# schematic.net
KiCad netlist of a schematic drawn in Altium Designer
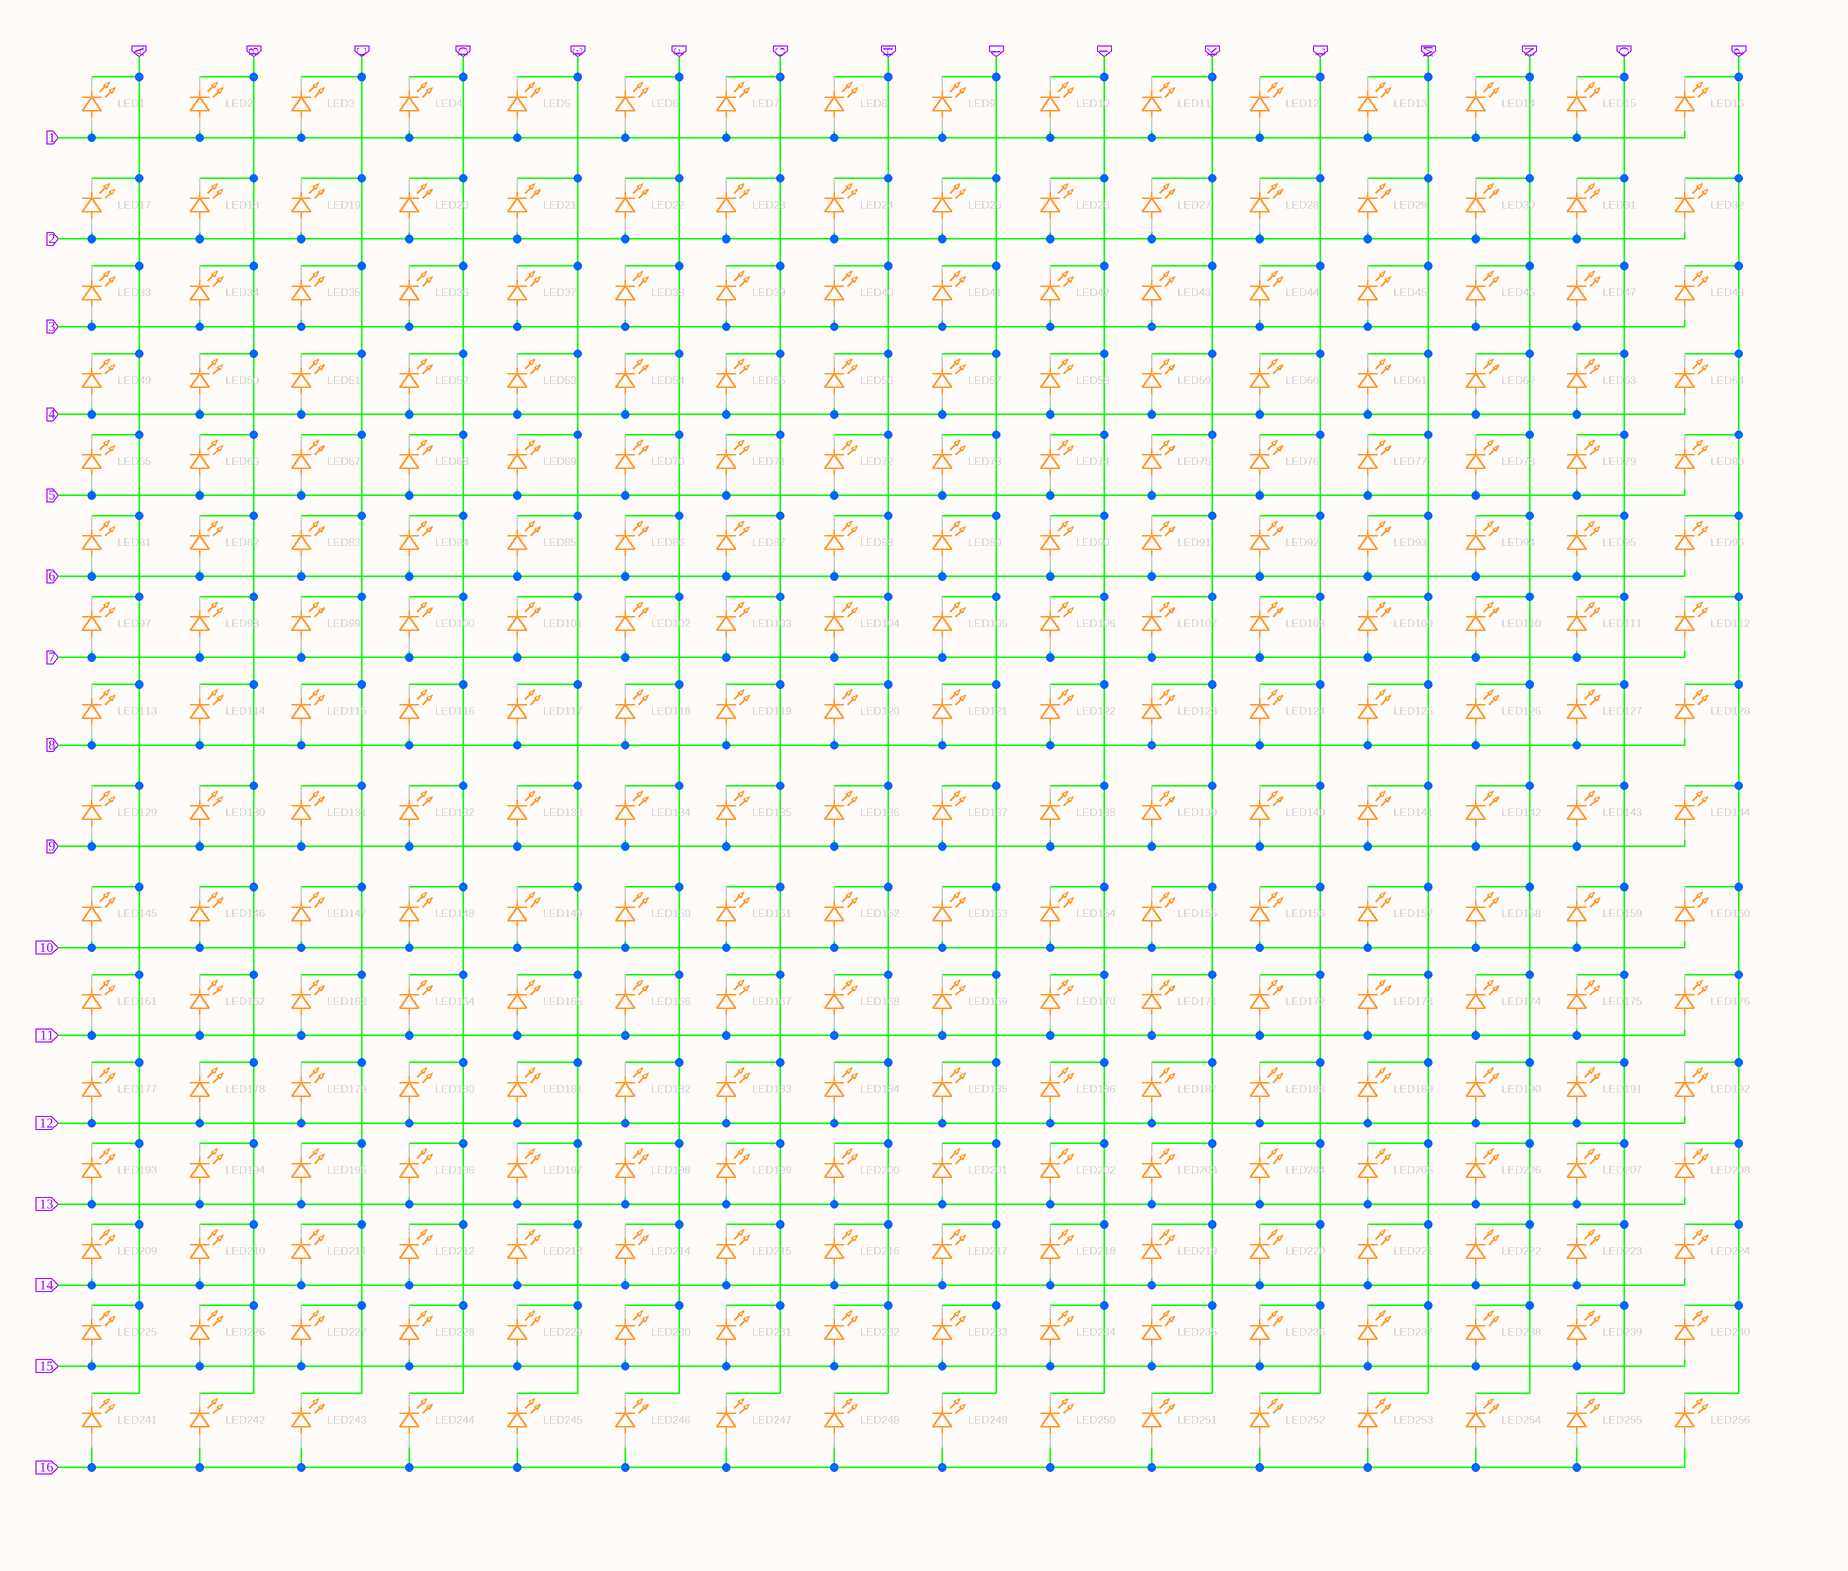
[diagram p0: schematic.schdoc, left]
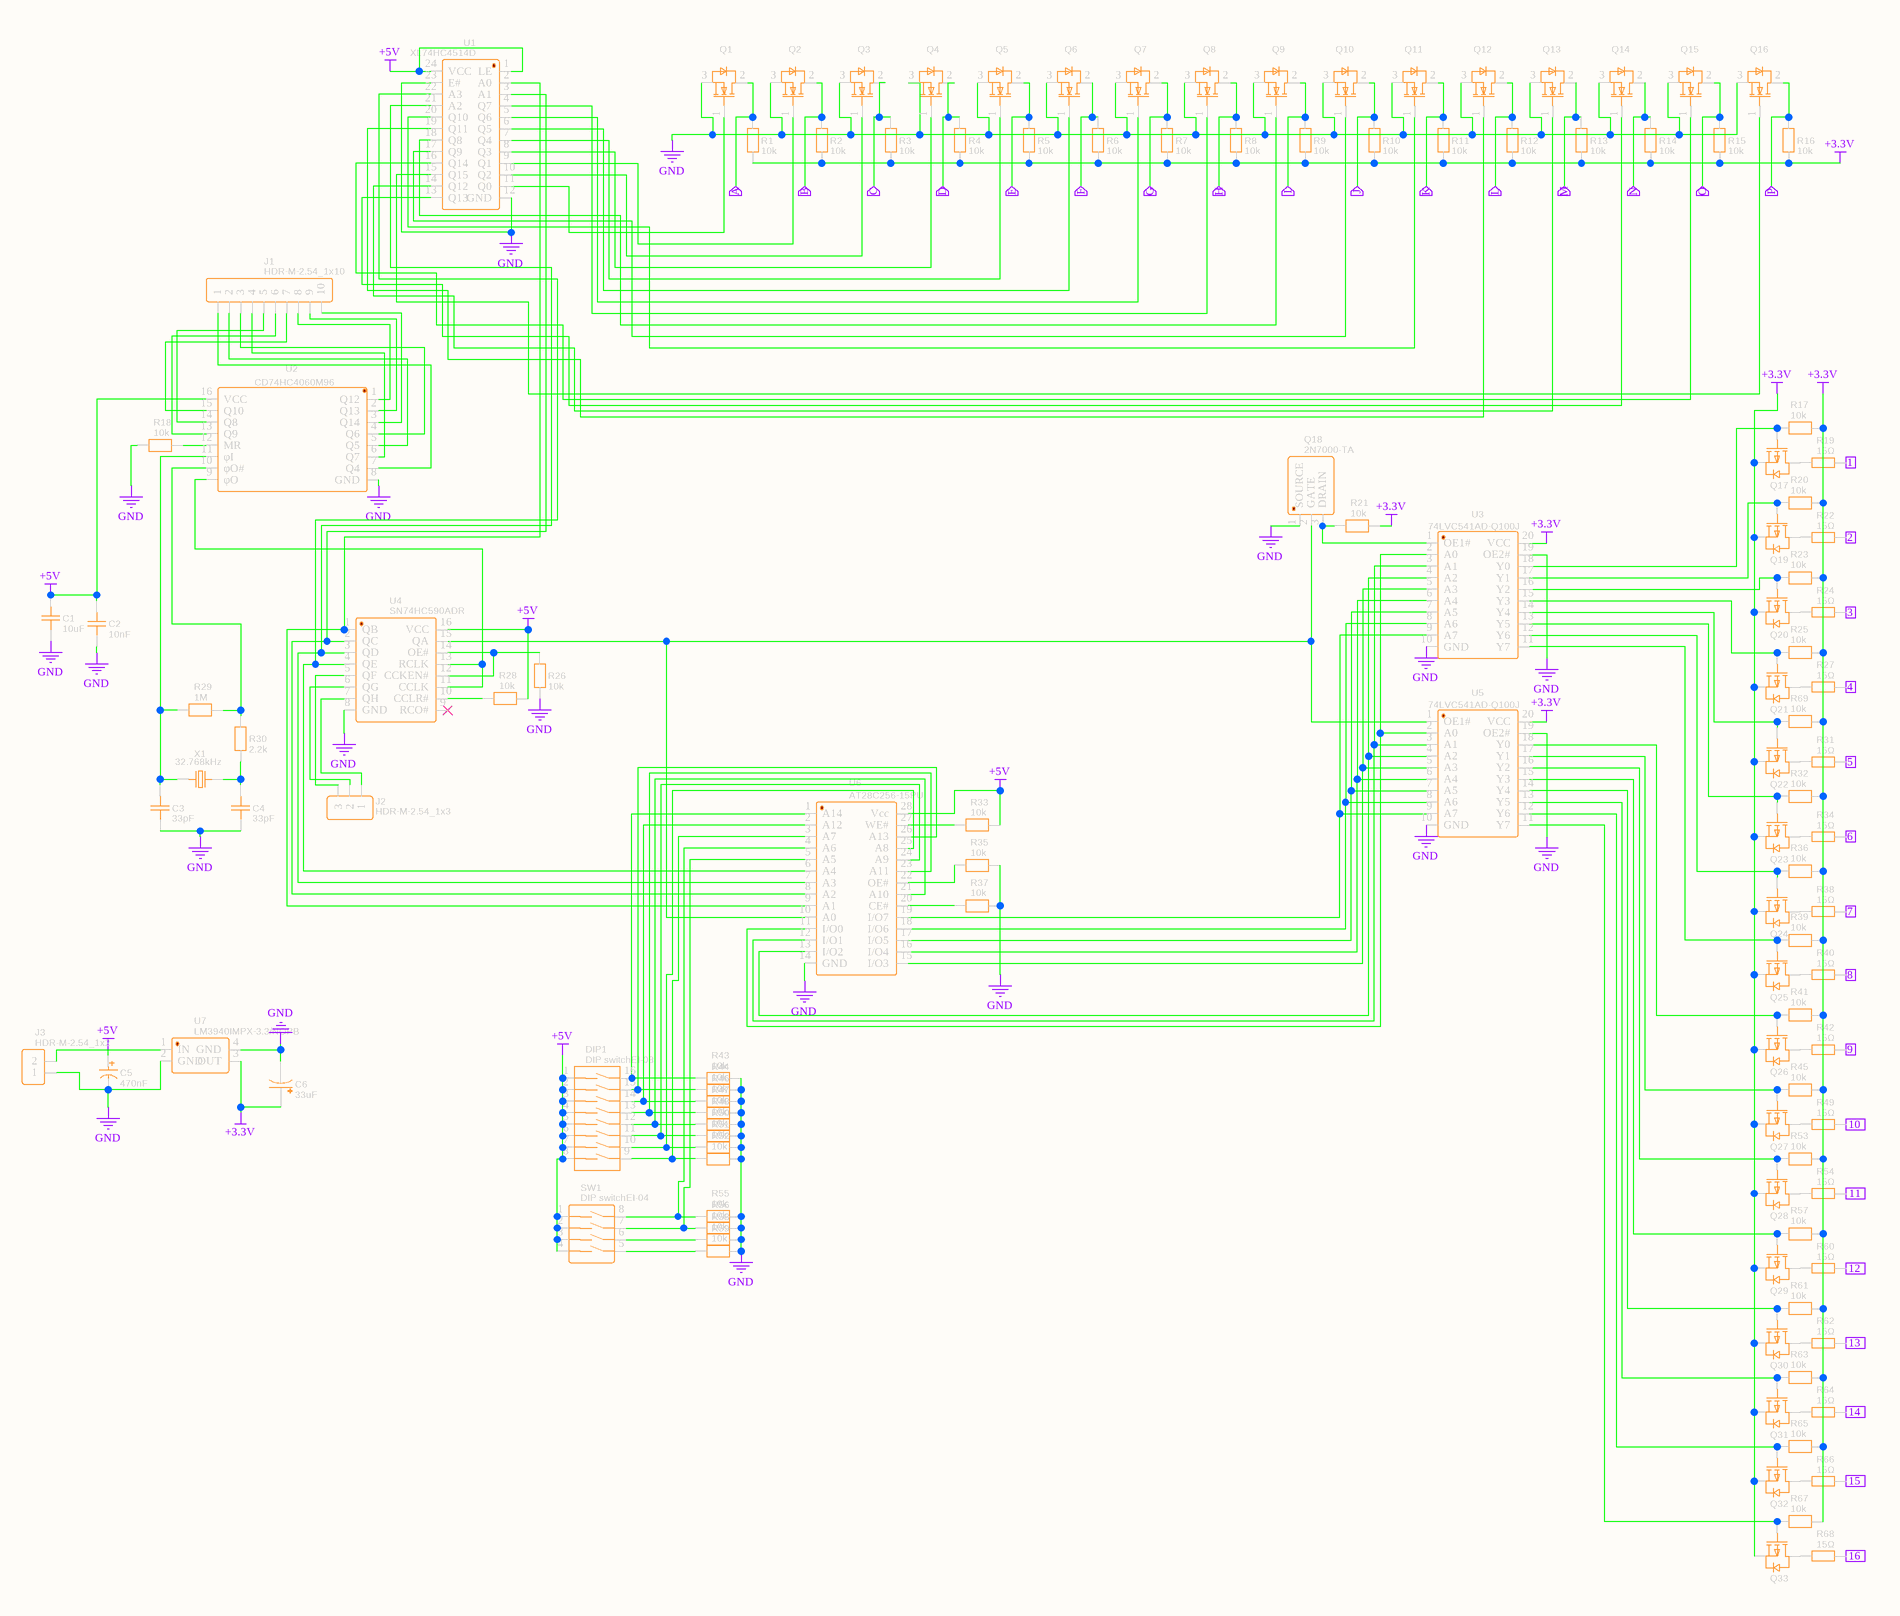
[diagram p1: schematic.schdoc, right]

(export (version "E")
  (design (tool "Eeschema 10.0.6"))
  (components
    (comp (ref "C1")
      (value "10uF")
      (fields
        (field (name "MANUFACTURER") "TORCH(火炬)")
        (field (name "MANUFACTURER PART") "CC1210Y5V16V106ZN")
        (field (name "CONTRIBUTOR") "lcsc")
      )
      (libsource (lib "altium-import") (part "root_1_10uF_"))
    )
    (comp (ref "C2")
      (value "10nF")
      (fields
        (field (name "MANUFACTURER") "HRE(芯声)")
        (field (name "MANUFACTURER PART") "CSA0805C0G103J500MT")
        (field (name "CONTRIBUTOR") "lcsc")
      )
      (libsource (lib "altium-import") (part "root_1_10nF_"))
    )
    (comp (ref "C3")
      (value "33pF")
      (fields
        (field (name "MANUFACTURER") "Kyocera AVX")
        (field (name "MANUFACTURER PART") "600F330JT250XT")
        (field (name "CONTRIBUTOR") "lcsc")
      )
      (libsource (lib "altium-import") (part "root_1_33pF_"))
    )
    (comp (ref "C4")
      (value "33pF")
      (fields
        (field (name "MANUFACTURER") "Kyocera AVX")
        (field (name "MANUFACTURER PART") "600F330JT250XT")
        (field (name "CONTRIBUTOR") "lcsc")
      )
      (libsource (lib "altium-import") (part "root_1_33pF_"))
    )
    (comp (ref "C5")
      (value "470nF")
      (fields
        (field (name "MANUFACTURER") "Chengx(承兴)")
        (field (name "MANUFACTURER PART") "kF474M050C05RR0VH2FP0")
      )
      (libsource (lib "altium-import") (part "root_0_470nF_"))
    )
    (comp (ref "C6")
      (value "33uF")
      (fields
        (field (name "MANUFACTURER") "Jianghai(南通江海)")
        (field (name "MANUFACTURER PART") "ECR1HPT330MLL063011")
        (field (name "CONTRIBUTOR") "LCSC")
      )
      (libsource (lib "altium-import") (part "root_2_33uF_"))
    )
    (comp (ref "DIP1")
      (value "DIP switchEI-08")
      (fields (field (name "MANUFACTURER") "Diptronics(圜达)") (field (name "MANUFACTURER PART") "EI-08-V"))
      (libsource (lib "altium-import") (part "root_0_DIP switchEI-08_"))
    )
    (comp (ref "J1")
      (value "HDR-M-2.54_1x10")
      (fields
        (field (name "MANUFACTURER") "hanxia(韩下)")
        (field (name "MANUFACTURER PART") "HX PZ-2005WV-1x10P")
        (field (name "CONTRIBUTOR") "LCEDA_Lib")
      )
      (libsource (lib "altium-import") (part "root_1_HDR-M-2.54_1x10_"))
    )
    (comp (ref "J2")
      (value "HDR-M-2.54_1x3")
      (fields
        (field (name "MANUFACTURER") "HDGC(华德共创)")
        (field (name "MANUFACTURER PART") "5557WRF-1X3P(HDGC4201WR-F-1X3P)")
        (field (name "CONTRIBUTOR") "LCEDA_Lib")
      )
      (libsource (lib "altium-import") (part "root_3_HDR-M-2.54_1x3_"))
    )
    (comp (ref "J3")
      (value "HDR-M-2.54_1x2")
      (fields (field (name "CONTRIBUTOR") "LCEDA_Lib"))
      (libsource (lib "altium-import") (part "root_2_HDR-M-2.54_1x2_"))
    )
    (comp (ref "LED1")
      (value "42-21A/GHC-YX1Y2N/1T")
      (fields (field (name "MANUFACTURER") "EVERLIGHT(亿光)") (field (name "CONTRIBUTOR") "lcsc"))
      (libsource (lib "altium-import") (part "root_3_42-21A/GHC-YX1Y2N/1T_"))
    )
    (comp (ref "LED2")
      (value "42-21A/GHC-YX1Y2N/1T")
      (fields (field (name "MANUFACTURER") "EVERLIGHT(亿光)") (field (name "CONTRIBUTOR") "lcsc"))
      (libsource (lib "altium-import") (part "root_3_42-21A/GHC-YX1Y2N/1T_"))
    )
    (comp (ref "LED3")
      (value "42-21A/GHC-YX1Y2N/1T")
      (fields (field (name "MANUFACTURER") "EVERLIGHT(亿光)") (field (name "CONTRIBUTOR") "lcsc"))
      (libsource (lib "altium-import") (part "root_3_42-21A/GHC-YX1Y2N/1T_"))
    )
    (comp (ref "LED4")
      (value "42-21A/GHC-YX1Y2N/1T")
      (fields (field (name "MANUFACTURER") "EVERLIGHT(亿光)") (field (name "CONTRIBUTOR") "lcsc"))
      (libsource (lib "altium-import") (part "root_3_42-21A/GHC-YX1Y2N/1T_"))
    )
    (comp (ref "LED5")
      (value "42-21A/GHC-YX1Y2N/1T")
      (fields (field (name "MANUFACTURER") "EVERLIGHT(亿光)") (field (name "CONTRIBUTOR") "lcsc"))
      (libsource (lib "altium-import") (part "root_3_42-21A/GHC-YX1Y2N/1T_"))
    )
    (comp (ref "LED6")
      (value "42-21A/GHC-YX1Y2N/1T")
      (fields (field (name "MANUFACTURER") "EVERLIGHT(亿光)") (field (name "CONTRIBUTOR") "lcsc"))
      (libsource (lib "altium-import") (part "root_3_42-21A/GHC-YX1Y2N/1T_"))
    )
    (comp (ref "LED7")
      (value "42-21A/GHC-YX1Y2N/1T")
      (fields (field (name "MANUFACTURER") "EVERLIGHT(亿光)") (field (name "CONTRIBUTOR") "lcsc"))
      (libsource (lib "altium-import") (part "root_3_42-21A/GHC-YX1Y2N/1T_"))
    )
    (comp (ref "LED8")
      (value "42-21A/GHC-YX1Y2N/1T")
      (fields (field (name "MANUFACTURER") "EVERLIGHT(亿光)") (field (name "CONTRIBUTOR") "lcsc"))
      (libsource (lib "altium-import") (part "root_3_42-21A/GHC-YX1Y2N/1T_"))
    )
    (comp (ref "LED9")
      (value "42-21A/GHC-YX1Y2N/1T")
      (fields (field (name "MANUFACTURER") "EVERLIGHT(亿光)") (field (name "CONTRIBUTOR") "lcsc"))
      (libsource (lib "altium-import") (part "root_3_42-21A/GHC-YX1Y2N/1T_"))
    )
    (comp (ref "LED10")
      (value "42-21A/GHC-YX1Y2N/1T")
      (fields (field (name "MANUFACTURER") "EVERLIGHT(亿光)") (field (name "CONTRIBUTOR") "lcsc"))
      (libsource (lib "altium-import") (part "root_3_42-21A/GHC-YX1Y2N/1T_"))
    )
    (comp (ref "LED11")
      (value "42-21A/GHC-YX1Y2N/1T")
      (fields (field (name "MANUFACTURER") "EVERLIGHT(亿光)") (field (name "CONTRIBUTOR") "lcsc"))
      (libsource (lib "altium-import") (part "root_3_42-21A/GHC-YX1Y2N/1T_"))
    )
    (comp (ref "LED12")
      (value "42-21A/GHC-YX1Y2N/1T")
      (fields (field (name "MANUFACTURER") "EVERLIGHT(亿光)") (field (name "CONTRIBUTOR") "lcsc"))
      (libsource (lib "altium-import") (part "root_3_42-21A/GHC-YX1Y2N/1T_"))
    )
    (comp (ref "LED13")
      (value "42-21A/GHC-YX1Y2N/1T")
      (fields (field (name "MANUFACTURER") "EVERLIGHT(亿光)") (field (name "CONTRIBUTOR") "lcsc"))
      (libsource (lib "altium-import") (part "root_3_42-21A/GHC-YX1Y2N/1T_"))
    )
    (comp (ref "LED14")
      (value "42-21A/GHC-YX1Y2N/1T")
      (fields (field (name "MANUFACTURER") "EVERLIGHT(亿光)") (field (name "CONTRIBUTOR") "lcsc"))
      (libsource (lib "altium-import") (part "root_3_42-21A/GHC-YX1Y2N/1T_"))
    )
    (comp (ref "LED15")
      (value "42-21A/GHC-YX1Y2N/1T")
      (fields (field (name "MANUFACTURER") "EVERLIGHT(亿光)") (field (name "CONTRIBUTOR") "lcsc"))
      (libsource (lib "altium-import") (part "root_3_42-21A/GHC-YX1Y2N/1T_"))
    )
    (comp (ref "LED16")
      (value "42-21A/GHC-YX1Y2N/1T")
      (fields (field (name "MANUFACTURER") "EVERLIGHT(亿光)") (field (name "CONTRIBUTOR") "lcsc"))
      (libsource (lib "altium-import") (part "root_3_42-21A/GHC-YX1Y2N/1T_"))
    )
    (comp (ref "LED17")
      (value "42-21A/GHC-YX1Y2N/1T")
      (fields (field (name "MANUFACTURER") "EVERLIGHT(亿光)") (field (name "CONTRIBUTOR") "lcsc"))
      (libsource (lib "altium-import") (part "root_3_42-21A/GHC-YX1Y2N/1T_"))
    )
    (comp (ref "LED18")
      (value "42-21A/GHC-YX1Y2N/1T")
      (fields (field (name "MANUFACTURER") "EVERLIGHT(亿光)") (field (name "CONTRIBUTOR") "lcsc"))
      (libsource (lib "altium-import") (part "root_3_42-21A/GHC-YX1Y2N/1T_"))
    )
    (comp (ref "LED19")
      (value "42-21A/GHC-YX1Y2N/1T")
      (fields (field (name "MANUFACTURER") "EVERLIGHT(亿光)") (field (name "CONTRIBUTOR") "lcsc"))
      (libsource (lib "altium-import") (part "root_3_42-21A/GHC-YX1Y2N/1T_"))
    )
    (comp (ref "LED20")
      (value "42-21A/GHC-YX1Y2N/1T")
      (fields (field (name "MANUFACTURER") "EVERLIGHT(亿光)") (field (name "CONTRIBUTOR") "lcsc"))
      (libsource (lib "altium-import") (part "root_3_42-21A/GHC-YX1Y2N/1T_"))
    )
    (comp (ref "LED21")
      (value "42-21A/GHC-YX1Y2N/1T")
      (fields (field (name "MANUFACTURER") "EVERLIGHT(亿光)") (field (name "CONTRIBUTOR") "lcsc"))
      (libsource (lib "altium-import") (part "root_3_42-21A/GHC-YX1Y2N/1T_"))
    )
    (comp (ref "LED22")
      (value "42-21A/GHC-YX1Y2N/1T")
      (fields (field (name "MANUFACTURER") "EVERLIGHT(亿光)") (field (name "CONTRIBUTOR") "lcsc"))
      (libsource (lib "altium-import") (part "root_3_42-21A/GHC-YX1Y2N/1T_"))
    )
    (comp (ref "LED23")
      (value "42-21A/GHC-YX1Y2N/1T")
      (fields (field (name "MANUFACTURER") "EVERLIGHT(亿光)") (field (name "CONTRIBUTOR") "lcsc"))
      (libsource (lib "altium-import") (part "root_3_42-21A/GHC-YX1Y2N/1T_"))
    )
    (comp (ref "LED24")
      (value "42-21A/GHC-YX1Y2N/1T")
      (fields (field (name "MANUFACTURER") "EVERLIGHT(亿光)") (field (name "CONTRIBUTOR") "lcsc"))
      (libsource (lib "altium-import") (part "root_3_42-21A/GHC-YX1Y2N/1T_"))
    )
    (comp (ref "LED25")
      (value "42-21A/GHC-YX1Y2N/1T")
      (fields (field (name "MANUFACTURER") "EVERLIGHT(亿光)") (field (name "CONTRIBUTOR") "lcsc"))
      (libsource (lib "altium-import") (part "root_3_42-21A/GHC-YX1Y2N/1T_"))
    )
    (comp (ref "LED26")
      (value "42-21A/GHC-YX1Y2N/1T")
      (fields (field (name "MANUFACTURER") "EVERLIGHT(亿光)") (field (name "CONTRIBUTOR") "lcsc"))
      (libsource (lib "altium-import") (part "root_3_42-21A/GHC-YX1Y2N/1T_"))
    )
    (comp (ref "LED27")
      (value "42-21A/GHC-YX1Y2N/1T")
      (fields (field (name "MANUFACTURER") "EVERLIGHT(亿光)") (field (name "CONTRIBUTOR") "lcsc"))
      (libsource (lib "altium-import") (part "root_3_42-21A/GHC-YX1Y2N/1T_"))
    )
    (comp (ref "LED28")
      (value "42-21A/GHC-YX1Y2N/1T")
      (fields (field (name "MANUFACTURER") "EVERLIGHT(亿光)") (field (name "CONTRIBUTOR") "lcsc"))
      (libsource (lib "altium-import") (part "root_3_42-21A/GHC-YX1Y2N/1T_"))
    )
    (comp (ref "LED29")
      (value "42-21A/GHC-YX1Y2N/1T")
      (fields (field (name "MANUFACTURER") "EVERLIGHT(亿光)") (field (name "CONTRIBUTOR") "lcsc"))
      (libsource (lib "altium-import") (part "root_3_42-21A/GHC-YX1Y2N/1T_"))
    )
    (comp (ref "LED30")
      (value "42-21A/GHC-YX1Y2N/1T")
      (fields (field (name "MANUFACTURER") "EVERLIGHT(亿光)") (field (name "CONTRIBUTOR") "lcsc"))
      (libsource (lib "altium-import") (part "root_3_42-21A/GHC-YX1Y2N/1T_"))
    )
    (comp (ref "LED31")
      (value "42-21A/GHC-YX1Y2N/1T")
      (fields (field (name "MANUFACTURER") "EVERLIGHT(亿光)") (field (name "CONTRIBUTOR") "lcsc"))
      (libsource (lib "altium-import") (part "root_3_42-21A/GHC-YX1Y2N/1T_"))
    )
    (comp (ref "LED32")
      (value "42-21A/GHC-YX1Y2N/1T")
      (fields (field (name "MANUFACTURER") "EVERLIGHT(亿光)") (field (name "CONTRIBUTOR") "lcsc"))
      (libsource (lib "altium-import") (part "root_3_42-21A/GHC-YX1Y2N/1T_"))
    )
    (comp (ref "LED33")
      (value "42-21A/GHC-YX1Y2N/1T")
      (fields (field (name "MANUFACTURER") "EVERLIGHT(亿光)") (field (name "CONTRIBUTOR") "lcsc"))
      (libsource (lib "altium-import") (part "root_3_42-21A/GHC-YX1Y2N/1T_"))
    )
    (comp (ref "LED34")
      (value "42-21A/GHC-YX1Y2N/1T")
      (fields (field (name "MANUFACTURER") "EVERLIGHT(亿光)") (field (name "CONTRIBUTOR") "lcsc"))
      (libsource (lib "altium-import") (part "root_3_42-21A/GHC-YX1Y2N/1T_"))
    )
    (comp (ref "LED35")
      (value "42-21A/GHC-YX1Y2N/1T")
      (fields (field (name "MANUFACTURER") "EVERLIGHT(亿光)") (field (name "CONTRIBUTOR") "lcsc"))
      (libsource (lib "altium-import") (part "root_3_42-21A/GHC-YX1Y2N/1T_"))
    )
    (comp (ref "LED36")
      (value "42-21A/GHC-YX1Y2N/1T")
      (fields (field (name "MANUFACTURER") "EVERLIGHT(亿光)") (field (name "CONTRIBUTOR") "lcsc"))
      (libsource (lib "altium-import") (part "root_3_42-21A/GHC-YX1Y2N/1T_"))
    )
    (comp (ref "LED37")
      (value "42-21A/GHC-YX1Y2N/1T")
      (fields (field (name "MANUFACTURER") "EVERLIGHT(亿光)") (field (name "CONTRIBUTOR") "lcsc"))
      (libsource (lib "altium-import") (part "root_3_42-21A/GHC-YX1Y2N/1T_"))
    )
    (comp (ref "LED38")
      (value "42-21A/GHC-YX1Y2N/1T")
      (fields (field (name "MANUFACTURER") "EVERLIGHT(亿光)") (field (name "CONTRIBUTOR") "lcsc"))
      (libsource (lib "altium-import") (part "root_3_42-21A/GHC-YX1Y2N/1T_"))
    )
    (comp (ref "LED39")
      (value "42-21A/GHC-YX1Y2N/1T")
      (fields (field (name "MANUFACTURER") "EVERLIGHT(亿光)") (field (name "CONTRIBUTOR") "lcsc"))
      (libsource (lib "altium-import") (part "root_3_42-21A/GHC-YX1Y2N/1T_"))
    )
    (comp (ref "LED40")
      (value "42-21A/GHC-YX1Y2N/1T")
      (fields (field (name "MANUFACTURER") "EVERLIGHT(亿光)") (field (name "CONTRIBUTOR") "lcsc"))
      (libsource (lib "altium-import") (part "root_3_42-21A/GHC-YX1Y2N/1T_"))
    )
    (comp (ref "LED41")
      (value "42-21A/GHC-YX1Y2N/1T")
      (fields (field (name "MANUFACTURER") "EVERLIGHT(亿光)") (field (name "CONTRIBUTOR") "lcsc"))
      (libsource (lib "altium-import") (part "root_3_42-21A/GHC-YX1Y2N/1T_"))
    )
    (comp (ref "LED42")
      (value "42-21A/GHC-YX1Y2N/1T")
      (fields (field (name "MANUFACTURER") "EVERLIGHT(亿光)") (field (name "CONTRIBUTOR") "lcsc"))
      (libsource (lib "altium-import") (part "root_3_42-21A/GHC-YX1Y2N/1T_"))
    )
    (comp (ref "LED43")
      (value "42-21A/GHC-YX1Y2N/1T")
      (fields (field (name "MANUFACTURER") "EVERLIGHT(亿光)") (field (name "CONTRIBUTOR") "lcsc"))
      (libsource (lib "altium-import") (part "root_3_42-21A/GHC-YX1Y2N/1T_"))
    )
    (comp (ref "LED44")
      (value "42-21A/GHC-YX1Y2N/1T")
      (fields (field (name "MANUFACTURER") "EVERLIGHT(亿光)") (field (name "CONTRIBUTOR") "lcsc"))
      (libsource (lib "altium-import") (part "root_3_42-21A/GHC-YX1Y2N/1T_"))
    )
    (comp (ref "LED45")
      (value "42-21A/GHC-YX1Y2N/1T")
      (fields (field (name "MANUFACTURER") "EVERLIGHT(亿光)") (field (name "CONTRIBUTOR") "lcsc"))
      (libsource (lib "altium-import") (part "root_3_42-21A/GHC-YX1Y2N/1T_"))
    )
    (comp (ref "LED46")
      (value "42-21A/GHC-YX1Y2N/1T")
      (fields (field (name "MANUFACTURER") "EVERLIGHT(亿光)") (field (name "CONTRIBUTOR") "lcsc"))
      (libsource (lib "altium-import") (part "root_3_42-21A/GHC-YX1Y2N/1T_"))
    )
    (comp (ref "LED47")
      (value "42-21A/GHC-YX1Y2N/1T")
      (fields (field (name "MANUFACTURER") "EVERLIGHT(亿光)") (field (name "CONTRIBUTOR") "lcsc"))
      (libsource (lib "altium-import") (part "root_3_42-21A/GHC-YX1Y2N/1T_"))
    )
    (comp (ref "LED48")
      (value "42-21A/GHC-YX1Y2N/1T")
      (fields (field (name "MANUFACTURER") "EVERLIGHT(亿光)") (field (name "CONTRIBUTOR") "lcsc"))
      (libsource (lib "altium-import") (part "root_3_42-21A/GHC-YX1Y2N/1T_"))
    )
    (comp (ref "LED49")
      (value "42-21A/GHC-YX1Y2N/1T")
      (fields (field (name "MANUFACTURER") "EVERLIGHT(亿光)") (field (name "CONTRIBUTOR") "lcsc"))
      (libsource (lib "altium-import") (part "root_3_42-21A/GHC-YX1Y2N/1T_"))
    )
    (comp (ref "LED50")
      (value "42-21A/GHC-YX1Y2N/1T")
      (fields (field (name "MANUFACTURER") "EVERLIGHT(亿光)") (field (name "CONTRIBUTOR") "lcsc"))
      (libsource (lib "altium-import") (part "root_3_42-21A/GHC-YX1Y2N/1T_"))
    )
    (comp (ref "LED51")
      (value "42-21A/GHC-YX1Y2N/1T")
      (fields (field (name "MANUFACTURER") "EVERLIGHT(亿光)") (field (name "CONTRIBUTOR") "lcsc"))
      (libsource (lib "altium-import") (part "root_3_42-21A/GHC-YX1Y2N/1T_"))
    )
    (comp (ref "LED52")
      (value "42-21A/GHC-YX1Y2N/1T")
      (fields (field (name "MANUFACTURER") "EVERLIGHT(亿光)") (field (name "CONTRIBUTOR") "lcsc"))
      (libsource (lib "altium-import") (part "root_3_42-21A/GHC-YX1Y2N/1T_"))
    )
    (comp (ref "LED53")
      (value "42-21A/GHC-YX1Y2N/1T")
      (fields (field (name "MANUFACTURER") "EVERLIGHT(亿光)") (field (name "CONTRIBUTOR") "lcsc"))
      (libsource (lib "altium-import") (part "root_3_42-21A/GHC-YX1Y2N/1T_"))
    )
    (comp (ref "LED54")
      (value "42-21A/GHC-YX1Y2N/1T")
      (fields (field (name "MANUFACTURER") "EVERLIGHT(亿光)") (field (name "CONTRIBUTOR") "lcsc"))
      (libsource (lib "altium-import") (part "root_3_42-21A/GHC-YX1Y2N/1T_"))
    )
    (comp (ref "LED55")
      (value "42-21A/GHC-YX1Y2N/1T")
      (fields (field (name "MANUFACTURER") "EVERLIGHT(亿光)") (field (name "CONTRIBUTOR") "lcsc"))
      (libsource (lib "altium-import") (part "root_3_42-21A/GHC-YX1Y2N/1T_"))
    )
    (comp (ref "LED56")
      (value "42-21A/GHC-YX1Y2N/1T")
      (fields (field (name "MANUFACTURER") "EVERLIGHT(亿光)") (field (name "CONTRIBUTOR") "lcsc"))
      (libsource (lib "altium-import") (part "root_3_42-21A/GHC-YX1Y2N/1T_"))
    )
    (comp (ref "LED57")
      (value "42-21A/GHC-YX1Y2N/1T")
      (fields (field (name "MANUFACTURER") "EVERLIGHT(亿光)") (field (name "CONTRIBUTOR") "lcsc"))
      (libsource (lib "altium-import") (part "root_3_42-21A/GHC-YX1Y2N/1T_"))
    )
    (comp (ref "LED58")
      (value "42-21A/GHC-YX1Y2N/1T")
      (fields (field (name "MANUFACTURER") "EVERLIGHT(亿光)") (field (name "CONTRIBUTOR") "lcsc"))
      (libsource (lib "altium-import") (part "root_3_42-21A/GHC-YX1Y2N/1T_"))
    )
    (comp (ref "LED59")
      (value "42-21A/GHC-YX1Y2N/1T")
      (fields (field (name "MANUFACTURER") "EVERLIGHT(亿光)") (field (name "CONTRIBUTOR") "lcsc"))
      (libsource (lib "altium-import") (part "root_3_42-21A/GHC-YX1Y2N/1T_"))
    )
    (comp (ref "LED60")
      (value "42-21A/GHC-YX1Y2N/1T")
      (fields (field (name "MANUFACTURER") "EVERLIGHT(亿光)") (field (name "CONTRIBUTOR") "lcsc"))
      (libsource (lib "altium-import") (part "root_3_42-21A/GHC-YX1Y2N/1T_"))
    )
    (comp (ref "LED61")
      (value "42-21A/GHC-YX1Y2N/1T")
      (fields (field (name "MANUFACTURER") "EVERLIGHT(亿光)") (field (name "CONTRIBUTOR") "lcsc"))
      (libsource (lib "altium-import") (part "root_3_42-21A/GHC-YX1Y2N/1T_"))
    )
    (comp (ref "LED62")
      (value "42-21A/GHC-YX1Y2N/1T")
      (fields (field (name "MANUFACTURER") "EVERLIGHT(亿光)") (field (name "CONTRIBUTOR") "lcsc"))
      (libsource (lib "altium-import") (part "root_3_42-21A/GHC-YX1Y2N/1T_"))
    )
    (comp (ref "LED63")
      (value "42-21A/GHC-YX1Y2N/1T")
      (fields (field (name "MANUFACTURER") "EVERLIGHT(亿光)") (field (name "CONTRIBUTOR") "lcsc"))
      (libsource (lib "altium-import") (part "root_3_42-21A/GHC-YX1Y2N/1T_"))
    )
    (comp (ref "LED64")
      (value "42-21A/GHC-YX1Y2N/1T")
      (fields (field (name "MANUFACTURER") "EVERLIGHT(亿光)") (field (name "CONTRIBUTOR") "lcsc"))
      (libsource (lib "altium-import") (part "root_3_42-21A/GHC-YX1Y2N/1T_"))
    )
    (comp (ref "LED65")
      (value "42-21A/GHC-YX1Y2N/1T")
      (fields (field (name "MANUFACTURER") "EVERLIGHT(亿光)") (field (name "CONTRIBUTOR") "lcsc"))
      (libsource (lib "altium-import") (part "root_3_42-21A/GHC-YX1Y2N/1T_"))
    )
    (comp (ref "LED66")
      (value "42-21A/GHC-YX1Y2N/1T")
      (fields (field (name "MANUFACTURER") "EVERLIGHT(亿光)") (field (name "CONTRIBUTOR") "lcsc"))
      (libsource (lib "altium-import") (part "root_3_42-21A/GHC-YX1Y2N/1T_"))
    )
    (comp (ref "LED67")
      (value "42-21A/GHC-YX1Y2N/1T")
      (fields (field (name "MANUFACTURER") "EVERLIGHT(亿光)") (field (name "CONTRIBUTOR") "lcsc"))
      (libsource (lib "altium-import") (part "root_3_42-21A/GHC-YX1Y2N/1T_"))
    )
    (comp (ref "LED68")
      (value "42-21A/GHC-YX1Y2N/1T")
      (fields (field (name "MANUFACTURER") "EVERLIGHT(亿光)") (field (name "CONTRIBUTOR") "lcsc"))
      (libsource (lib "altium-import") (part "root_3_42-21A/GHC-YX1Y2N/1T_"))
    )
    (comp (ref "LED69")
      (value "42-21A/GHC-YX1Y2N/1T")
      (fields (field (name "MANUFACTURER") "EVERLIGHT(亿光)") (field (name "CONTRIBUTOR") "lcsc"))
      (libsource (lib "altium-import") (part "root_3_42-21A/GHC-YX1Y2N/1T_"))
    )
    (comp (ref "LED70")
      (value "42-21A/GHC-YX1Y2N/1T")
      (fields (field (name "MANUFACTURER") "EVERLIGHT(亿光)") (field (name "CONTRIBUTOR") "lcsc"))
      (libsource (lib "altium-import") (part "root_3_42-21A/GHC-YX1Y2N/1T_"))
    )
    (comp (ref "LED71")
      (value "42-21A/GHC-YX1Y2N/1T")
      (fields (field (name "MANUFACTURER") "EVERLIGHT(亿光)") (field (name "CONTRIBUTOR") "lcsc"))
      (libsource (lib "altium-import") (part "root_3_42-21A/GHC-YX1Y2N/1T_"))
    )
    (comp (ref "LED72")
      (value "42-21A/GHC-YX1Y2N/1T")
      (fields (field (name "MANUFACTURER") "EVERLIGHT(亿光)") (field (name "CONTRIBUTOR") "lcsc"))
      (libsource (lib "altium-import") (part "root_3_42-21A/GHC-YX1Y2N/1T_"))
    )
    (comp (ref "LED73")
      (value "42-21A/GHC-YX1Y2N/1T")
      (fields (field (name "MANUFACTURER") "EVERLIGHT(亿光)") (field (name "CONTRIBUTOR") "lcsc"))
      (libsource (lib "altium-import") (part "root_3_42-21A/GHC-YX1Y2N/1T_"))
    )
    (comp (ref "LED74")
      (value "42-21A/GHC-YX1Y2N/1T")
      (fields (field (name "MANUFACTURER") "EVERLIGHT(亿光)") (field (name "CONTRIBUTOR") "lcsc"))
      (libsource (lib "altium-import") (part "root_3_42-21A/GHC-YX1Y2N/1T_"))
    )
    (comp (ref "LED75")
      (value "42-21A/GHC-YX1Y2N/1T")
      (fields (field (name "MANUFACTURER") "EVERLIGHT(亿光)") (field (name "CONTRIBUTOR") "lcsc"))
      (libsource (lib "altium-import") (part "root_3_42-21A/GHC-YX1Y2N/1T_"))
    )
    (comp (ref "LED76")
      (value "42-21A/GHC-YX1Y2N/1T")
      (fields (field (name "MANUFACTURER") "EVERLIGHT(亿光)") (field (name "CONTRIBUTOR") "lcsc"))
      (libsource (lib "altium-import") (part "root_3_42-21A/GHC-YX1Y2N/1T_"))
    )
    (comp (ref "LED77")
      (value "42-21A/GHC-YX1Y2N/1T")
      (fields (field (name "MANUFACTURER") "EVERLIGHT(亿光)") (field (name "CONTRIBUTOR") "lcsc"))
      (libsource (lib "altium-import") (part "root_3_42-21A/GHC-YX1Y2N/1T_"))
    )
    (comp (ref "LED78")
      (value "42-21A/GHC-YX1Y2N/1T")
      (fields (field (name "MANUFACTURER") "EVERLIGHT(亿光)") (field (name "CONTRIBUTOR") "lcsc"))
      (libsource (lib "altium-import") (part "root_3_42-21A/GHC-YX1Y2N/1T_"))
    )
    (comp (ref "LED79")
      (value "42-21A/GHC-YX1Y2N/1T")
      (fields (field (name "MANUFACTURER") "EVERLIGHT(亿光)") (field (name "CONTRIBUTOR") "lcsc"))
      (libsource (lib "altium-import") (part "root_3_42-21A/GHC-YX1Y2N/1T_"))
    )
    (comp (ref "LED80")
      (value "42-21A/GHC-YX1Y2N/1T")
      (fields (field (name "MANUFACTURER") "EVERLIGHT(亿光)") (field (name "CONTRIBUTOR") "lcsc"))
      (libsource (lib "altium-import") (part "root_3_42-21A/GHC-YX1Y2N/1T_"))
    )
    (comp (ref "LED81")
      (value "42-21A/GHC-YX1Y2N/1T")
      (fields (field (name "MANUFACTURER") "EVERLIGHT(亿光)") (field (name "CONTRIBUTOR") "lcsc"))
      (libsource (lib "altium-import") (part "root_3_42-21A/GHC-YX1Y2N/1T_"))
    )
    (comp (ref "LED82")
      (value "42-21A/GHC-YX1Y2N/1T")
      (fields (field (name "MANUFACTURER") "EVERLIGHT(亿光)") (field (name "CONTRIBUTOR") "lcsc"))
      (libsource (lib "altium-import") (part "root_3_42-21A/GHC-YX1Y2N/1T_"))
    )
    (comp (ref "LED83")
      (value "42-21A/GHC-YX1Y2N/1T")
      (fields (field (name "MANUFACTURER") "EVERLIGHT(亿光)") (field (name "CONTRIBUTOR") "lcsc"))
      (libsource (lib "altium-import") (part "root_3_42-21A/GHC-YX1Y2N/1T_"))
    )
    (comp (ref "LED84")
      (value "42-21A/GHC-YX1Y2N/1T")
      (fields (field (name "MANUFACTURER") "EVERLIGHT(亿光)") (field (name "CONTRIBUTOR") "lcsc"))
      (libsource (lib "altium-import") (part "root_3_42-21A/GHC-YX1Y2N/1T_"))
    )
    (comp (ref "LED85")
      (value "42-21A/GHC-YX1Y2N/1T")
      (fields (field (name "MANUFACTURER") "EVERLIGHT(亿光)") (field (name "CONTRIBUTOR") "lcsc"))
      (libsource (lib "altium-import") (part "root_3_42-21A/GHC-YX1Y2N/1T_"))
    )
    (comp (ref "LED86")
      (value "42-21A/GHC-YX1Y2N/1T")
      (fields (field (name "MANUFACTURER") "EVERLIGHT(亿光)") (field (name "CONTRIBUTOR") "lcsc"))
      (libsource (lib "altium-import") (part "root_3_42-21A/GHC-YX1Y2N/1T_"))
    )
    (comp (ref "LED87")
      (value "42-21A/GHC-YX1Y2N/1T")
      (fields (field (name "MANUFACTURER") "EVERLIGHT(亿光)") (field (name "CONTRIBUTOR") "lcsc"))
      (libsource (lib "altium-import") (part "root_3_42-21A/GHC-YX1Y2N/1T_"))
    )
    (comp (ref "LED88")
      (value "42-21A/GHC-YX1Y2N/1T")
      (fields (field (name "MANUFACTURER") "EVERLIGHT(亿光)") (field (name "CONTRIBUTOR") "lcsc"))
      (libsource (lib "altium-import") (part "root_3_42-21A/GHC-YX1Y2N/1T_"))
    )
    (comp (ref "LED89")
      (value "42-21A/GHC-YX1Y2N/1T")
      (fields (field (name "MANUFACTURER") "EVERLIGHT(亿光)") (field (name "CONTRIBUTOR") "lcsc"))
      (libsource (lib "altium-import") (part "root_3_42-21A/GHC-YX1Y2N/1T_"))
    )
    (comp (ref "LED90")
      (value "42-21A/GHC-YX1Y2N/1T")
      (fields (field (name "MANUFACTURER") "EVERLIGHT(亿光)") (field (name "CONTRIBUTOR") "lcsc"))
      (libsource (lib "altium-import") (part "root_3_42-21A/GHC-YX1Y2N/1T_"))
    )
    (comp (ref "LED91")
      (value "42-21A/GHC-YX1Y2N/1T")
      (fields (field (name "MANUFACTURER") "EVERLIGHT(亿光)") (field (name "CONTRIBUTOR") "lcsc"))
      (libsource (lib "altium-import") (part "root_3_42-21A/GHC-YX1Y2N/1T_"))
    )
    (comp (ref "LED92")
      (value "42-21A/GHC-YX1Y2N/1T")
      (fields (field (name "MANUFACTURER") "EVERLIGHT(亿光)") (field (name "CONTRIBUTOR") "lcsc"))
      (libsource (lib "altium-import") (part "root_3_42-21A/GHC-YX1Y2N/1T_"))
    )
    (comp (ref "LED93")
      (value "42-21A/GHC-YX1Y2N/1T")
      (fields (field (name "MANUFACTURER") "EVERLIGHT(亿光)") (field (name "CONTRIBUTOR") "lcsc"))
      (libsource (lib "altium-import") (part "root_3_42-21A/GHC-YX1Y2N/1T_"))
    )
    (comp (ref "LED94")
      (value "42-21A/GHC-YX1Y2N/1T")
      (fields (field (name "MANUFACTURER") "EVERLIGHT(亿光)") (field (name "CONTRIBUTOR") "lcsc"))
      (libsource (lib "altium-import") (part "root_3_42-21A/GHC-YX1Y2N/1T_"))
    )
    (comp (ref "LED95")
      (value "42-21A/GHC-YX1Y2N/1T")
      (fields (field (name "MANUFACTURER") "EVERLIGHT(亿光)") (field (name "CONTRIBUTOR") "lcsc"))
      (libsource (lib "altium-import") (part "root_3_42-21A/GHC-YX1Y2N/1T_"))
    )
    (comp (ref "LED96")
      (value "42-21A/GHC-YX1Y2N/1T")
      (fields (field (name "MANUFACTURER") "EVERLIGHT(亿光)") (field (name "CONTRIBUTOR") "lcsc"))
      (libsource (lib "altium-import") (part "root_3_42-21A/GHC-YX1Y2N/1T_"))
    )
    (comp (ref "LED97")
      (value "42-21A/GHC-YX1Y2N/1T")
      (fields (field (name "MANUFACTURER") "EVERLIGHT(亿光)") (field (name "CONTRIBUTOR") "lcsc"))
      (libsource (lib "altium-import") (part "root_3_42-21A/GHC-YX1Y2N/1T_"))
    )
    (comp (ref "LED98")
      (value "42-21A/GHC-YX1Y2N/1T")
      (fields (field (name "MANUFACTURER") "EVERLIGHT(亿光)") (field (name "CONTRIBUTOR") "lcsc"))
      (libsource (lib "altium-import") (part "root_3_42-21A/GHC-YX1Y2N/1T_"))
    )
    (comp (ref "LED99")
      (value "42-21A/GHC-YX1Y2N/1T")
      (fields (field (name "MANUFACTURER") "EVERLIGHT(亿光)") (field (name "CONTRIBUTOR") "lcsc"))
      (libsource (lib "altium-import") (part "root_3_42-21A/GHC-YX1Y2N/1T_"))
    )
    (comp (ref "LED100")
      (value "42-21A/GHC-YX1Y2N/1T")
      (fields (field (name "MANUFACTURER") "EVERLIGHT(亿光)") (field (name "CONTRIBUTOR") "lcsc"))
      (libsource (lib "altium-import") (part "root_3_42-21A/GHC-YX1Y2N/1T_"))
    )
    (comp (ref "LED101")
      (value "42-21A/GHC-YX1Y2N/1T")
      (fields (field (name "MANUFACTURER") "EVERLIGHT(亿光)") (field (name "CONTRIBUTOR") "lcsc"))
      (libsource (lib "altium-import") (part "root_3_42-21A/GHC-YX1Y2N/1T_"))
    )
    (comp (ref "LED102")
      (value "42-21A/GHC-YX1Y2N/1T")
      (fields (field (name "MANUFACTURER") "EVERLIGHT(亿光)") (field (name "CONTRIBUTOR") "lcsc"))
      (libsource (lib "altium-import") (part "root_3_42-21A/GHC-YX1Y2N/1T_"))
    )
    (comp (ref "LED103")
      (value "42-21A/GHC-YX1Y2N/1T")
      (fields (field (name "MANUFACTURER") "EVERLIGHT(亿光)") (field (name "CONTRIBUTOR") "lcsc"))
      (libsource (lib "altium-import") (part "root_3_42-21A/GHC-YX1Y2N/1T_"))
    )
    (comp (ref "LED104")
      (value "42-21A/GHC-YX1Y2N/1T")
      (fields (field (name "MANUFACTURER") "EVERLIGHT(亿光)") (field (name "CONTRIBUTOR") "lcsc"))
      (libsource (lib "altium-import") (part "root_3_42-21A/GHC-YX1Y2N/1T_"))
    )
    (comp (ref "LED105")
      (value "42-21A/GHC-YX1Y2N/1T")
      (fields (field (name "MANUFACTURER") "EVERLIGHT(亿光)") (field (name "CONTRIBUTOR") "lcsc"))
      (libsource (lib "altium-import") (part "root_3_42-21A/GHC-YX1Y2N/1T_"))
    )
    (comp (ref "LED106")
      (value "42-21A/GHC-YX1Y2N/1T")
      (fields (field (name "MANUFACTURER") "EVERLIGHT(亿光)") (field (name "CONTRIBUTOR") "lcsc"))
      (libsource (lib "altium-import") (part "root_3_42-21A/GHC-YX1Y2N/1T_"))
    )
    (comp (ref "LED107")
      (value "42-21A/GHC-YX1Y2N/1T")
      (fields (field (name "MANUFACTURER") "EVERLIGHT(亿光)") (field (name "CONTRIBUTOR") "lcsc"))
      (libsource (lib "altium-import") (part "root_3_42-21A/GHC-YX1Y2N/1T_"))
    )
    (comp (ref "LED108")
      (value "42-21A/GHC-YX1Y2N/1T")
      (fields (field (name "MANUFACTURER") "EVERLIGHT(亿光)") (field (name "CONTRIBUTOR") "lcsc"))
      (libsource (lib "altium-import") (part "root_3_42-21A/GHC-YX1Y2N/1T_"))
    )
    (comp (ref "LED109")
      (value "42-21A/GHC-YX1Y2N/1T")
      (fields (field (name "MANUFACTURER") "EVERLIGHT(亿光)") (field (name "CONTRIBUTOR") "lcsc"))
      (libsource (lib "altium-import") (part "root_3_42-21A/GHC-YX1Y2N/1T_"))
    )
    (comp (ref "LED110")
      (value "42-21A/GHC-YX1Y2N/1T")
      (fields (field (name "MANUFACTURER") "EVERLIGHT(亿光)") (field (name "CONTRIBUTOR") "lcsc"))
      (libsource (lib "altium-import") (part "root_3_42-21A/GHC-YX1Y2N/1T_"))
    )
    (comp (ref "LED111")
      (value "42-21A/GHC-YX1Y2N/1T")
      (fields (field (name "MANUFACTURER") "EVERLIGHT(亿光)") (field (name "CONTRIBUTOR") "lcsc"))
      (libsource (lib "altium-import") (part "root_3_42-21A/GHC-YX1Y2N/1T_"))
    )
    (comp (ref "LED112")
      (value "42-21A/GHC-YX1Y2N/1T")
      (fields (field (name "MANUFACTURER") "EVERLIGHT(亿光)") (field (name "CONTRIBUTOR") "lcsc"))
      (libsource (lib "altium-import") (part "root_3_42-21A/GHC-YX1Y2N/1T_"))
    )
    (comp (ref "LED113")
      (value "42-21A/GHC-YX1Y2N/1T")
      (fields (field (name "MANUFACTURER") "EVERLIGHT(亿光)") (field (name "CONTRIBUTOR") "lcsc"))
      (libsource (lib "altium-import") (part "root_3_42-21A/GHC-YX1Y2N/1T_"))
    )
    (comp (ref "LED114")
      (value "42-21A/GHC-YX1Y2N/1T")
      (fields (field (name "MANUFACTURER") "EVERLIGHT(亿光)") (field (name "CONTRIBUTOR") "lcsc"))
      (libsource (lib "altium-import") (part "root_3_42-21A/GHC-YX1Y2N/1T_"))
    )
    (comp (ref "LED115")
      (value "42-21A/GHC-YX1Y2N/1T")
      (fields (field (name "MANUFACTURER") "EVERLIGHT(亿光)") (field (name "CONTRIBUTOR") "lcsc"))
      (libsource (lib "altium-import") (part "root_3_42-21A/GHC-YX1Y2N/1T_"))
    )
    (comp (ref "LED116")
      (value "42-21A/GHC-YX1Y2N/1T")
      (fields (field (name "MANUFACTURER") "EVERLIGHT(亿光)") (field (name "CONTRIBUTOR") "lcsc"))
      (libsource (lib "altium-import") (part "root_3_42-21A/GHC-YX1Y2N/1T_"))
    )
    (comp (ref "LED117")
      (value "42-21A/GHC-YX1Y2N/1T")
      (fields (field (name "MANUFACTURER") "EVERLIGHT(亿光)") (field (name "CONTRIBUTOR") "lcsc"))
      (libsource (lib "altium-import") (part "root_3_42-21A/GHC-YX1Y2N/1T_"))
    )
    (comp (ref "LED118")
      (value "42-21A/GHC-YX1Y2N/1T")
      (fields (field (name "MANUFACTURER") "EVERLIGHT(亿光)") (field (name "CONTRIBUTOR") "lcsc"))
      (libsource (lib "altium-import") (part "root_3_42-21A/GHC-YX1Y2N/1T_"))
    )
    (comp (ref "LED119")
      (value "42-21A/GHC-YX1Y2N/1T")
      (fields (field (name "MANUFACTURER") "EVERLIGHT(亿光)") (field (name "CONTRIBUTOR") "lcsc"))
      (libsource (lib "altium-import") (part "root_3_42-21A/GHC-YX1Y2N/1T_"))
    )
    (comp (ref "LED120")
      (value "42-21A/GHC-YX1Y2N/1T")
      (fields (field (name "MANUFACTURER") "EVERLIGHT(亿光)") (field (name "CONTRIBUTOR") "lcsc"))
      (libsource (lib "altium-import") (part "root_3_42-21A/GHC-YX1Y2N/1T_"))
    )
    (comp (ref "LED121")
      (value "42-21A/GHC-YX1Y2N/1T")
      (fields (field (name "MANUFACTURER") "EVERLIGHT(亿光)") (field (name "CONTRIBUTOR") "lcsc"))
      (libsource (lib "altium-import") (part "root_3_42-21A/GHC-YX1Y2N/1T_"))
    )
    (comp (ref "LED122")
      (value "42-21A/GHC-YX1Y2N/1T")
      (fields (field (name "MANUFACTURER") "EVERLIGHT(亿光)") (field (name "CONTRIBUTOR") "lcsc"))
      (libsource (lib "altium-import") (part "root_3_42-21A/GHC-YX1Y2N/1T_"))
    )
    (comp (ref "LED123")
      (value "42-21A/GHC-YX1Y2N/1T")
      (fields (field (name "MANUFACTURER") "EVERLIGHT(亿光)") (field (name "CONTRIBUTOR") "lcsc"))
      (libsource (lib "altium-import") (part "root_3_42-21A/GHC-YX1Y2N/1T_"))
    )
    (comp (ref "LED124")
      (value "42-21A/GHC-YX1Y2N/1T")
      (fields (field (name "MANUFACTURER") "EVERLIGHT(亿光)") (field (name "CONTRIBUTOR") "lcsc"))
      (libsource (lib "altium-import") (part "root_3_42-21A/GHC-YX1Y2N/1T_"))
    )
    (comp (ref "LED125")
      (value "42-21A/GHC-YX1Y2N/1T")
      (fields (field (name "MANUFACTURER") "EVERLIGHT(亿光)") (field (name "CONTRIBUTOR") "lcsc"))
      (libsource (lib "altium-import") (part "root_3_42-21A/GHC-YX1Y2N/1T_"))
    )
    (comp (ref "LED126")
      (value "42-21A/GHC-YX1Y2N/1T")
      (fields (field (name "MANUFACTURER") "EVERLIGHT(亿光)") (field (name "CONTRIBUTOR") "lcsc"))
      (libsource (lib "altium-import") (part "root_3_42-21A/GHC-YX1Y2N/1T_"))
    )
    (comp (ref "LED127")
      (value "42-21A/GHC-YX1Y2N/1T")
      (fields (field (name "MANUFACTURER") "EVERLIGHT(亿光)") (field (name "CONTRIBUTOR") "lcsc"))
      (libsource (lib "altium-import") (part "root_3_42-21A/GHC-YX1Y2N/1T_"))
    )
    (comp (ref "LED128")
      (value "42-21A/GHC-YX1Y2N/1T")
      (fields (field (name "MANUFACTURER") "EVERLIGHT(亿光)") (field (name "CONTRIBUTOR") "lcsc"))
      (libsource (lib "altium-import") (part "root_3_42-21A/GHC-YX1Y2N/1T_"))
    )
    (comp (ref "LED129")
      (value "42-21A/GHC-YX1Y2N/1T")
      (fields (field (name "MANUFACTURER") "EVERLIGHT(亿光)") (field (name "CONTRIBUTOR") "lcsc"))
      (libsource (lib "altium-import") (part "root_3_42-21A/GHC-YX1Y2N/1T_"))
    )
    (comp (ref "LED130")
      (value "42-21A/GHC-YX1Y2N/1T")
      (fields (field (name "MANUFACTURER") "EVERLIGHT(亿光)") (field (name "CONTRIBUTOR") "lcsc"))
      (libsource (lib "altium-import") (part "root_3_42-21A/GHC-YX1Y2N/1T_"))
    )
    (comp (ref "LED131")
      (value "42-21A/GHC-YX1Y2N/1T")
      (fields (field (name "MANUFACTURER") "EVERLIGHT(亿光)") (field (name "CONTRIBUTOR") "lcsc"))
      (libsource (lib "altium-import") (part "root_3_42-21A/GHC-YX1Y2N/1T_"))
    )
    (comp (ref "LED132")
      (value "42-21A/GHC-YX1Y2N/1T")
      (fields (field (name "MANUFACTURER") "EVERLIGHT(亿光)") (field (name "CONTRIBUTOR") "lcsc"))
      (libsource (lib "altium-import") (part "root_3_42-21A/GHC-YX1Y2N/1T_"))
    )
    (comp (ref "LED133")
      (value "42-21A/GHC-YX1Y2N/1T")
      (fields (field (name "MANUFACTURER") "EVERLIGHT(亿光)") (field (name "CONTRIBUTOR") "lcsc"))
      (libsource (lib "altium-import") (part "root_3_42-21A/GHC-YX1Y2N/1T_"))
    )
    (comp (ref "LED134")
      (value "42-21A/GHC-YX1Y2N/1T")
      (fields (field (name "MANUFACTURER") "EVERLIGHT(亿光)") (field (name "CONTRIBUTOR") "lcsc"))
      (libsource (lib "altium-import") (part "root_3_42-21A/GHC-YX1Y2N/1T_"))
    )
    (comp (ref "LED135")
      (value "42-21A/GHC-YX1Y2N/1T")
      (fields (field (name "MANUFACTURER") "EVERLIGHT(亿光)") (field (name "CONTRIBUTOR") "lcsc"))
      (libsource (lib "altium-import") (part "root_3_42-21A/GHC-YX1Y2N/1T_"))
    )
    (comp (ref "LED136")
      (value "42-21A/GHC-YX1Y2N/1T")
      (fields (field (name "MANUFACTURER") "EVERLIGHT(亿光)") (field (name "CONTRIBUTOR") "lcsc"))
      (libsource (lib "altium-import") (part "root_3_42-21A/GHC-YX1Y2N/1T_"))
    )
    (comp (ref "LED137")
      (value "42-21A/GHC-YX1Y2N/1T")
      (fields (field (name "MANUFACTURER") "EVERLIGHT(亿光)") (field (name "CONTRIBUTOR") "lcsc"))
      (libsource (lib "altium-import") (part "root_3_42-21A/GHC-YX1Y2N/1T_"))
    )
    (comp (ref "LED138")
      (value "42-21A/GHC-YX1Y2N/1T")
      (fields (field (name "MANUFACTURER") "EVERLIGHT(亿光)") (field (name "CONTRIBUTOR") "lcsc"))
      (libsource (lib "altium-import") (part "root_3_42-21A/GHC-YX1Y2N/1T_"))
    )
    (comp (ref "LED139")
      (value "42-21A/GHC-YX1Y2N/1T")
      (fields (field (name "MANUFACTURER") "EVERLIGHT(亿光)") (field (name "CONTRIBUTOR") "lcsc"))
      (libsource (lib "altium-import") (part "root_3_42-21A/GHC-YX1Y2N/1T_"))
    )
    (comp (ref "LED140")
      (value "42-21A/GHC-YX1Y2N/1T")
      (fields (field (name "MANUFACTURER") "EVERLIGHT(亿光)") (field (name "CONTRIBUTOR") "lcsc"))
      (libsource (lib "altium-import") (part "root_3_42-21A/GHC-YX1Y2N/1T_"))
    )
    (comp (ref "LED141")
      (value "42-21A/GHC-YX1Y2N/1T")
      (fields (field (name "MANUFACTURER") "EVERLIGHT(亿光)") (field (name "CONTRIBUTOR") "lcsc"))
      (libsource (lib "altium-import") (part "root_3_42-21A/GHC-YX1Y2N/1T_"))
    )
    (comp (ref "LED142")
      (value "42-21A/GHC-YX1Y2N/1T")
      (fields (field (name "MANUFACTURER") "EVERLIGHT(亿光)") (field (name "CONTRIBUTOR") "lcsc"))
      (libsource (lib "altium-import") (part "root_3_42-21A/GHC-YX1Y2N/1T_"))
    )
    (comp (ref "LED143")
      (value "42-21A/GHC-YX1Y2N/1T")
      (fields (field (name "MANUFACTURER") "EVERLIGHT(亿光)") (field (name "CONTRIBUTOR") "lcsc"))
      (libsource (lib "altium-import") (part "root_3_42-21A/GHC-YX1Y2N/1T_"))
    )
    (comp (ref "LED144")
      (value "42-21A/GHC-YX1Y2N/1T")
      (fields (field (name "MANUFACTURER") "EVERLIGHT(亿光)") (field (name "CONTRIBUTOR") "lcsc"))
      (libsource (lib "altium-import") (part "root_3_42-21A/GHC-YX1Y2N/1T_"))
    )
    (comp (ref "LED145")
      (value "42-21A/GHC-YX1Y2N/1T")
      (fields (field (name "MANUFACTURER") "EVERLIGHT(亿光)") (field (name "CONTRIBUTOR") "lcsc"))
      (libsource (lib "altium-import") (part "root_3_42-21A/GHC-YX1Y2N/1T_"))
    )
    (comp (ref "LED146")
      (value "42-21A/GHC-YX1Y2N/1T")
      (fields (field (name "MANUFACTURER") "EVERLIGHT(亿光)") (field (name "CONTRIBUTOR") "lcsc"))
      (libsource (lib "altium-import") (part "root_3_42-21A/GHC-YX1Y2N/1T_"))
    )
    (comp (ref "LED147")
      (value "42-21A/GHC-YX1Y2N/1T")
      (fields (field (name "MANUFACTURER") "EVERLIGHT(亿光)") (field (name "CONTRIBUTOR") "lcsc"))
      (libsource (lib "altium-import") (part "root_3_42-21A/GHC-YX1Y2N/1T_"))
    )
    (comp (ref "LED148")
      (value "42-21A/GHC-YX1Y2N/1T")
      (fields (field (name "MANUFACTURER") "EVERLIGHT(亿光)") (field (name "CONTRIBUTOR") "lcsc"))
      (libsource (lib "altium-import") (part "root_3_42-21A/GHC-YX1Y2N/1T_"))
    )
    (comp (ref "LED149")
      (value "42-21A/GHC-YX1Y2N/1T")
      (fields (field (name "MANUFACTURER") "EVERLIGHT(亿光)") (field (name "CONTRIBUTOR") "lcsc"))
      (libsource (lib "altium-import") (part "root_3_42-21A/GHC-YX1Y2N/1T_"))
    )
    (comp (ref "LED150")
      (value "42-21A/GHC-YX1Y2N/1T")
      (fields (field (name "MANUFACTURER") "EVERLIGHT(亿光)") (field (name "CONTRIBUTOR") "lcsc"))
      (libsource (lib "altium-import") (part "root_3_42-21A/GHC-YX1Y2N/1T_"))
    )
    (comp (ref "LED151")
      (value "42-21A/GHC-YX1Y2N/1T")
      (fields (field (name "MANUFACTURER") "EVERLIGHT(亿光)") (field (name "CONTRIBUTOR") "lcsc"))
      (libsource (lib "altium-import") (part "root_3_42-21A/GHC-YX1Y2N/1T_"))
    )
    (comp (ref "LED152")
      (value "42-21A/GHC-YX1Y2N/1T")
      (fields (field (name "MANUFACTURER") "EVERLIGHT(亿光)") (field (name "CONTRIBUTOR") "lcsc"))
      (libsource (lib "altium-import") (part "root_3_42-21A/GHC-YX1Y2N/1T_"))
    )
    (comp (ref "LED153")
      (value "42-21A/GHC-YX1Y2N/1T")
      (fields (field (name "MANUFACTURER") "EVERLIGHT(亿光)") (field (name "CONTRIBUTOR") "lcsc"))
      (libsource (lib "altium-import") (part "root_3_42-21A/GHC-YX1Y2N/1T_"))
    )
    (comp (ref "LED154")
      (value "42-21A/GHC-YX1Y2N/1T")
      (fields (field (name "MANUFACTURER") "EVERLIGHT(亿光)") (field (name "CONTRIBUTOR") "lcsc"))
      (libsource (lib "altium-import") (part "root_3_42-21A/GHC-YX1Y2N/1T_"))
    )
    (comp (ref "LED155")
      (value "42-21A/GHC-YX1Y2N/1T")
      (fields (field (name "MANUFACTURER") "EVERLIGHT(亿光)") (field (name "CONTRIBUTOR") "lcsc"))
      (libsource (lib "altium-import") (part "root_3_42-21A/GHC-YX1Y2N/1T_"))
    )
    (comp (ref "LED156")
      (value "42-21A/GHC-YX1Y2N/1T")
      (fields (field (name "MANUFACTURER") "EVERLIGHT(亿光)") (field (name "CONTRIBUTOR") "lcsc"))
      (libsource (lib "altium-import") (part "root_3_42-21A/GHC-YX1Y2N/1T_"))
    )
    (comp (ref "LED157")
      (value "42-21A/GHC-YX1Y2N/1T")
      (fields (field (name "MANUFACTURER") "EVERLIGHT(亿光)") (field (name "CONTRIBUTOR") "lcsc"))
      (libsource (lib "altium-import") (part "root_3_42-21A/GHC-YX1Y2N/1T_"))
    )
    (comp (ref "LED158")
      (value "42-21A/GHC-YX1Y2N/1T")
      (fields (field (name "MANUFACTURER") "EVERLIGHT(亿光)") (field (name "CONTRIBUTOR") "lcsc"))
      (libsource (lib "altium-import") (part "root_3_42-21A/GHC-YX1Y2N/1T_"))
    )
    (comp (ref "LED159")
      (value "42-21A/GHC-YX1Y2N/1T")
      (fields (field (name "MANUFACTURER") "EVERLIGHT(亿光)") (field (name "CONTRIBUTOR") "lcsc"))
      (libsource (lib "altium-import") (part "root_3_42-21A/GHC-YX1Y2N/1T_"))
    )
    (comp (ref "LED160")
      (value "42-21A/GHC-YX1Y2N/1T")
      (fields (field (name "MANUFACTURER") "EVERLIGHT(亿光)") (field (name "CONTRIBUTOR") "lcsc"))
      (libsource (lib "altium-import") (part "root_3_42-21A/GHC-YX1Y2N/1T_"))
    )
    (comp (ref "LED161")
      (value "42-21A/GHC-YX1Y2N/1T")
      (fields (field (name "MANUFACTURER") "EVERLIGHT(亿光)") (field (name "CONTRIBUTOR") "lcsc"))
      (libsource (lib "altium-import") (part "root_3_42-21A/GHC-YX1Y2N/1T_"))
    )
    (comp (ref "LED162")
      (value "42-21A/GHC-YX1Y2N/1T")
      (fields (field (name "MANUFACTURER") "EVERLIGHT(亿光)") (field (name "CONTRIBUTOR") "lcsc"))
      (libsource (lib "altium-import") (part "root_3_42-21A/GHC-YX1Y2N/1T_"))
    )
    (comp (ref "LED163")
      (value "42-21A/GHC-YX1Y2N/1T")
      (fields (field (name "MANUFACTURER") "EVERLIGHT(亿光)") (field (name "CONTRIBUTOR") "lcsc"))
      (libsource (lib "altium-import") (part "root_3_42-21A/GHC-YX1Y2N/1T_"))
    )
    (comp (ref "LED164")
      (value "42-21A/GHC-YX1Y2N/1T")
      (fields (field (name "MANUFACTURER") "EVERLIGHT(亿光)") (field (name "CONTRIBUTOR") "lcsc"))
      (libsource (lib "altium-import") (part "root_3_42-21A/GHC-YX1Y2N/1T_"))
    )
    (comp (ref "LED165")
      (value "42-21A/GHC-YX1Y2N/1T")
      (fields (field (name "MANUFACTURER") "EVERLIGHT(亿光)") (field (name "CONTRIBUTOR") "lcsc"))
      (libsource (lib "altium-import") (part "root_3_42-21A/GHC-YX1Y2N/1T_"))
    )
    (comp (ref "LED166")
      (value "42-21A/GHC-YX1Y2N/1T")
      (fields (field (name "MANUFACTURER") "EVERLIGHT(亿光)") (field (name "CONTRIBUTOR") "lcsc"))
      (libsource (lib "altium-import") (part "root_3_42-21A/GHC-YX1Y2N/1T_"))
    )
    (comp (ref "LED167")
      (value "42-21A/GHC-YX1Y2N/1T")
      (fields (field (name "MANUFACTURER") "EVERLIGHT(亿光)") (field (name "CONTRIBUTOR") "lcsc"))
      (libsource (lib "altium-import") (part "root_3_42-21A/GHC-YX1Y2N/1T_"))
    )
    (comp (ref "LED168")
      (value "42-21A/GHC-YX1Y2N/1T")
      (fields (field (name "MANUFACTURER") "EVERLIGHT(亿光)") (field (name "CONTRIBUTOR") "lcsc"))
      (libsource (lib "altium-import") (part "root_3_42-21A/GHC-YX1Y2N/1T_"))
    )
    (comp (ref "LED169")
      (value "42-21A/GHC-YX1Y2N/1T")
      (fields (field (name "MANUFACTURER") "EVERLIGHT(亿光)") (field (name "CONTRIBUTOR") "lcsc"))
      (libsource (lib "altium-import") (part "root_3_42-21A/GHC-YX1Y2N/1T_"))
    )
    (comp (ref "LED170")
      (value "42-21A/GHC-YX1Y2N/1T")
      (fields (field (name "MANUFACTURER") "EVERLIGHT(亿光)") (field (name "CONTRIBUTOR") "lcsc"))
      (libsource (lib "altium-import") (part "root_3_42-21A/GHC-YX1Y2N/1T_"))
    )
    (comp (ref "LED171")
      (value "42-21A/GHC-YX1Y2N/1T")
      (fields (field (name "MANUFACTURER") "EVERLIGHT(亿光)") (field (name "CONTRIBUTOR") "lcsc"))
      (libsource (lib "altium-import") (part "root_3_42-21A/GHC-YX1Y2N/1T_"))
    )
    (comp (ref "LED172")
      (value "42-21A/GHC-YX1Y2N/1T")
      (fields (field (name "MANUFACTURER") "EVERLIGHT(亿光)") (field (name "CONTRIBUTOR") "lcsc"))
      (libsource (lib "altium-import") (part "root_3_42-21A/GHC-YX1Y2N/1T_"))
    )
    (comp (ref "LED173")
      (value "42-21A/GHC-YX1Y2N/1T")
      (fields (field (name "MANUFACTURER") "EVERLIGHT(亿光)") (field (name "CONTRIBUTOR") "lcsc"))
      (libsource (lib "altium-import") (part "root_3_42-21A/GHC-YX1Y2N/1T_"))
    )
    (comp (ref "LED174")
      (value "42-21A/GHC-YX1Y2N/1T")
      (fields (field (name "MANUFACTURER") "EVERLIGHT(亿光)") (field (name "CONTRIBUTOR") "lcsc"))
      (libsource (lib "altium-import") (part "root_3_42-21A/GHC-YX1Y2N/1T_"))
    )
    (comp (ref "LED175")
      (value "42-21A/GHC-YX1Y2N/1T")
      (fields (field (name "MANUFACTURER") "EVERLIGHT(亿光)") (field (name "CONTRIBUTOR") "lcsc"))
      (libsource (lib "altium-import") (part "root_3_42-21A/GHC-YX1Y2N/1T_"))
    )
    (comp (ref "LED176")
      (value "42-21A/GHC-YX1Y2N/1T")
      (fields (field (name "MANUFACTURER") "EVERLIGHT(亿光)") (field (name "CONTRIBUTOR") "lcsc"))
      (libsource (lib "altium-import") (part "root_3_42-21A/GHC-YX1Y2N/1T_"))
    )
    (comp (ref "LED177")
      (value "42-21A/GHC-YX1Y2N/1T")
      (fields (field (name "MANUFACTURER") "EVERLIGHT(亿光)") (field (name "CONTRIBUTOR") "lcsc"))
      (libsource (lib "altium-import") (part "root_3_42-21A/GHC-YX1Y2N/1T_"))
    )
    (comp (ref "LED178")
      (value "42-21A/GHC-YX1Y2N/1T")
      (fields (field (name "MANUFACTURER") "EVERLIGHT(亿光)") (field (name "CONTRIBUTOR") "lcsc"))
      (libsource (lib "altium-import") (part "root_3_42-21A/GHC-YX1Y2N/1T_"))
    )
    (comp (ref "LED179")
      (value "42-21A/GHC-YX1Y2N/1T")
      (fields (field (name "MANUFACTURER") "EVERLIGHT(亿光)") (field (name "CONTRIBUTOR") "lcsc"))
      (libsource (lib "altium-import") (part "root_3_42-21A/GHC-YX1Y2N/1T_"))
    )
    (comp (ref "LED180")
      (value "42-21A/GHC-YX1Y2N/1T")
      (fields (field (name "MANUFACTURER") "EVERLIGHT(亿光)") (field (name "CONTRIBUTOR") "lcsc"))
      (libsource (lib "altium-import") (part "root_3_42-21A/GHC-YX1Y2N/1T_"))
    )
    (comp (ref "LED181")
      (value "42-21A/GHC-YX1Y2N/1T")
      (fields (field (name "MANUFACTURER") "EVERLIGHT(亿光)") (field (name "CONTRIBUTOR") "lcsc"))
      (libsource (lib "altium-import") (part "root_3_42-21A/GHC-YX1Y2N/1T_"))
    )
    (comp (ref "LED182")
      (value "42-21A/GHC-YX1Y2N/1T")
      (fields (field (name "MANUFACTURER") "EVERLIGHT(亿光)") (field (name "CONTRIBUTOR") "lcsc"))
      (libsource (lib "altium-import") (part "root_3_42-21A/GHC-YX1Y2N/1T_"))
    )
    (comp (ref "LED183")
      (value "42-21A/GHC-YX1Y2N/1T")
      (fields (field (name "MANUFACTURER") "EVERLIGHT(亿光)") (field (name "CONTRIBUTOR") "lcsc"))
      (libsource (lib "altium-import") (part "root_3_42-21A/GHC-YX1Y2N/1T_"))
    )
    (comp (ref "LED184")
      (value "42-21A/GHC-YX1Y2N/1T")
      (fields (field (name "MANUFACTURER") "EVERLIGHT(亿光)") (field (name "CONTRIBUTOR") "lcsc"))
      (libsource (lib "altium-import") (part "root_3_42-21A/GHC-YX1Y2N/1T_"))
    )
    (comp (ref "LED185")
      (value "42-21A/GHC-YX1Y2N/1T")
      (fields (field (name "MANUFACTURER") "EVERLIGHT(亿光)") (field (name "CONTRIBUTOR") "lcsc"))
      (libsource (lib "altium-import") (part "root_3_42-21A/GHC-YX1Y2N/1T_"))
    )
    (comp (ref "LED186")
      (value "42-21A/GHC-YX1Y2N/1T")
      (fields (field (name "MANUFACTURER") "EVERLIGHT(亿光)") (field (name "CONTRIBUTOR") "lcsc"))
      (libsource (lib "altium-import") (part "root_3_42-21A/GHC-YX1Y2N/1T_"))
    )
    (comp (ref "LED187")
      (value "42-21A/GHC-YX1Y2N/1T")
      (fields (field (name "MANUFACTURER") "EVERLIGHT(亿光)") (field (name "CONTRIBUTOR") "lcsc"))
      (libsource (lib "altium-import") (part "root_3_42-21A/GHC-YX1Y2N/1T_"))
    )
    (comp (ref "LED188")
      (value "42-21A/GHC-YX1Y2N/1T")
      (fields (field (name "MANUFACTURER") "EVERLIGHT(亿光)") (field (name "CONTRIBUTOR") "lcsc"))
      (libsource (lib "altium-import") (part "root_3_42-21A/GHC-YX1Y2N/1T_"))
    )
    (comp (ref "LED189")
      (value "42-21A/GHC-YX1Y2N/1T")
      (fields (field (name "MANUFACTURER") "EVERLIGHT(亿光)") (field (name "CONTRIBUTOR") "lcsc"))
      (libsource (lib "altium-import") (part "root_3_42-21A/GHC-YX1Y2N/1T_"))
    )
    (comp (ref "LED190")
      (value "42-21A/GHC-YX1Y2N/1T")
      (fields (field (name "MANUFACTURER") "EVERLIGHT(亿光)") (field (name "CONTRIBUTOR") "lcsc"))
      (libsource (lib "altium-import") (part "root_3_42-21A/GHC-YX1Y2N/1T_"))
    )
    (comp (ref "LED191")
      (value "42-21A/GHC-YX1Y2N/1T")
      (fields (field (name "MANUFACTURER") "EVERLIGHT(亿光)") (field (name "CONTRIBUTOR") "lcsc"))
      (libsource (lib "altium-import") (part "root_3_42-21A/GHC-YX1Y2N/1T_"))
    )
    (comp (ref "LED192")
      (value "42-21A/GHC-YX1Y2N/1T")
      (fields (field (name "MANUFACTURER") "EVERLIGHT(亿光)") (field (name "CONTRIBUTOR") "lcsc"))
      (libsource (lib "altium-import") (part "root_3_42-21A/GHC-YX1Y2N/1T_"))
    )
    (comp (ref "LED193")
      (value "42-21A/GHC-YX1Y2N/1T")
      (fields (field (name "MANUFACTURER") "EVERLIGHT(亿光)") (field (name "CONTRIBUTOR") "lcsc"))
      (libsource (lib "altium-import") (part "root_3_42-21A/GHC-YX1Y2N/1T_"))
    )
    (comp (ref "LED194")
      (value "42-21A/GHC-YX1Y2N/1T")
      (fields (field (name "MANUFACTURER") "EVERLIGHT(亿光)") (field (name "CONTRIBUTOR") "lcsc"))
      (libsource (lib "altium-import") (part "root_3_42-21A/GHC-YX1Y2N/1T_"))
    )
    (comp (ref "LED195")
      (value "42-21A/GHC-YX1Y2N/1T")
      (fields (field (name "MANUFACTURER") "EVERLIGHT(亿光)") (field (name "CONTRIBUTOR") "lcsc"))
      (libsource (lib "altium-import") (part "root_3_42-21A/GHC-YX1Y2N/1T_"))
    )
    (comp (ref "LED196")
      (value "42-21A/GHC-YX1Y2N/1T")
      (fields (field (name "MANUFACTURER") "EVERLIGHT(亿光)") (field (name "CONTRIBUTOR") "lcsc"))
      (libsource (lib "altium-import") (part "root_3_42-21A/GHC-YX1Y2N/1T_"))
    )
    (comp (ref "LED197")
      (value "42-21A/GHC-YX1Y2N/1T")
      (fields (field (name "MANUFACTURER") "EVERLIGHT(亿光)") (field (name "CONTRIBUTOR") "lcsc"))
      (libsource (lib "altium-import") (part "root_3_42-21A/GHC-YX1Y2N/1T_"))
    )
    (comp (ref "LED198")
      (value "42-21A/GHC-YX1Y2N/1T")
      (fields (field (name "MANUFACTURER") "EVERLIGHT(亿光)") (field (name "CONTRIBUTOR") "lcsc"))
      (libsource (lib "altium-import") (part "root_3_42-21A/GHC-YX1Y2N/1T_"))
    )
    (comp (ref "LED199")
      (value "42-21A/GHC-YX1Y2N/1T")
      (fields (field (name "MANUFACTURER") "EVERLIGHT(亿光)") (field (name "CONTRIBUTOR") "lcsc"))
      (libsource (lib "altium-import") (part "root_3_42-21A/GHC-YX1Y2N/1T_"))
    )
    (comp (ref "LED200")
      (value "42-21A/GHC-YX1Y2N/1T")
      (fields (field (name "MANUFACTURER") "EVERLIGHT(亿光)") (field (name "CONTRIBUTOR") "lcsc"))
      (libsource (lib "altium-import") (part "root_3_42-21A/GHC-YX1Y2N/1T_"))
    )
    (comp (ref "LED201")
      (value "42-21A/GHC-YX1Y2N/1T")
      (fields (field (name "MANUFACTURER") "EVERLIGHT(亿光)") (field (name "CONTRIBUTOR") "lcsc"))
      (libsource (lib "altium-import") (part "root_3_42-21A/GHC-YX1Y2N/1T_"))
    )
    (comp (ref "LED202")
      (value "42-21A/GHC-YX1Y2N/1T")
      (fields (field (name "MANUFACTURER") "EVERLIGHT(亿光)") (field (name "CONTRIBUTOR") "lcsc"))
      (libsource (lib "altium-import") (part "root_3_42-21A/GHC-YX1Y2N/1T_"))
    )
    (comp (ref "LED203")
      (value "42-21A/GHC-YX1Y2N/1T")
      (fields (field (name "MANUFACTURER") "EVERLIGHT(亿光)") (field (name "CONTRIBUTOR") "lcsc"))
      (libsource (lib "altium-import") (part "root_3_42-21A/GHC-YX1Y2N/1T_"))
    )
    (comp (ref "LED204")
      (value "42-21A/GHC-YX1Y2N/1T")
      (fields (field (name "MANUFACTURER") "EVERLIGHT(亿光)") (field (name "CONTRIBUTOR") "lcsc"))
      (libsource (lib "altium-import") (part "root_3_42-21A/GHC-YX1Y2N/1T_"))
    )
    (comp (ref "LED205")
      (value "42-21A/GHC-YX1Y2N/1T")
      (fields (field (name "MANUFACTURER") "EVERLIGHT(亿光)") (field (name "CONTRIBUTOR") "lcsc"))
      (libsource (lib "altium-import") (part "root_3_42-21A/GHC-YX1Y2N/1T_"))
    )
    (comp (ref "LED206")
      (value "42-21A/GHC-YX1Y2N/1T")
      (fields (field (name "MANUFACTURER") "EVERLIGHT(亿光)") (field (name "CONTRIBUTOR") "lcsc"))
      (libsource (lib "altium-import") (part "root_3_42-21A/GHC-YX1Y2N/1T_"))
    )
    (comp (ref "LED207")
      (value "42-21A/GHC-YX1Y2N/1T")
      (fields (field (name "MANUFACTURER") "EVERLIGHT(亿光)") (field (name "CONTRIBUTOR") "lcsc"))
      (libsource (lib "altium-import") (part "root_3_42-21A/GHC-YX1Y2N/1T_"))
    )
    (comp (ref "LED208")
      (value "42-21A/GHC-YX1Y2N/1T")
      (fields (field (name "MANUFACTURER") "EVERLIGHT(亿光)") (field (name "CONTRIBUTOR") "lcsc"))
      (libsource (lib "altium-import") (part "root_3_42-21A/GHC-YX1Y2N/1T_"))
    )
    (comp (ref "LED209")
      (value "42-21A/GHC-YX1Y2N/1T")
      (fields (field (name "MANUFACTURER") "EVERLIGHT(亿光)") (field (name "CONTRIBUTOR") "lcsc"))
      (libsource (lib "altium-import") (part "root_3_42-21A/GHC-YX1Y2N/1T_"))
    )
    (comp (ref "LED210")
      (value "42-21A/GHC-YX1Y2N/1T")
      (fields (field (name "MANUFACTURER") "EVERLIGHT(亿光)") (field (name "CONTRIBUTOR") "lcsc"))
      (libsource (lib "altium-import") (part "root_3_42-21A/GHC-YX1Y2N/1T_"))
    )
    (comp (ref "LED211")
      (value "42-21A/GHC-YX1Y2N/1T")
      (fields (field (name "MANUFACTURER") "EVERLIGHT(亿光)") (field (name "CONTRIBUTOR") "lcsc"))
      (libsource (lib "altium-import") (part "root_3_42-21A/GHC-YX1Y2N/1T_"))
    )
    (comp (ref "LED212")
      (value "42-21A/GHC-YX1Y2N/1T")
      (fields (field (name "MANUFACTURER") "EVERLIGHT(亿光)") (field (name "CONTRIBUTOR") "lcsc"))
      (libsource (lib "altium-import") (part "root_3_42-21A/GHC-YX1Y2N/1T_"))
    )
    (comp (ref "LED213")
      (value "42-21A/GHC-YX1Y2N/1T")
      (fields (field (name "MANUFACTURER") "EVERLIGHT(亿光)") (field (name "CONTRIBUTOR") "lcsc"))
      (libsource (lib "altium-import") (part "root_3_42-21A/GHC-YX1Y2N/1T_"))
    )
    (comp (ref "LED214")
      (value "42-21A/GHC-YX1Y2N/1T")
      (fields (field (name "MANUFACTURER") "EVERLIGHT(亿光)") (field (name "CONTRIBUTOR") "lcsc"))
      (libsource (lib "altium-import") (part "root_3_42-21A/GHC-YX1Y2N/1T_"))
    )
    (comp (ref "LED215")
      (value "42-21A/GHC-YX1Y2N/1T")
      (fields (field (name "MANUFACTURER") "EVERLIGHT(亿光)") (field (name "CONTRIBUTOR") "lcsc"))
      (libsource (lib "altium-import") (part "root_3_42-21A/GHC-YX1Y2N/1T_"))
    )
    (comp (ref "LED216")
      (value "42-21A/GHC-YX1Y2N/1T")
      (fields (field (name "MANUFACTURER") "EVERLIGHT(亿光)") (field (name "CONTRIBUTOR") "lcsc"))
      (libsource (lib "altium-import") (part "root_3_42-21A/GHC-YX1Y2N/1T_"))
    )
    (comp (ref "LED217")
      (value "42-21A/GHC-YX1Y2N/1T")
      (fields (field (name "MANUFACTURER") "EVERLIGHT(亿光)") (field (name "CONTRIBUTOR") "lcsc"))
      (libsource (lib "altium-import") (part "root_3_42-21A/GHC-YX1Y2N/1T_"))
    )
    (comp (ref "LED218")
      (value "42-21A/GHC-YX1Y2N/1T")
      (fields (field (name "MANUFACTURER") "EVERLIGHT(亿光)") (field (name "CONTRIBUTOR") "lcsc"))
      (libsource (lib "altium-import") (part "root_3_42-21A/GHC-YX1Y2N/1T_"))
    )
    (comp (ref "LED219")
      (value "42-21A/GHC-YX1Y2N/1T")
      (fields (field (name "MANUFACTURER") "EVERLIGHT(亿光)") (field (name "CONTRIBUTOR") "lcsc"))
      (libsource (lib "altium-import") (part "root_3_42-21A/GHC-YX1Y2N/1T_"))
    )
    (comp (ref "LED220")
      (value "42-21A/GHC-YX1Y2N/1T")
      (fields (field (name "MANUFACTURER") "EVERLIGHT(亿光)") (field (name "CONTRIBUTOR") "lcsc"))
      (libsource (lib "altium-import") (part "root_3_42-21A/GHC-YX1Y2N/1T_"))
    )
    (comp (ref "LED221")
      (value "42-21A/GHC-YX1Y2N/1T")
      (fields (field (name "MANUFACTURER") "EVERLIGHT(亿光)") (field (name "CONTRIBUTOR") "lcsc"))
      (libsource (lib "altium-import") (part "root_3_42-21A/GHC-YX1Y2N/1T_"))
    )
    (comp (ref "LED222")
      (value "42-21A/GHC-YX1Y2N/1T")
      (fields (field (name "MANUFACTURER") "EVERLIGHT(亿光)") (field (name "CONTRIBUTOR") "lcsc"))
      (libsource (lib "altium-import") (part "root_3_42-21A/GHC-YX1Y2N/1T_"))
    )
    (comp (ref "LED223")
      (value "42-21A/GHC-YX1Y2N/1T")
      (fields (field (name "MANUFACTURER") "EVERLIGHT(亿光)") (field (name "CONTRIBUTOR") "lcsc"))
      (libsource (lib "altium-import") (part "root_3_42-21A/GHC-YX1Y2N/1T_"))
    )
    (comp (ref "LED224")
      (value "42-21A/GHC-YX1Y2N/1T")
      (fields (field (name "MANUFACTURER") "EVERLIGHT(亿光)") (field (name "CONTRIBUTOR") "lcsc"))
      (libsource (lib "altium-import") (part "root_3_42-21A/GHC-YX1Y2N/1T_"))
    )
    (comp (ref "LED225")
      (value "42-21A/GHC-YX1Y2N/1T")
      (fields (field (name "MANUFACTURER") "EVERLIGHT(亿光)") (field (name "CONTRIBUTOR") "lcsc"))
      (libsource (lib "altium-import") (part "root_3_42-21A/GHC-YX1Y2N/1T_"))
    )
    (comp (ref "LED226")
      (value "42-21A/GHC-YX1Y2N/1T")
      (fields (field (name "MANUFACTURER") "EVERLIGHT(亿光)") (field (name "CONTRIBUTOR") "lcsc"))
      (libsource (lib "altium-import") (part "root_3_42-21A/GHC-YX1Y2N/1T_"))
    )
    (comp (ref "LED227")
      (value "42-21A/GHC-YX1Y2N/1T")
      (fields (field (name "MANUFACTURER") "EVERLIGHT(亿光)") (field (name "CONTRIBUTOR") "lcsc"))
      (libsource (lib "altium-import") (part "root_3_42-21A/GHC-YX1Y2N/1T_"))
    )
    (comp (ref "LED228")
      (value "42-21A/GHC-YX1Y2N/1T")
      (fields (field (name "MANUFACTURER") "EVERLIGHT(亿光)") (field (name "CONTRIBUTOR") "lcsc"))
      (libsource (lib "altium-import") (part "root_3_42-21A/GHC-YX1Y2N/1T_"))
    )
    (comp (ref "LED229")
      (value "42-21A/GHC-YX1Y2N/1T")
      (fields (field (name "MANUFACTURER") "EVERLIGHT(亿光)") (field (name "CONTRIBUTOR") "lcsc"))
      (libsource (lib "altium-import") (part "root_3_42-21A/GHC-YX1Y2N/1T_"))
    )
    (comp (ref "LED230")
      (value "42-21A/GHC-YX1Y2N/1T")
      (fields (field (name "MANUFACTURER") "EVERLIGHT(亿光)") (field (name "CONTRIBUTOR") "lcsc"))
      (libsource (lib "altium-import") (part "root_3_42-21A/GHC-YX1Y2N/1T_"))
    )
    (comp (ref "LED231")
      (value "42-21A/GHC-YX1Y2N/1T")
      (fields (field (name "MANUFACTURER") "EVERLIGHT(亿光)") (field (name "CONTRIBUTOR") "lcsc"))
      (libsource (lib "altium-import") (part "root_3_42-21A/GHC-YX1Y2N/1T_"))
    )
    (comp (ref "LED232")
      (value "42-21A/GHC-YX1Y2N/1T")
      (fields (field (name "MANUFACTURER") "EVERLIGHT(亿光)") (field (name "CONTRIBUTOR") "lcsc"))
      (libsource (lib "altium-import") (part "root_3_42-21A/GHC-YX1Y2N/1T_"))
    )
    (comp (ref "LED233")
      (value "42-21A/GHC-YX1Y2N/1T")
      (fields (field (name "MANUFACTURER") "EVERLIGHT(亿光)") (field (name "CONTRIBUTOR") "lcsc"))
      (libsource (lib "altium-import") (part "root_3_42-21A/GHC-YX1Y2N/1T_"))
    )
    (comp (ref "LED234")
      (value "42-21A/GHC-YX1Y2N/1T")
      (fields (field (name "MANUFACTURER") "EVERLIGHT(亿光)") (field (name "CONTRIBUTOR") "lcsc"))
      (libsource (lib "altium-import") (part "root_3_42-21A/GHC-YX1Y2N/1T_"))
    )
    (comp (ref "LED235")
      (value "42-21A/GHC-YX1Y2N/1T")
      (fields (field (name "MANUFACTURER") "EVERLIGHT(亿光)") (field (name "CONTRIBUTOR") "lcsc"))
      (libsource (lib "altium-import") (part "root_3_42-21A/GHC-YX1Y2N/1T_"))
    )
    (comp (ref "LED236")
      (value "42-21A/GHC-YX1Y2N/1T")
      (fields (field (name "MANUFACTURER") "EVERLIGHT(亿光)") (field (name "CONTRIBUTOR") "lcsc"))
      (libsource (lib "altium-import") (part "root_3_42-21A/GHC-YX1Y2N/1T_"))
    )
    (comp (ref "LED237")
      (value "42-21A/GHC-YX1Y2N/1T")
      (fields (field (name "MANUFACTURER") "EVERLIGHT(亿光)") (field (name "CONTRIBUTOR") "lcsc"))
      (libsource (lib "altium-import") (part "root_3_42-21A/GHC-YX1Y2N/1T_"))
    )
    (comp (ref "LED238")
      (value "42-21A/GHC-YX1Y2N/1T")
      (fields (field (name "MANUFACTURER") "EVERLIGHT(亿光)") (field (name "CONTRIBUTOR") "lcsc"))
      (libsource (lib "altium-import") (part "root_3_42-21A/GHC-YX1Y2N/1T_"))
    )
    (comp (ref "LED239")
      (value "42-21A/GHC-YX1Y2N/1T")
      (fields (field (name "MANUFACTURER") "EVERLIGHT(亿光)") (field (name "CONTRIBUTOR") "lcsc"))
      (libsource (lib "altium-import") (part "root_3_42-21A/GHC-YX1Y2N/1T_"))
    )
    (comp (ref "LED240")
      (value "42-21A/GHC-YX1Y2N/1T")
      (fields (field (name "MANUFACTURER") "EVERLIGHT(亿光)") (field (name "CONTRIBUTOR") "lcsc"))
      (libsource (lib "altium-import") (part "root_3_42-21A/GHC-YX1Y2N/1T_"))
    )
    (comp (ref "LED241")
      (value "42-21A/GHC-YX1Y2N/1T")
      (fields (field (name "MANUFACTURER") "EVERLIGHT(亿光)") (field (name "CONTRIBUTOR") "lcsc"))
      (libsource (lib "altium-import") (part "root_3_42-21A/GHC-YX1Y2N/1T_"))
    )
    (comp (ref "LED242")
      (value "42-21A/GHC-YX1Y2N/1T")
      (fields (field (name "MANUFACTURER") "EVERLIGHT(亿光)") (field (name "CONTRIBUTOR") "lcsc"))
      (libsource (lib "altium-import") (part "root_3_42-21A/GHC-YX1Y2N/1T_"))
    )
    (comp (ref "LED243")
      (value "42-21A/GHC-YX1Y2N/1T")
      (fields (field (name "MANUFACTURER") "EVERLIGHT(亿光)") (field (name "CONTRIBUTOR") "lcsc"))
      (libsource (lib "altium-import") (part "root_3_42-21A/GHC-YX1Y2N/1T_"))
    )
    (comp (ref "LED244")
      (value "42-21A/GHC-YX1Y2N/1T")
      (fields (field (name "MANUFACTURER") "EVERLIGHT(亿光)") (field (name "CONTRIBUTOR") "lcsc"))
      (libsource (lib "altium-import") (part "root_3_42-21A/GHC-YX1Y2N/1T_"))
    )
    (comp (ref "LED245")
      (value "42-21A/GHC-YX1Y2N/1T")
      (fields (field (name "MANUFACTURER") "EVERLIGHT(亿光)") (field (name "CONTRIBUTOR") "lcsc"))
      (libsource (lib "altium-import") (part "root_3_42-21A/GHC-YX1Y2N/1T_"))
    )
    (comp (ref "LED246")
      (value "42-21A/GHC-YX1Y2N/1T")
      (fields (field (name "MANUFACTURER") "EVERLIGHT(亿光)") (field (name "CONTRIBUTOR") "lcsc"))
      (libsource (lib "altium-import") (part "root_3_42-21A/GHC-YX1Y2N/1T_"))
    )
    (comp (ref "LED247")
      (value "42-21A/GHC-YX1Y2N/1T")
      (fields (field (name "MANUFACTURER") "EVERLIGHT(亿光)") (field (name "CONTRIBUTOR") "lcsc"))
      (libsource (lib "altium-import") (part "root_3_42-21A/GHC-YX1Y2N/1T_"))
    )
    (comp (ref "LED248")
      (value "42-21A/GHC-YX1Y2N/1T")
      (fields (field (name "MANUFACTURER") "EVERLIGHT(亿光)") (field (name "CONTRIBUTOR") "lcsc"))
      (libsource (lib "altium-import") (part "root_3_42-21A/GHC-YX1Y2N/1T_"))
    )
    (comp (ref "LED249")
      (value "42-21A/GHC-YX1Y2N/1T")
      (fields (field (name "MANUFACTURER") "EVERLIGHT(亿光)") (field (name "CONTRIBUTOR") "lcsc"))
      (libsource (lib "altium-import") (part "root_3_42-21A/GHC-YX1Y2N/1T_"))
    )
    (comp (ref "LED250")
      (value "42-21A/GHC-YX1Y2N/1T")
      (fields (field (name "MANUFACTURER") "EVERLIGHT(亿光)") (field (name "CONTRIBUTOR") "lcsc"))
      (libsource (lib "altium-import") (part "root_3_42-21A/GHC-YX1Y2N/1T_"))
    )
    (comp (ref "LED251")
      (value "42-21A/GHC-YX1Y2N/1T")
      (fields (field (name "MANUFACTURER") "EVERLIGHT(亿光)") (field (name "CONTRIBUTOR") "lcsc"))
      (libsource (lib "altium-import") (part "root_3_42-21A/GHC-YX1Y2N/1T_"))
    )
    (comp (ref "LED252")
      (value "42-21A/GHC-YX1Y2N/1T")
      (fields (field (name "MANUFACTURER") "EVERLIGHT(亿光)") (field (name "CONTRIBUTOR") "lcsc"))
      (libsource (lib "altium-import") (part "root_3_42-21A/GHC-YX1Y2N/1T_"))
    )
    (comp (ref "LED253")
      (value "42-21A/GHC-YX1Y2N/1T")
      (fields (field (name "MANUFACTURER") "EVERLIGHT(亿光)") (field (name "CONTRIBUTOR") "lcsc"))
      (libsource (lib "altium-import") (part "root_3_42-21A/GHC-YX1Y2N/1T_"))
    )
    (comp (ref "LED254")
      (value "42-21A/GHC-YX1Y2N/1T")
      (fields (field (name "MANUFACTURER") "EVERLIGHT(亿光)") (field (name "CONTRIBUTOR") "lcsc"))
      (libsource (lib "altium-import") (part "root_3_42-21A/GHC-YX1Y2N/1T_"))
    )
    (comp (ref "LED255")
      (value "42-21A/GHC-YX1Y2N/1T")
      (fields (field (name "MANUFACTURER") "EVERLIGHT(亿光)") (field (name "CONTRIBUTOR") "lcsc"))
      (libsource (lib "altium-import") (part "root_3_42-21A/GHC-YX1Y2N/1T_"))
    )
    (comp (ref "LED256")
      (value "42-21A/GHC-YX1Y2N/1T")
      (fields (field (name "MANUFACTURER") "EVERLIGHT(亿光)") (field (name "CONTRIBUTOR") "lcsc"))
      (libsource (lib "altium-import") (part "root_3_42-21A/GHC-YX1Y2N/1T_"))
    )
    (comp (ref "Q1")
      (value "IRLZ44NPBF-MNS")
      (fields (field (name "MANUFACTURER") "minos(迈诺斯)") (field (name "CONTRIBUTOR") "lcsc"))
      (libsource (lib "altium-import") (part "root_1_IRLZ44NPBF-MNS_"))
    )
    (comp (ref "Q2")
      (value "IRLZ44NPBF-MNS")
      (fields (field (name "MANUFACTURER") "minos(迈诺斯)") (field (name "CONTRIBUTOR") "lcsc"))
      (libsource (lib "altium-import") (part "root_1_IRLZ44NPBF-MNS_"))
    )
    (comp (ref "Q3")
      (value "IRLZ44NPBF-MNS")
      (fields (field (name "MANUFACTURER") "minos(迈诺斯)") (field (name "CONTRIBUTOR") "lcsc"))
      (libsource (lib "altium-import") (part "root_1_IRLZ44NPBF-MNS_"))
    )
    (comp (ref "Q4")
      (value "IRLZ44NPBF-MNS")
      (fields (field (name "MANUFACTURER") "minos(迈诺斯)") (field (name "CONTRIBUTOR") "lcsc"))
      (libsource (lib "altium-import") (part "root_1_IRLZ44NPBF-MNS_"))
    )
    (comp (ref "Q5")
      (value "IRLZ44NPBF-MNS")
      (fields (field (name "MANUFACTURER") "minos(迈诺斯)") (field (name "CONTRIBUTOR") "lcsc"))
      (libsource (lib "altium-import") (part "root_1_IRLZ44NPBF-MNS_"))
    )
    (comp (ref "Q6")
      (value "IRLZ44NPBF-MNS")
      (fields (field (name "MANUFACTURER") "minos(迈诺斯)") (field (name "CONTRIBUTOR") "lcsc"))
      (libsource (lib "altium-import") (part "root_1_IRLZ44NPBF-MNS_"))
    )
    (comp (ref "Q7")
      (value "IRLZ44NPBF-MNS")
      (fields (field (name "MANUFACTURER") "minos(迈诺斯)") (field (name "CONTRIBUTOR") "lcsc"))
      (libsource (lib "altium-import") (part "root_1_IRLZ44NPBF-MNS_"))
    )
    (comp (ref "Q8")
      (value "IRLZ44NPBF-MNS")
      (fields (field (name "MANUFACTURER") "minos(迈诺斯)") (field (name "CONTRIBUTOR") "lcsc"))
      (libsource (lib "altium-import") (part "root_1_IRLZ44NPBF-MNS_"))
    )
    (comp (ref "Q9")
      (value "IRLZ44NPBF-MNS")
      (fields (field (name "MANUFACTURER") "minos(迈诺斯)") (field (name "CONTRIBUTOR") "lcsc"))
      (libsource (lib "altium-import") (part "root_1_IRLZ44NPBF-MNS_"))
    )
    (comp (ref "Q10")
      (value "IRLZ44NPBF-MNS")
      (fields (field (name "MANUFACTURER") "minos(迈诺斯)") (field (name "CONTRIBUTOR") "lcsc"))
      (libsource (lib "altium-import") (part "root_1_IRLZ44NPBF-MNS_"))
    )
    (comp (ref "Q11")
      (value "IRLZ44NPBF-MNS")
      (fields (field (name "MANUFACTURER") "minos(迈诺斯)") (field (name "CONTRIBUTOR") "lcsc"))
      (libsource (lib "altium-import") (part "root_1_IRLZ44NPBF-MNS_"))
    )
    (comp (ref "Q12")
      (value "IRLZ44NPBF-MNS")
      (fields (field (name "MANUFACTURER") "minos(迈诺斯)") (field (name "CONTRIBUTOR") "lcsc"))
      (libsource (lib "altium-import") (part "root_1_IRLZ44NPBF-MNS_"))
    )
    (comp (ref "Q13")
      (value "IRLZ44NPBF-MNS")
      (fields (field (name "MANUFACTURER") "minos(迈诺斯)") (field (name "CONTRIBUTOR") "lcsc"))
      (libsource (lib "altium-import") (part "root_1_IRLZ44NPBF-MNS_"))
    )
    (comp (ref "Q14")
      (value "IRLZ44NPBF-MNS")
      (fields (field (name "MANUFACTURER") "minos(迈诺斯)") (field (name "CONTRIBUTOR") "lcsc"))
      (libsource (lib "altium-import") (part "root_1_IRLZ44NPBF-MNS_"))
    )
    (comp (ref "Q15")
      (value "IRLZ44NPBF-MNS")
      (fields (field (name "MANUFACTURER") "minos(迈诺斯)") (field (name "CONTRIBUTOR") "lcsc"))
      (libsource (lib "altium-import") (part "root_1_IRLZ44NPBF-MNS_"))
    )
    (comp (ref "Q16")
      (value "IRLZ44NPBF-MNS")
      (fields (field (name "MANUFACTURER") "minos(迈诺斯)") (field (name "CONTRIBUTOR") "lcsc"))
      (libsource (lib "altium-import") (part "root_1_IRLZ44NPBF-MNS_"))
    )
    (comp (ref "Q17")
      (value "AO3401CI-ES")
      (fields (field (name "MANUFACTURER") "ElecSuper(静芯)") (field (name "CONTRIBUTOR") "lcsc"))
      (libsource (lib "altium-import") (part "root_3_AO3401CI-ES_"))
    )
    (comp (ref "Q18")
      (value "2N7000-TA")
      (fields (field (name "MANUFACTURER") "CJ(江苏长电/长晶)") (field (name "CONTRIBUTOR") "LCSC"))
      (libsource (lib "altium-import") (part "root_1_2N7000-TA_"))
    )
    (comp (ref "Q19")
      (value "AO3401CI-ES")
      (fields (field (name "MANUFACTURER") "ElecSuper(静芯)") (field (name "CONTRIBUTOR") "lcsc"))
      (libsource (lib "altium-import") (part "root_3_AO3401CI-ES_"))
    )
    (comp (ref "Q20")
      (value "AO3401CI-ES")
      (fields (field (name "MANUFACTURER") "ElecSuper(静芯)") (field (name "CONTRIBUTOR") "lcsc"))
      (libsource (lib "altium-import") (part "root_3_AO3401CI-ES_"))
    )
    (comp (ref "Q21")
      (value "AO3401CI-ES")
      (fields (field (name "MANUFACTURER") "ElecSuper(静芯)") (field (name "CONTRIBUTOR") "lcsc"))
      (libsource (lib "altium-import") (part "root_3_AO3401CI-ES_"))
    )
    (comp (ref "Q22")
      (value "AO3401CI-ES")
      (fields (field (name "MANUFACTURER") "ElecSuper(静芯)") (field (name "CONTRIBUTOR") "lcsc"))
      (libsource (lib "altium-import") (part "root_3_AO3401CI-ES_"))
    )
    (comp (ref "Q23")
      (value "AO3401CI-ES")
      (fields (field (name "MANUFACTURER") "ElecSuper(静芯)") (field (name "CONTRIBUTOR") "lcsc"))
      (libsource (lib "altium-import") (part "root_3_AO3401CI-ES_"))
    )
    (comp (ref "Q24")
      (value "AO3401CI-ES")
      (fields (field (name "MANUFACTURER") "ElecSuper(静芯)") (field (name "CONTRIBUTOR") "lcsc"))
      (libsource (lib "altium-import") (part "root_3_AO3401CI-ES_"))
    )
    (comp (ref "Q25")
      (value "AO3401CI-ES")
      (fields (field (name "MANUFACTURER") "ElecSuper(静芯)") (field (name "CONTRIBUTOR") "lcsc"))
      (libsource (lib "altium-import") (part "root_3_AO3401CI-ES_"))
    )
    (comp (ref "Q26")
      (value "AO3401CI-ES")
      (fields (field (name "MANUFACTURER") "ElecSuper(静芯)") (field (name "CONTRIBUTOR") "lcsc"))
      (libsource (lib "altium-import") (part "root_3_AO3401CI-ES_"))
    )
    (comp (ref "Q27")
      (value "AO3401CI-ES")
      (fields (field (name "MANUFACTURER") "ElecSuper(静芯)") (field (name "CONTRIBUTOR") "lcsc"))
      (libsource (lib "altium-import") (part "root_3_AO3401CI-ES_"))
    )
    (comp (ref "Q28")
      (value "AO3401CI-ES")
      (fields (field (name "MANUFACTURER") "ElecSuper(静芯)") (field (name "CONTRIBUTOR") "lcsc"))
      (libsource (lib "altium-import") (part "root_3_AO3401CI-ES_"))
    )
    (comp (ref "Q29")
      (value "AO3401CI-ES")
      (fields (field (name "MANUFACTURER") "ElecSuper(静芯)") (field (name "CONTRIBUTOR") "lcsc"))
      (libsource (lib "altium-import") (part "root_3_AO3401CI-ES_"))
    )
    (comp (ref "Q30")
      (value "AO3401CI-ES")
      (fields (field (name "MANUFACTURER") "ElecSuper(静芯)") (field (name "CONTRIBUTOR") "lcsc"))
      (libsource (lib "altium-import") (part "root_3_AO3401CI-ES_"))
    )
    (comp (ref "Q31")
      (value "AO3401CI-ES")
      (fields (field (name "MANUFACTURER") "ElecSuper(静芯)") (field (name "CONTRIBUTOR") "lcsc"))
      (libsource (lib "altium-import") (part "root_3_AO3401CI-ES_"))
    )
    (comp (ref "Q32")
      (value "AO3401CI-ES")
      (fields (field (name "MANUFACTURER") "ElecSuper(静芯)") (field (name "CONTRIBUTOR") "lcsc"))
      (libsource (lib "altium-import") (part "root_3_AO3401CI-ES_"))
    )
    (comp (ref "Q33")
      (value "AO3401CI-ES")
      (fields (field (name "MANUFACTURER") "ElecSuper(静芯)") (field (name "CONTRIBUTOR") "lcsc"))
      (libsource (lib "altium-import") (part "root_3_AO3401CI-ES_"))
    )
    (comp (ref "R1")
      (value "10k")
      (fields
        (field (name "MANUFACTURER PART") "MFR-12FTF52-10K")
        (field (name "MANUFACTURER") "YAGEO(国巨)")
        (field (name "CONTRIBUTOR") "LCEDA_Lib")
      )
      (libsource (lib "altium-import") (part "root_1_10k_"))
    )
    (comp (ref "R2")
      (value "10k")
      (fields
        (field (name "MANUFACTURER PART") "MFR-12FTF52-10K")
        (field (name "MANUFACTURER") "YAGEO(国巨)")
        (field (name "CONTRIBUTOR") "LCEDA_Lib")
      )
      (libsource (lib "altium-import") (part "root_1_10k_"))
    )
    (comp (ref "R3")
      (value "10k")
      (fields
        (field (name "MANUFACTURER PART") "MFR-12FTF52-10K")
        (field (name "MANUFACTURER") "YAGEO(国巨)")
        (field (name "CONTRIBUTOR") "LCEDA_Lib")
      )
      (libsource (lib "altium-import") (part "root_1_10k_"))
    )
    (comp (ref "R4")
      (value "10k")
      (fields
        (field (name "MANUFACTURER PART") "MFR-12FTF52-10K")
        (field (name "MANUFACTURER") "YAGEO(国巨)")
        (field (name "CONTRIBUTOR") "LCEDA_Lib")
      )
      (libsource (lib "altium-import") (part "root_1_10k_"))
    )
    (comp (ref "R5")
      (value "10k")
      (fields
        (field (name "MANUFACTURER PART") "MFR-12FTF52-10K")
        (field (name "MANUFACTURER") "YAGEO(国巨)")
        (field (name "CONTRIBUTOR") "LCEDA_Lib")
      )
      (libsource (lib "altium-import") (part "root_1_10k_"))
    )
    (comp (ref "R6")
      (value "10k")
      (fields
        (field (name "MANUFACTURER PART") "MFR-12FTF52-10K")
        (field (name "MANUFACTURER") "YAGEO(国巨)")
        (field (name "CONTRIBUTOR") "LCEDA_Lib")
      )
      (libsource (lib "altium-import") (part "root_1_10k_"))
    )
    (comp (ref "R7")
      (value "10k")
      (fields
        (field (name "MANUFACTURER PART") "MFR-12FTF52-10K")
        (field (name "MANUFACTURER") "YAGEO(国巨)")
        (field (name "CONTRIBUTOR") "LCEDA_Lib")
      )
      (libsource (lib "altium-import") (part "root_1_10k_"))
    )
    (comp (ref "R8")
      (value "10k")
      (fields
        (field (name "MANUFACTURER PART") "MFR-12FTF52-10K")
        (field (name "MANUFACTURER") "YAGEO(国巨)")
        (field (name "CONTRIBUTOR") "LCEDA_Lib")
      )
      (libsource (lib "altium-import") (part "root_1_10k_"))
    )
    (comp (ref "R9")
      (value "10k")
      (fields
        (field (name "MANUFACTURER PART") "MFR-12FTF52-10K")
        (field (name "MANUFACTURER") "YAGEO(国巨)")
        (field (name "CONTRIBUTOR") "LCEDA_Lib")
      )
      (libsource (lib "altium-import") (part "root_1_10k_"))
    )
    (comp (ref "R10")
      (value "10k")
      (fields
        (field (name "MANUFACTURER PART") "MFR-12FTF52-10K")
        (field (name "MANUFACTURER") "YAGEO(国巨)")
        (field (name "CONTRIBUTOR") "LCEDA_Lib")
      )
      (libsource (lib "altium-import") (part "root_1_10k_"))
    )
    (comp (ref "R11")
      (value "10k")
      (fields
        (field (name "MANUFACTURER PART") "MFR-12FTF52-10K")
        (field (name "MANUFACTURER") "YAGEO(国巨)")
        (field (name "CONTRIBUTOR") "LCEDA_Lib")
      )
      (libsource (lib "altium-import") (part "root_1_10k_"))
    )
    (comp (ref "R12")
      (value "10k")
      (fields
        (field (name "MANUFACTURER PART") "MFR-12FTF52-10K")
        (field (name "MANUFACTURER") "YAGEO(国巨)")
        (field (name "CONTRIBUTOR") "LCEDA_Lib")
      )
      (libsource (lib "altium-import") (part "root_1_10k_"))
    )
    (comp (ref "R13")
      (value "10k")
      (fields
        (field (name "MANUFACTURER PART") "MFR-12FTF52-10K")
        (field (name "MANUFACTURER") "YAGEO(国巨)")
        (field (name "CONTRIBUTOR") "LCEDA_Lib")
      )
      (libsource (lib "altium-import") (part "root_1_10k_"))
    )
    (comp (ref "R14")
      (value "10k")
      (fields
        (field (name "MANUFACTURER PART") "MFR-12FTF52-10K")
        (field (name "MANUFACTURER") "YAGEO(国巨)")
        (field (name "CONTRIBUTOR") "LCEDA_Lib")
      )
      (libsource (lib "altium-import") (part "root_1_10k_"))
    )
    (comp (ref "R15")
      (value "10k")
      (fields
        (field (name "MANUFACTURER PART") "MFR-12FTF52-10K")
        (field (name "MANUFACTURER") "YAGEO(国巨)")
        (field (name "CONTRIBUTOR") "LCEDA_Lib")
      )
      (libsource (lib "altium-import") (part "root_1_10k_"))
    )
    (comp (ref "R16")
      (value "10k")
      (fields
        (field (name "MANUFACTURER PART") "MFR-12FTF52-10K")
        (field (name "MANUFACTURER") "YAGEO(国巨)")
        (field (name "CONTRIBUTOR") "LCEDA_Lib")
      )
      (libsource (lib "altium-import") (part "root_1_10k_"))
    )
    (comp (ref "R17")
      (value "10k")
      (fields
        (field (name "MANUFACTURER PART") "MFR-12FTF52-10K")
        (field (name "MANUFACTURER") "YAGEO(国巨)")
        (field (name "CONTRIBUTOR") "LCEDA_Lib")
      )
      (libsource (lib "altium-import") (part "root_2_10k_"))
    )
    (comp (ref "R18")
      (value "10k")
      (fields
        (field (name "MANUFACTURER PART") "MFR-12FTF52-10K")
        (field (name "MANUFACTURER") "YAGEO(国巨)")
        (field (name "CONTRIBUTOR") "LCEDA_Lib")
      )
      (libsource (lib "altium-import") (part "root_0_10k_"))
    )
    (comp (ref "R19")
      (value "15Ω")
      (fields
        (field (name "MANUFACTURER") "CCO(千志电子)")
        (field (name "MANUFACTURER PART") "MF1/4W-15Ω±1% T")
        (field (name "CONTRIBUTOR") "LCSC")
      )
      (libsource (lib "altium-import") (part "root_0_15Ω_"))
    )
    (comp (ref "R20")
      (value "10k")
      (fields
        (field (name "MANUFACTURER PART") "MFR-12FTF52-10K")
        (field (name "MANUFACTURER") "YAGEO(国巨)")
        (field (name "CONTRIBUTOR") "LCEDA_Lib")
      )
      (libsource (lib "altium-import") (part "root_0_10k_"))
    )
    (comp (ref "R21")
      (value "10k")
      (fields
        (field (name "MANUFACTURER PART") "MFR-12FTF52-10K")
        (field (name "MANUFACTURER") "YAGEO(国巨)")
        (field (name "CONTRIBUTOR") "LCEDA_Lib")
      )
      (libsource (lib "altium-import") (part "root_0_10k_"))
    )
    (comp (ref "R22")
      (value "15Ω")
      (fields
        (field (name "MANUFACTURER") "CCO(千志电子)")
        (field (name "MANUFACTURER PART") "MF1/4W-15Ω±1% T")
        (field (name "CONTRIBUTOR") "LCSC")
      )
      (libsource (lib "altium-import") (part "root_0_15Ω_"))
    )
    (comp (ref "R23")
      (value "10k")
      (fields
        (field (name "MANUFACTURER PART") "MFR-12FTF52-10K")
        (field (name "MANUFACTURER") "YAGEO(国巨)")
        (field (name "CONTRIBUTOR") "LCEDA_Lib")
      )
      (libsource (lib "altium-import") (part "root_0_10k_"))
    )
    (comp (ref "R24")
      (value "15Ω")
      (fields
        (field (name "MANUFACTURER") "CCO(千志电子)")
        (field (name "MANUFACTURER PART") "MF1/4W-15Ω±1% T")
        (field (name "CONTRIBUTOR") "LCSC")
      )
      (libsource (lib "altium-import") (part "root_0_15Ω_"))
    )
    (comp (ref "R25")
      (value "10k")
      (fields
        (field (name "MANUFACTURER PART") "MFR-12FTF52-10K")
        (field (name "MANUFACTURER") "YAGEO(国巨)")
        (field (name "CONTRIBUTOR") "LCEDA_Lib")
      )
      (libsource (lib "altium-import") (part "root_0_10k_"))
    )
    (comp (ref "R26")
      (value "10k")
      (fields
        (field (name "MANUFACTURER PART") "MFR-12FTF52-10K")
        (field (name "MANUFACTURER") "YAGEO(国巨)")
        (field (name "CONTRIBUTOR") "LCEDA_Lib")
      )
      (libsource (lib "altium-import") (part "root_1_10k_"))
    )
    (comp (ref "R27")
      (value "15Ω")
      (fields
        (field (name "MANUFACTURER") "CCO(千志电子)")
        (field (name "MANUFACTURER PART") "MF1/4W-15Ω±1% T")
        (field (name "CONTRIBUTOR") "LCSC")
      )
      (libsource (lib "altium-import") (part "root_0_15Ω_"))
    )
    (comp (ref "R28")
      (value "10k")
      (fields
        (field (name "MANUFACTURER PART") "MFR-12FTF52-10K")
        (field (name "MANUFACTURER") "YAGEO(国巨)")
        (field (name "CONTRIBUTOR") "LCEDA_Lib")
      )
      (libsource (lib "altium-import") (part "root_0_10k_"))
    )
    (comp (ref "R29")
      (value "1M")
      (fields
        (field (name "MANUFACTURER PART") "FRC2512F1004TS")
        (field (name "MANUFACTURER") "FOJAN(富捷)")
        (field (name "CONTRIBUTOR") "LCEDA_Lib")
      )
      (libsource (lib "altium-import") (part "root_0_1M_"))
    )
    (comp (ref "R30")
      (value "2.2k")
      (fields
        (field (name "MANUFACTURER PART") "MF0204FTE52-2K2")
        (field (name "MANUFACTURER") "YAGEO(国巨)")
        (field (name "CONTRIBUTOR") "LCEDA_Lib")
      )
      (libsource (lib "altium-import") (part "root_1_2.2k_"))
    )
    (comp (ref "R31")
      (value "15Ω")
      (fields
        (field (name "MANUFACTURER") "CCO(千志电子)")
        (field (name "MANUFACTURER PART") "MF1/4W-15Ω±1% T")
        (field (name "CONTRIBUTOR") "LCSC")
      )
      (libsource (lib "altium-import") (part "root_0_15Ω_"))
    )
    (comp (ref "R32")
      (value "10k")
      (fields
        (field (name "MANUFACTURER PART") "MFR-12FTF52-10K")
        (field (name "MANUFACTURER") "YAGEO(国巨)")
        (field (name "CONTRIBUTOR") "LCEDA_Lib")
      )
      (libsource (lib "altium-import") (part "root_0_10k_"))
    )
    (comp (ref "R33")
      (value "10k")
      (fields
        (field (name "MANUFACTURER PART") "MFR-12FTF52-10K")
        (field (name "MANUFACTURER") "YAGEO(国巨)")
        (field (name "CONTRIBUTOR") "LCEDA_Lib")
      )
      (libsource (lib "altium-import") (part "root_0_10k_"))
    )
    (comp (ref "R34")
      (value "15Ω")
      (fields
        (field (name "MANUFACTURER") "CCO(千志电子)")
        (field (name "MANUFACTURER PART") "MF1/4W-15Ω±1% T")
        (field (name "CONTRIBUTOR") "LCSC")
      )
      (libsource (lib "altium-import") (part "root_0_15Ω_"))
    )
    (comp (ref "R35")
      (value "10k")
      (fields
        (field (name "MANUFACTURER PART") "MFR-12FTF52-10K")
        (field (name "MANUFACTURER") "YAGEO(国巨)")
        (field (name "CONTRIBUTOR") "LCEDA_Lib")
      )
      (libsource (lib "altium-import") (part "root_0_10k_"))
    )
    (comp (ref "R36")
      (value "10k")
      (fields
        (field (name "MANUFACTURER PART") "MFR-12FTF52-10K")
        (field (name "MANUFACTURER") "YAGEO(国巨)")
        (field (name "CONTRIBUTOR") "LCEDA_Lib")
      )
      (libsource (lib "altium-import") (part "root_0_10k_"))
    )
    (comp (ref "R37")
      (value "10k")
      (fields
        (field (name "MANUFACTURER PART") "MFR-12FTF52-10K")
        (field (name "MANUFACTURER") "YAGEO(国巨)")
        (field (name "CONTRIBUTOR") "LCEDA_Lib")
      )
      (libsource (lib "altium-import") (part "root_0_10k_"))
    )
    (comp (ref "R38")
      (value "15Ω")
      (fields
        (field (name "MANUFACTURER") "CCO(千志电子)")
        (field (name "MANUFACTURER PART") "MF1/4W-15Ω±1% T")
        (field (name "CONTRIBUTOR") "LCSC")
      )
      (libsource (lib "altium-import") (part "root_0_15Ω_"))
    )
    (comp (ref "R39")
      (value "10k")
      (fields
        (field (name "MANUFACTURER PART") "MFR-12FTF52-10K")
        (field (name "MANUFACTURER") "YAGEO(国巨)")
        (field (name "CONTRIBUTOR") "LCEDA_Lib")
      )
      (libsource (lib "altium-import") (part "root_0_10k_"))
    )
    (comp (ref "R40")
      (value "15Ω")
      (fields
        (field (name "MANUFACTURER") "CCO(千志电子)")
        (field (name "MANUFACTURER PART") "MF1/4W-15Ω±1% T")
        (field (name "CONTRIBUTOR") "LCSC")
      )
      (libsource (lib "altium-import") (part "root_0_15Ω_"))
    )
    (comp (ref "R41")
      (value "10k")
      (fields
        (field (name "MANUFACTURER PART") "MFR-12FTF52-10K")
        (field (name "MANUFACTURER") "YAGEO(国巨)")
        (field (name "CONTRIBUTOR") "LCEDA_Lib")
      )
      (libsource (lib "altium-import") (part "root_0_10k_"))
    )
    (comp (ref "R42")
      (value "15Ω")
      (fields
        (field (name "MANUFACTURER") "CCO(千志电子)")
        (field (name "MANUFACTURER PART") "MF1/4W-15Ω±1% T")
        (field (name "CONTRIBUTOR") "LCSC")
      )
      (libsource (lib "altium-import") (part "root_0_15Ω_"))
    )
    (comp (ref "R43")
      (value "10k")
      (fields
        (field (name "MANUFACTURER PART") "MFR-12FTF52-10K")
        (field (name "MANUFACTURER") "YAGEO(国巨)")
        (field (name "CONTRIBUTOR") "LCEDA_Lib")
      )
      (libsource (lib "altium-import") (part "root_0_10k_"))
    )
    (comp (ref "R44")
      (value "10k")
      (fields
        (field (name "MANUFACTURER PART") "MFR-12FTF52-10K")
        (field (name "MANUFACTURER") "YAGEO(国巨)")
        (field (name "CONTRIBUTOR") "LCEDA_Lib")
      )
      (libsource (lib "altium-import") (part "root_0_10k_"))
    )
    (comp (ref "R45")
      (value "10k")
      (fields
        (field (name "MANUFACTURER PART") "MFR-12FTF52-10K")
        (field (name "MANUFACTURER") "YAGEO(国巨)")
        (field (name "CONTRIBUTOR") "LCEDA_Lib")
      )
      (libsource (lib "altium-import") (part "root_0_10k_"))
    )
    (comp (ref "R46")
      (value "10k")
      (fields
        (field (name "MANUFACTURER PART") "MFR-12FTF52-10K")
        (field (name "MANUFACTURER") "YAGEO(国巨)")
        (field (name "CONTRIBUTOR") "LCEDA_Lib")
      )
      (libsource (lib "altium-import") (part "root_0_10k_"))
    )
    (comp (ref "R47")
      (value "10k")
      (fields
        (field (name "MANUFACTURER PART") "MFR-12FTF52-10K")
        (field (name "MANUFACTURER") "YAGEO(国巨)")
        (field (name "CONTRIBUTOR") "LCEDA_Lib")
      )
      (libsource (lib "altium-import") (part "root_0_10k_"))
    )
    (comp (ref "R48")
      (value "10k")
      (fields
        (field (name "MANUFACTURER PART") "MFR-12FTF52-10K")
        (field (name "MANUFACTURER") "YAGEO(国巨)")
        (field (name "CONTRIBUTOR") "LCEDA_Lib")
      )
      (libsource (lib "altium-import") (part "root_0_10k_"))
    )
    (comp (ref "R49")
      (value "15Ω")
      (fields
        (field (name "MANUFACTURER") "CCO(千志电子)")
        (field (name "MANUFACTURER PART") "MF1/4W-15Ω±1% T")
        (field (name "CONTRIBUTOR") "LCSC")
      )
      (libsource (lib "altium-import") (part "root_0_15Ω_"))
    )
    (comp (ref "R50")
      (value "10k")
      (fields
        (field (name "MANUFACTURER PART") "MFR-12FTF52-10K")
        (field (name "MANUFACTURER") "YAGEO(国巨)")
        (field (name "CONTRIBUTOR") "LCEDA_Lib")
      )
      (libsource (lib "altium-import") (part "root_0_10k_"))
    )
    (comp (ref "R51")
      (value "10k")
      (fields
        (field (name "MANUFACTURER PART") "MFR-12FTF52-10K")
        (field (name "MANUFACTURER") "YAGEO(国巨)")
        (field (name "CONTRIBUTOR") "LCEDA_Lib")
      )
      (libsource (lib "altium-import") (part "root_0_10k_"))
    )
    (comp (ref "R52")
      (value "10k")
      (fields
        (field (name "MANUFACTURER PART") "MFR-12FTF52-10K")
        (field (name "MANUFACTURER") "YAGEO(国巨)")
        (field (name "CONTRIBUTOR") "LCEDA_Lib")
      )
      (libsource (lib "altium-import") (part "root_0_10k_"))
    )
    (comp (ref "R53")
      (value "10k")
      (fields
        (field (name "MANUFACTURER PART") "MFR-12FTF52-10K")
        (field (name "MANUFACTURER") "YAGEO(国巨)")
        (field (name "CONTRIBUTOR") "LCEDA_Lib")
      )
      (libsource (lib "altium-import") (part "root_0_10k_"))
    )
    (comp (ref "R54")
      (value "15Ω")
      (fields
        (field (name "MANUFACTURER") "CCO(千志电子)")
        (field (name "MANUFACTURER PART") "MF1/4W-15Ω±1% T")
        (field (name "CONTRIBUTOR") "LCSC")
      )
      (libsource (lib "altium-import") (part "root_0_15Ω_"))
    )
    (comp (ref "R55")
      (value "10k")
      (fields
        (field (name "MANUFACTURER PART") "MFR-12FTF52-10K")
        (field (name "MANUFACTURER") "YAGEO(国巨)")
        (field (name "CONTRIBUTOR") "LCEDA_Lib")
      )
      (libsource (lib "altium-import") (part "root_0_10k_"))
    )
    (comp (ref "R56")
      (value "10k")
      (fields
        (field (name "MANUFACTURER PART") "MFR-12FTF52-10K")
        (field (name "MANUFACTURER") "YAGEO(国巨)")
        (field (name "CONTRIBUTOR") "LCEDA_Lib")
      )
      (libsource (lib "altium-import") (part "root_0_10k_"))
    )
    (comp (ref "R57")
      (value "10k")
      (fields
        (field (name "MANUFACTURER PART") "MFR-12FTF52-10K")
        (field (name "MANUFACTURER") "YAGEO(国巨)")
        (field (name "CONTRIBUTOR") "LCEDA_Lib")
      )
      (libsource (lib "altium-import") (part "root_0_10k_"))
    )
    (comp (ref "R58")
      (value "10k")
      (fields
        (field (name "MANUFACTURER PART") "MFR-12FTF52-10K")
        (field (name "MANUFACTURER") "YAGEO(国巨)")
        (field (name "CONTRIBUTOR") "LCEDA_Lib")
      )
      (libsource (lib "altium-import") (part "root_0_10k_"))
    )
    (comp (ref "R59")
      (value "10k")
      (fields
        (field (name "MANUFACTURER PART") "MFR-12FTF52-10K")
        (field (name "MANUFACTURER") "YAGEO(国巨)")
        (field (name "CONTRIBUTOR") "LCEDA_Lib")
      )
      (libsource (lib "altium-import") (part "root_0_10k_"))
    )
    (comp (ref "R60")
      (value "15Ω")
      (fields
        (field (name "MANUFACTURER") "CCO(千志电子)")
        (field (name "MANUFACTURER PART") "MF1/4W-15Ω±1% T")
        (field (name "CONTRIBUTOR") "LCSC")
      )
      (libsource (lib "altium-import") (part "root_0_15Ω_"))
    )
    (comp (ref "R61")
      (value "10k")
      (fields
        (field (name "MANUFACTURER PART") "MFR-12FTF52-10K")
        (field (name "MANUFACTURER") "YAGEO(国巨)")
        (field (name "CONTRIBUTOR") "LCEDA_Lib")
      )
      (libsource (lib "altium-import") (part "root_0_10k_"))
    )
    (comp (ref "R62")
      (value "15Ω")
      (fields
        (field (name "MANUFACTURER") "CCO(千志电子)")
        (field (name "MANUFACTURER PART") "MF1/4W-15Ω±1% T")
        (field (name "CONTRIBUTOR") "LCSC")
      )
      (libsource (lib "altium-import") (part "root_0_15Ω_"))
    )
    (comp (ref "R63")
      (value "10k")
      (fields
        (field (name "MANUFACTURER PART") "MFR-12FTF52-10K")
        (field (name "MANUFACTURER") "YAGEO(国巨)")
        (field (name "CONTRIBUTOR") "LCEDA_Lib")
      )
      (libsource (lib "altium-import") (part "root_0_10k_"))
    )
    (comp (ref "R64")
      (value "15Ω")
      (fields
        (field (name "MANUFACTURER") "CCO(千志电子)")
        (field (name "MANUFACTURER PART") "MF1/4W-15Ω±1% T")
        (field (name "CONTRIBUTOR") "LCSC")
      )
      (libsource (lib "altium-import") (part "root_0_15Ω_"))
    )
    (comp (ref "R65")
      (value "10k")
      (fields
        (field (name "MANUFACTURER PART") "MFR-12FTF52-10K")
        (field (name "MANUFACTURER") "YAGEO(国巨)")
        (field (name "CONTRIBUTOR") "LCEDA_Lib")
      )
      (libsource (lib "altium-import") (part "root_0_10k_"))
    )
    (comp (ref "R66")
      (value "15Ω")
      (fields
        (field (name "MANUFACTURER") "CCO(千志电子)")
        (field (name "MANUFACTURER PART") "MF1/4W-15Ω±1% T")
        (field (name "CONTRIBUTOR") "LCSC")
      )
      (libsource (lib "altium-import") (part "root_0_15Ω_"))
    )
    (comp (ref "R67")
      (value "10k")
      (fields
        (field (name "MANUFACTURER PART") "MFR-12FTF52-10K")
        (field (name "MANUFACTURER") "YAGEO(国巨)")
        (field (name "CONTRIBUTOR") "LCEDA_Lib")
      )
      (libsource (lib "altium-import") (part "root_0_10k_"))
    )
    (comp (ref "R68")
      (value "15Ω")
      (fields
        (field (name "MANUFACTURER") "CCO(千志电子)")
        (field (name "MANUFACTURER PART") "MF1/4W-15Ω±1% T")
        (field (name "CONTRIBUTOR") "LCSC")
      )
      (libsource (lib "altium-import") (part "root_0_15Ω_"))
    )
    (comp (ref "R69")
      (value "10k")
      (fields
        (field (name "MANUFACTURER PART") "MFR-12FTF52-10K")
        (field (name "MANUFACTURER") "YAGEO(国巨)")
        (field (name "CONTRIBUTOR") "LCEDA_Lib")
      )
      (libsource (lib "altium-import") (part "root_0_10k_"))
    )
    (comp (ref "SW1")
      (value "DIP switchEI-04")
      (fields (field (name "MANUFACTURER") "圜达") (field (name "MANUFACTURER PART") "拨码开关EI-04"))
      (libsource (lib "altium-import") (part "root_0_DIP switchEI-04_"))
    )
    (comp (ref "U1")
      (value "XL74HC4514D")
      (fields (field (name "MANUFACTURER") "XINLUDA(信路达)") (field (name "CONTRIBUTOR") "lcsc"))
      (libsource (lib "altium-import") (part "root_0_XL74HC4514D_"))
    )
    (comp (ref "U2")
      (value "CD74HC4060M96")
      (fields (field (name "MANUFACTURER") "TI(德州仪器)"))
      (libsource (lib "altium-import") (part "root_0_CD74HC4060M96_"))
    )
    (comp (ref "U3")
      (value "74LVC541AD-Q100J")
      (fields (field (name "MANUFACTURER") "Nexperia(安世)") (field (name "CONTRIBUTOR") "LCSC"))
      (libsource (lib "altium-import") (part "root_0_74LVC541AD-Q100J_"))
    )
    (comp (ref "U4")
      (value "SN74HC590ADR")
      (fields (field (name "MANUFACTURER") "TI(德州仪器)") (field (name "CONTRIBUTOR") "LCSC"))
      (libsource (lib "altium-import") (part "root_0_SN74HC590ADR_"))
    )
    (comp (ref "U5")
      (value "74LVC541AD-Q100J")
      (fields (field (name "MANUFACTURER") "Nexperia(安世)") (field (name "CONTRIBUTOR") "LCSC"))
      (libsource (lib "altium-import") (part "root_0_74LVC541AD-Q100J_"))
    )
    (comp (ref "U6")
      (value "AT28C256-15PU")
      (fields (field (name "MANUFACTURER") "MICROCHIP(美国微芯)") (field (name "CONTRIBUTOR") "LCSC"))
      (libsource (lib "altium-import") (part "root_0_AT28C256-15PU_"))
    )
    (comp (ref "U7")
      (value "LM3940IMPX-3.3/NOPB")
      (fields (field (name "MANUFACTURER") "TI(德州仪器)") (field (name "CONTRIBUTOR") "LCSC"))
      (libsource (lib "altium-import") (part "root_0_LM3940IMPX-3.3/NOPB_"))
    )
    (comp (ref "X1")
      (value "32.768kHz")
      (fields
        (field (name "MANUFACTURER") "TKD(泰晶)")
        (field (name "MANUFACTURER PART") "CD02K032768ACNBAEAE")
        (field (name "CONTRIBUTOR") "lcsc")
      )
      (libsource (lib "altium-import") (part "root_0_32.768kHz_"))
    )
  )
  (nets
    (net (code "1") (name "+3.3V") (class "Default")
      (node (ref "C6") (pin "1") (pinfunction "1_1") (pintype "passive"))
      (node (ref "Q17") (pin "2") (pinfunction "S_2") (pintype "passive"))
      (node (ref "Q19") (pin "2") (pinfunction "S_2") (pintype "passive"))
      (node (ref "Q20") (pin "2") (pinfunction "S_2") (pintype "passive"))
      (node (ref "Q21") (pin "2") (pinfunction "S_2") (pintype "passive"))
      (node (ref "Q22") (pin "2") (pinfunction "S_2") (pintype "passive"))
      (node (ref "Q23") (pin "2") (pinfunction "S_2") (pintype "passive"))
      (node (ref "Q24") (pin "2") (pinfunction "S_2") (pintype "passive"))
      (node (ref "Q25") (pin "2") (pinfunction "S_2") (pintype "passive"))
      (node (ref "Q26") (pin "2") (pinfunction "S_2") (pintype "passive"))
      (node (ref "Q27") (pin "2") (pinfunction "S_2") (pintype "passive"))
      (node (ref "Q28") (pin "2") (pinfunction "S_2") (pintype "passive"))
      (node (ref "Q29") (pin "2") (pinfunction "S_2") (pintype "passive"))
      (node (ref "Q30") (pin "2") (pinfunction "S_2") (pintype "passive"))
      (node (ref "Q31") (pin "2") (pinfunction "S_2") (pintype "passive"))
      (node (ref "Q32") (pin "2") (pinfunction "S_2") (pintype "passive"))
      (node (ref "Q33") (pin "2") (pinfunction "S_2") (pintype "passive"))
      (node (ref "R1") (pin "1") (pinfunction "1_1") (pintype "passive"))
      (node (ref "R10") (pin "1") (pinfunction "1_1") (pintype "passive"))
      (node (ref "R11") (pin "1") (pinfunction "1_1") (pintype "passive"))
      (node (ref "R12") (pin "1") (pinfunction "1_1") (pintype "passive"))
      (node (ref "R13") (pin "1") (pinfunction "1_1") (pintype "passive"))
      (node (ref "R14") (pin "1") (pinfunction "1_1") (pintype "passive"))
      (node (ref "R15") (pin "1") (pinfunction "1_1") (pintype "passive"))
      (node (ref "R16") (pin "1") (pinfunction "1_1") (pintype "passive"))
      (node (ref "R17") (pin "1") (pinfunction "1_1") (pintype "passive"))
      (node (ref "R2") (pin "1") (pinfunction "1_1") (pintype "passive"))
      (node (ref "R20") (pin "2") (pinfunction "2_2") (pintype "passive"))
      (node (ref "R21") (pin "2") (pinfunction "2_2") (pintype "passive"))
      (node (ref "R23") (pin "2") (pinfunction "2_2") (pintype "passive"))
      (node (ref "R25") (pin "2") (pinfunction "2_2") (pintype "passive"))
      (node (ref "R3") (pin "1") (pinfunction "1_1") (pintype "passive"))
      (node (ref "R32") (pin "2") (pinfunction "2_2") (pintype "passive"))
      (node (ref "R36") (pin "2") (pinfunction "2_2") (pintype "passive"))
      (node (ref "R39") (pin "2") (pinfunction "2_2") (pintype "passive"))
      (node (ref "R4") (pin "1") (pinfunction "1_1") (pintype "passive"))
      (node (ref "R41") (pin "2") (pinfunction "2_2") (pintype "passive"))
      (node (ref "R45") (pin "2") (pinfunction "2_2") (pintype "passive"))
      (node (ref "R5") (pin "1") (pinfunction "1_1") (pintype "passive"))
      (node (ref "R53") (pin "2") (pinfunction "2_2") (pintype "passive"))
      (node (ref "R57") (pin "2") (pinfunction "2_2") (pintype "passive"))
      (node (ref "R6") (pin "1") (pinfunction "1_1") (pintype "passive"))
      (node (ref "R61") (pin "2") (pinfunction "2_2") (pintype "passive"))
      (node (ref "R63") (pin "2") (pinfunction "2_2") (pintype "passive"))
      (node (ref "R65") (pin "2") (pinfunction "2_2") (pintype "passive"))
      (node (ref "R67") (pin "2") (pinfunction "2_2") (pintype "passive"))
      (node (ref "R69") (pin "2") (pinfunction "2_2") (pintype "passive"))
      (node (ref "R7") (pin "1") (pinfunction "1_1") (pintype "passive"))
      (node (ref "R8") (pin "1") (pinfunction "1_1") (pintype "passive"))
      (node (ref "R9") (pin "1") (pinfunction "1_1") (pintype "passive"))
      (node (ref "U3") (pin "20") (pinfunction "VCC_20") (pintype "passive"))
      (node (ref "U5") (pin "20") (pinfunction "VCC_20") (pintype "passive"))
      (node (ref "U7") (pin "3") (pinfunction "OUT_3") (pintype "passive"))
    )
    (net (code "2") (name "+5V") (class "Default")
      (node (ref "C1") (pin "2") (pinfunction "2_2") (pintype "passive"))
      (node (ref "C2") (pin "2") (pinfunction "2_2") (pintype "passive"))
      (node (ref "C5") (pin "1") (pinfunction "1_1") (pintype "passive"))
      (node (ref "DIP1") (pin "1") (pinfunction "1_1") (pintype "passive"))
      (node (ref "DIP1") (pin "2") (pinfunction "2_2") (pintype "passive"))
      (node (ref "DIP1") (pin "3") (pinfunction "3_3") (pintype "passive"))
      (node (ref "DIP1") (pin "4") (pinfunction "4_4") (pintype "passive"))
      (node (ref "DIP1") (pin "5") (pinfunction "5_5") (pintype "passive"))
      (node (ref "DIP1") (pin "6") (pinfunction "6_6") (pintype "passive"))
      (node (ref "DIP1") (pin "7") (pinfunction "7_7") (pintype "passive"))
      (node (ref "DIP1") (pin "8") (pinfunction "8_8") (pintype "passive"))
      (node (ref "J3") (pin "2") (pinfunction "2_2") (pintype "passive"))
      (node (ref "R28") (pin "2") (pinfunction "2_2") (pintype "passive"))
      (node (ref "R33") (pin "2") (pinfunction "2_2") (pintype "passive"))
      (node (ref "SW1") (pin "1") (pinfunction "1_1") (pintype "passive"))
      (node (ref "SW1") (pin "2") (pinfunction "2_2") (pintype "passive"))
      (node (ref "SW1") (pin "3") (pinfunction "3_3") (pintype "passive"))
      (node (ref "SW1") (pin "4") (pinfunction "4_4") (pintype "passive"))
      (node (ref "U1") (pin "1") (pinfunction "LE_1") (pintype "passive"))
      (node (ref "U1") (pin "24") (pinfunction "VCC_24") (pintype "passive"))
      (node (ref "U2") (pin "16") (pinfunction "VCC_16") (pintype "passive"))
      (node (ref "U4") (pin "16") (pinfunction "VCC_16") (pintype "passive"))
      (node (ref "U6") (pin "28") (pinfunction "Vcc_28") (pintype "passive"))
      (node (ref "U7") (pin "1") (pinfunction "IN_1") (pintype "passive"))
    )
    (net (code "3") (name "/1") (class "Default")
      (node (ref "LED1") (pin "2") (pinfunction "A_2") (pintype "passive"))
      (node (ref "LED10") (pin "2") (pinfunction "A_2") (pintype "passive"))
      (node (ref "LED11") (pin "2") (pinfunction "A_2") (pintype "passive"))
      (node (ref "LED12") (pin "2") (pinfunction "A_2") (pintype "passive"))
      (node (ref "LED13") (pin "2") (pinfunction "A_2") (pintype "passive"))
      (node (ref "LED14") (pin "2") (pinfunction "A_2") (pintype "passive"))
      (node (ref "LED15") (pin "2") (pinfunction "A_2") (pintype "passive"))
      (node (ref "LED16") (pin "2") (pinfunction "A_2") (pintype "passive"))
      (node (ref "LED2") (pin "2") (pinfunction "A_2") (pintype "passive"))
      (node (ref "LED3") (pin "2") (pinfunction "A_2") (pintype "passive"))
      (node (ref "LED4") (pin "2") (pinfunction "A_2") (pintype "passive"))
      (node (ref "LED5") (pin "2") (pinfunction "A_2") (pintype "passive"))
      (node (ref "LED6") (pin "2") (pinfunction "A_2") (pintype "passive"))
      (node (ref "LED7") (pin "2") (pinfunction "A_2") (pintype "passive"))
      (node (ref "LED8") (pin "2") (pinfunction "A_2") (pintype "passive"))
      (node (ref "LED9") (pin "2") (pinfunction "A_2") (pintype "passive"))
      (node (ref "R19") (pin "2") (pinfunction "2_2") (pintype "passive"))
    )
    (net (code "4") (name "/2") (class "Default")
      (node (ref "LED17") (pin "2") (pinfunction "A_2") (pintype "passive"))
      (node (ref "LED18") (pin "2") (pinfunction "A_2") (pintype "passive"))
      (node (ref "LED19") (pin "2") (pinfunction "A_2") (pintype "passive"))
      (node (ref "LED20") (pin "2") (pinfunction "A_2") (pintype "passive"))
      (node (ref "LED21") (pin "2") (pinfunction "A_2") (pintype "passive"))
      (node (ref "LED22") (pin "2") (pinfunction "A_2") (pintype "passive"))
      (node (ref "LED23") (pin "2") (pinfunction "A_2") (pintype "passive"))
      (node (ref "LED24") (pin "2") (pinfunction "A_2") (pintype "passive"))
      (node (ref "LED25") (pin "2") (pinfunction "A_2") (pintype "passive"))
      (node (ref "LED26") (pin "2") (pinfunction "A_2") (pintype "passive"))
      (node (ref "LED27") (pin "2") (pinfunction "A_2") (pintype "passive"))
      (node (ref "LED28") (pin "2") (pinfunction "A_2") (pintype "passive"))
      (node (ref "LED29") (pin "2") (pinfunction "A_2") (pintype "passive"))
      (node (ref "LED30") (pin "2") (pinfunction "A_2") (pintype "passive"))
      (node (ref "LED31") (pin "2") (pinfunction "A_2") (pintype "passive"))
      (node (ref "LED32") (pin "2") (pinfunction "A_2") (pintype "passive"))
      (node (ref "R22") (pin "2") (pinfunction "2_2") (pintype "passive"))
    )
    (net (code "5") (name "/3") (class "Default")
      (node (ref "LED33") (pin "2") (pinfunction "A_2") (pintype "passive"))
      (node (ref "LED34") (pin "2") (pinfunction "A_2") (pintype "passive"))
      (node (ref "LED35") (pin "2") (pinfunction "A_2") (pintype "passive"))
      (node (ref "LED36") (pin "2") (pinfunction "A_2") (pintype "passive"))
      (node (ref "LED37") (pin "2") (pinfunction "A_2") (pintype "passive"))
      (node (ref "LED38") (pin "2") (pinfunction "A_2") (pintype "passive"))
      (node (ref "LED39") (pin "2") (pinfunction "A_2") (pintype "passive"))
      (node (ref "LED40") (pin "2") (pinfunction "A_2") (pintype "passive"))
      (node (ref "LED41") (pin "2") (pinfunction "A_2") (pintype "passive"))
      (node (ref "LED42") (pin "2") (pinfunction "A_2") (pintype "passive"))
      (node (ref "LED43") (pin "2") (pinfunction "A_2") (pintype "passive"))
      (node (ref "LED44") (pin "2") (pinfunction "A_2") (pintype "passive"))
      (node (ref "LED45") (pin "2") (pinfunction "A_2") (pintype "passive"))
      (node (ref "LED46") (pin "2") (pinfunction "A_2") (pintype "passive"))
      (node (ref "LED47") (pin "2") (pinfunction "A_2") (pintype "passive"))
      (node (ref "LED48") (pin "2") (pinfunction "A_2") (pintype "passive"))
      (node (ref "R24") (pin "2") (pinfunction "2_2") (pintype "passive"))
    )
    (net (code "6") (name "/4") (class "Default")
      (node (ref "LED49") (pin "2") (pinfunction "A_2") (pintype "passive"))
      (node (ref "LED50") (pin "2") (pinfunction "A_2") (pintype "passive"))
      (node (ref "LED51") (pin "2") (pinfunction "A_2") (pintype "passive"))
      (node (ref "LED52") (pin "2") (pinfunction "A_2") (pintype "passive"))
      (node (ref "LED53") (pin "2") (pinfunction "A_2") (pintype "passive"))
      (node (ref "LED54") (pin "2") (pinfunction "A_2") (pintype "passive"))
      (node (ref "LED55") (pin "2") (pinfunction "A_2") (pintype "passive"))
      (node (ref "LED56") (pin "2") (pinfunction "A_2") (pintype "passive"))
      (node (ref "LED57") (pin "2") (pinfunction "A_2") (pintype "passive"))
      (node (ref "LED58") (pin "2") (pinfunction "A_2") (pintype "passive"))
      (node (ref "LED59") (pin "2") (pinfunction "A_2") (pintype "passive"))
      (node (ref "LED60") (pin "2") (pinfunction "A_2") (pintype "passive"))
      (node (ref "LED61") (pin "2") (pinfunction "A_2") (pintype "passive"))
      (node (ref "LED62") (pin "2") (pinfunction "A_2") (pintype "passive"))
      (node (ref "LED63") (pin "2") (pinfunction "A_2") (pintype "passive"))
      (node (ref "LED64") (pin "2") (pinfunction "A_2") (pintype "passive"))
      (node (ref "R27") (pin "2") (pinfunction "2_2") (pintype "passive"))
    )
    (net (code "7") (name "/5") (class "Default")
      (node (ref "LED65") (pin "2") (pinfunction "A_2") (pintype "passive"))
      (node (ref "LED66") (pin "2") (pinfunction "A_2") (pintype "passive"))
      (node (ref "LED67") (pin "2") (pinfunction "A_2") (pintype "passive"))
      (node (ref "LED68") (pin "2") (pinfunction "A_2") (pintype "passive"))
      (node (ref "LED69") (pin "2") (pinfunction "A_2") (pintype "passive"))
      (node (ref "LED70") (pin "2") (pinfunction "A_2") (pintype "passive"))
      (node (ref "LED71") (pin "2") (pinfunction "A_2") (pintype "passive"))
      (node (ref "LED72") (pin "2") (pinfunction "A_2") (pintype "passive"))
      (node (ref "LED73") (pin "2") (pinfunction "A_2") (pintype "passive"))
      (node (ref "LED74") (pin "2") (pinfunction "A_2") (pintype "passive"))
      (node (ref "LED75") (pin "2") (pinfunction "A_2") (pintype "passive"))
      (node (ref "LED76") (pin "2") (pinfunction "A_2") (pintype "passive"))
      (node (ref "LED77") (pin "2") (pinfunction "A_2") (pintype "passive"))
      (node (ref "LED78") (pin "2") (pinfunction "A_2") (pintype "passive"))
      (node (ref "LED79") (pin "2") (pinfunction "A_2") (pintype "passive"))
      (node (ref "LED80") (pin "2") (pinfunction "A_2") (pintype "passive"))
      (node (ref "R31") (pin "2") (pinfunction "2_2") (pintype "passive"))
    )
    (net (code "8") (name "/6") (class "Default")
      (node (ref "LED81") (pin "2") (pinfunction "A_2") (pintype "passive"))
      (node (ref "LED82") (pin "2") (pinfunction "A_2") (pintype "passive"))
      (node (ref "LED83") (pin "2") (pinfunction "A_2") (pintype "passive"))
      (node (ref "LED84") (pin "2") (pinfunction "A_2") (pintype "passive"))
      (node (ref "LED85") (pin "2") (pinfunction "A_2") (pintype "passive"))
      (node (ref "LED86") (pin "2") (pinfunction "A_2") (pintype "passive"))
      (node (ref "LED87") (pin "2") (pinfunction "A_2") (pintype "passive"))
      (node (ref "LED88") (pin "2") (pinfunction "A_2") (pintype "passive"))
      (node (ref "LED89") (pin "2") (pinfunction "A_2") (pintype "passive"))
      (node (ref "LED90") (pin "2") (pinfunction "A_2") (pintype "passive"))
      (node (ref "LED91") (pin "2") (pinfunction "A_2") (pintype "passive"))
      (node (ref "LED92") (pin "2") (pinfunction "A_2") (pintype "passive"))
      (node (ref "LED93") (pin "2") (pinfunction "A_2") (pintype "passive"))
      (node (ref "LED94") (pin "2") (pinfunction "A_2") (pintype "passive"))
      (node (ref "LED95") (pin "2") (pinfunction "A_2") (pintype "passive"))
      (node (ref "LED96") (pin "2") (pinfunction "A_2") (pintype "passive"))
      (node (ref "R34") (pin "2") (pinfunction "2_2") (pintype "passive"))
    )
    (net (code "9") (name "/7") (class "Default")
      (node (ref "LED100") (pin "2") (pinfunction "A_2") (pintype "passive"))
      (node (ref "LED101") (pin "2") (pinfunction "A_2") (pintype "passive"))
      (node (ref "LED102") (pin "2") (pinfunction "A_2") (pintype "passive"))
      (node (ref "LED103") (pin "2") (pinfunction "A_2") (pintype "passive"))
      (node (ref "LED104") (pin "2") (pinfunction "A_2") (pintype "passive"))
      (node (ref "LED105") (pin "2") (pinfunction "A_2") (pintype "passive"))
      (node (ref "LED106") (pin "2") (pinfunction "A_2") (pintype "passive"))
      (node (ref "LED107") (pin "2") (pinfunction "A_2") (pintype "passive"))
      (node (ref "LED108") (pin "2") (pinfunction "A_2") (pintype "passive"))
      (node (ref "LED109") (pin "2") (pinfunction "A_2") (pintype "passive"))
      (node (ref "LED110") (pin "2") (pinfunction "A_2") (pintype "passive"))
      (node (ref "LED111") (pin "2") (pinfunction "A_2") (pintype "passive"))
      (node (ref "LED112") (pin "2") (pinfunction "A_2") (pintype "passive"))
      (node (ref "LED97") (pin "2") (pinfunction "A_2") (pintype "passive"))
      (node (ref "LED98") (pin "2") (pinfunction "A_2") (pintype "passive"))
      (node (ref "LED99") (pin "2") (pinfunction "A_2") (pintype "passive"))
      (node (ref "R38") (pin "2") (pinfunction "2_2") (pintype "passive"))
    )
    (net (code "10") (name "/8") (class "Default")
      (node (ref "LED113") (pin "2") (pinfunction "A_2") (pintype "passive"))
      (node (ref "LED114") (pin "2") (pinfunction "A_2") (pintype "passive"))
      (node (ref "LED115") (pin "2") (pinfunction "A_2") (pintype "passive"))
      (node (ref "LED116") (pin "2") (pinfunction "A_2") (pintype "passive"))
      (node (ref "LED117") (pin "2") (pinfunction "A_2") (pintype "passive"))
      (node (ref "LED118") (pin "2") (pinfunction "A_2") (pintype "passive"))
      (node (ref "LED119") (pin "2") (pinfunction "A_2") (pintype "passive"))
      (node (ref "LED120") (pin "2") (pinfunction "A_2") (pintype "passive"))
      (node (ref "LED121") (pin "2") (pinfunction "A_2") (pintype "passive"))
      (node (ref "LED122") (pin "2") (pinfunction "A_2") (pintype "passive"))
      (node (ref "LED123") (pin "2") (pinfunction "A_2") (pintype "passive"))
      (node (ref "LED124") (pin "2") (pinfunction "A_2") (pintype "passive"))
      (node (ref "LED125") (pin "2") (pinfunction "A_2") (pintype "passive"))
      (node (ref "LED126") (pin "2") (pinfunction "A_2") (pintype "passive"))
      (node (ref "LED127") (pin "2") (pinfunction "A_2") (pintype "passive"))
      (node (ref "LED128") (pin "2") (pinfunction "A_2") (pintype "passive"))
      (node (ref "R40") (pin "2") (pinfunction "2_2") (pintype "passive"))
    )
    (net (code "11") (name "/9") (class "Default")
      (node (ref "LED129") (pin "2") (pinfunction "A_2") (pintype "passive"))
      (node (ref "LED130") (pin "2") (pinfunction "A_2") (pintype "passive"))
      (node (ref "LED131") (pin "2") (pinfunction "A_2") (pintype "passive"))
      (node (ref "LED132") (pin "2") (pinfunction "A_2") (pintype "passive"))
      (node (ref "LED133") (pin "2") (pinfunction "A_2") (pintype "passive"))
      (node (ref "LED134") (pin "2") (pinfunction "A_2") (pintype "passive"))
      (node (ref "LED135") (pin "2") (pinfunction "A_2") (pintype "passive"))
      (node (ref "LED136") (pin "2") (pinfunction "A_2") (pintype "passive"))
      (node (ref "LED137") (pin "2") (pinfunction "A_2") (pintype "passive"))
      (node (ref "LED138") (pin "2") (pinfunction "A_2") (pintype "passive"))
      (node (ref "LED139") (pin "2") (pinfunction "A_2") (pintype "passive"))
      (node (ref "LED140") (pin "2") (pinfunction "A_2") (pintype "passive"))
      (node (ref "LED141") (pin "2") (pinfunction "A_2") (pintype "passive"))
      (node (ref "LED142") (pin "2") (pinfunction "A_2") (pintype "passive"))
      (node (ref "LED143") (pin "2") (pinfunction "A_2") (pintype "passive"))
      (node (ref "LED144") (pin "2") (pinfunction "A_2") (pintype "passive"))
      (node (ref "R42") (pin "2") (pinfunction "2_2") (pintype "passive"))
    )
    (net (code "12") (name "/10") (class "Default")
      (node (ref "LED145") (pin "2") (pinfunction "A_2") (pintype "passive"))
      (node (ref "LED146") (pin "2") (pinfunction "A_2") (pintype "passive"))
      (node (ref "LED147") (pin "2") (pinfunction "A_2") (pintype "passive"))
      (node (ref "LED148") (pin "2") (pinfunction "A_2") (pintype "passive"))
      (node (ref "LED149") (pin "2") (pinfunction "A_2") (pintype "passive"))
      (node (ref "LED150") (pin "2") (pinfunction "A_2") (pintype "passive"))
      (node (ref "LED151") (pin "2") (pinfunction "A_2") (pintype "passive"))
      (node (ref "LED152") (pin "2") (pinfunction "A_2") (pintype "passive"))
      (node (ref "LED153") (pin "2") (pinfunction "A_2") (pintype "passive"))
      (node (ref "LED154") (pin "2") (pinfunction "A_2") (pintype "passive"))
      (node (ref "LED155") (pin "2") (pinfunction "A_2") (pintype "passive"))
      (node (ref "LED156") (pin "2") (pinfunction "A_2") (pintype "passive"))
      (node (ref "LED157") (pin "2") (pinfunction "A_2") (pintype "passive"))
      (node (ref "LED158") (pin "2") (pinfunction "A_2") (pintype "passive"))
      (node (ref "LED159") (pin "2") (pinfunction "A_2") (pintype "passive"))
      (node (ref "LED160") (pin "2") (pinfunction "A_2") (pintype "passive"))
      (node (ref "R49") (pin "2") (pinfunction "2_2") (pintype "passive"))
    )
    (net (code "13") (name "/11") (class "Default")
      (node (ref "LED161") (pin "2") (pinfunction "A_2") (pintype "passive"))
      (node (ref "LED162") (pin "2") (pinfunction "A_2") (pintype "passive"))
      (node (ref "LED163") (pin "2") (pinfunction "A_2") (pintype "passive"))
      (node (ref "LED164") (pin "2") (pinfunction "A_2") (pintype "passive"))
      (node (ref "LED165") (pin "2") (pinfunction "A_2") (pintype "passive"))
      (node (ref "LED166") (pin "2") (pinfunction "A_2") (pintype "passive"))
      (node (ref "LED167") (pin "2") (pinfunction "A_2") (pintype "passive"))
      (node (ref "LED168") (pin "2") (pinfunction "A_2") (pintype "passive"))
      (node (ref "LED169") (pin "2") (pinfunction "A_2") (pintype "passive"))
      (node (ref "LED170") (pin "2") (pinfunction "A_2") (pintype "passive"))
      (node (ref "LED171") (pin "2") (pinfunction "A_2") (pintype "passive"))
      (node (ref "LED172") (pin "2") (pinfunction "A_2") (pintype "passive"))
      (node (ref "LED173") (pin "2") (pinfunction "A_2") (pintype "passive"))
      (node (ref "LED174") (pin "2") (pinfunction "A_2") (pintype "passive"))
      (node (ref "LED175") (pin "2") (pinfunction "A_2") (pintype "passive"))
      (node (ref "LED176") (pin "2") (pinfunction "A_2") (pintype "passive"))
      (node (ref "R54") (pin "2") (pinfunction "2_2") (pintype "passive"))
    )
    (net (code "14") (name "/12") (class "Default")
      (node (ref "LED177") (pin "2") (pinfunction "A_2") (pintype "passive"))
      (node (ref "LED178") (pin "2") (pinfunction "A_2") (pintype "passive"))
      (node (ref "LED179") (pin "2") (pinfunction "A_2") (pintype "passive"))
      (node (ref "LED180") (pin "2") (pinfunction "A_2") (pintype "passive"))
      (node (ref "LED181") (pin "2") (pinfunction "A_2") (pintype "passive"))
      (node (ref "LED182") (pin "2") (pinfunction "A_2") (pintype "passive"))
      (node (ref "LED183") (pin "2") (pinfunction "A_2") (pintype "passive"))
      (node (ref "LED184") (pin "2") (pinfunction "A_2") (pintype "passive"))
      (node (ref "LED185") (pin "2") (pinfunction "A_2") (pintype "passive"))
      (node (ref "LED186") (pin "2") (pinfunction "A_2") (pintype "passive"))
      (node (ref "LED187") (pin "2") (pinfunction "A_2") (pintype "passive"))
      (node (ref "LED188") (pin "2") (pinfunction "A_2") (pintype "passive"))
      (node (ref "LED189") (pin "2") (pinfunction "A_2") (pintype "passive"))
      (node (ref "LED190") (pin "2") (pinfunction "A_2") (pintype "passive"))
      (node (ref "LED191") (pin "2") (pinfunction "A_2") (pintype "passive"))
      (node (ref "LED192") (pin "2") (pinfunction "A_2") (pintype "passive"))
      (node (ref "R60") (pin "2") (pinfunction "2_2") (pintype "passive"))
    )
    (net (code "15") (name "/13") (class "Default")
      (node (ref "LED193") (pin "2") (pinfunction "A_2") (pintype "passive"))
      (node (ref "LED194") (pin "2") (pinfunction "A_2") (pintype "passive"))
      (node (ref "LED195") (pin "2") (pinfunction "A_2") (pintype "passive"))
      (node (ref "LED196") (pin "2") (pinfunction "A_2") (pintype "passive"))
      (node (ref "LED197") (pin "2") (pinfunction "A_2") (pintype "passive"))
      (node (ref "LED198") (pin "2") (pinfunction "A_2") (pintype "passive"))
      (node (ref "LED199") (pin "2") (pinfunction "A_2") (pintype "passive"))
      (node (ref "LED200") (pin "2") (pinfunction "A_2") (pintype "passive"))
      (node (ref "LED201") (pin "2") (pinfunction "A_2") (pintype "passive"))
      (node (ref "LED202") (pin "2") (pinfunction "A_2") (pintype "passive"))
      (node (ref "LED203") (pin "2") (pinfunction "A_2") (pintype "passive"))
      (node (ref "LED204") (pin "2") (pinfunction "A_2") (pintype "passive"))
      (node (ref "LED205") (pin "2") (pinfunction "A_2") (pintype "passive"))
      (node (ref "LED206") (pin "2") (pinfunction "A_2") (pintype "passive"))
      (node (ref "LED207") (pin "2") (pinfunction "A_2") (pintype "passive"))
      (node (ref "LED208") (pin "2") (pinfunction "A_2") (pintype "passive"))
      (node (ref "R62") (pin "2") (pinfunction "2_2") (pintype "passive"))
    )
    (net (code "16") (name "/14") (class "Default")
      (node (ref "LED209") (pin "2") (pinfunction "A_2") (pintype "passive"))
      (node (ref "LED210") (pin "2") (pinfunction "A_2") (pintype "passive"))
      (node (ref "LED211") (pin "2") (pinfunction "A_2") (pintype "passive"))
      (node (ref "LED212") (pin "2") (pinfunction "A_2") (pintype "passive"))
      (node (ref "LED213") (pin "2") (pinfunction "A_2") (pintype "passive"))
      (node (ref "LED214") (pin "2") (pinfunction "A_2") (pintype "passive"))
      (node (ref "LED215") (pin "2") (pinfunction "A_2") (pintype "passive"))
      (node (ref "LED216") (pin "2") (pinfunction "A_2") (pintype "passive"))
      (node (ref "LED217") (pin "2") (pinfunction "A_2") (pintype "passive"))
      (node (ref "LED218") (pin "2") (pinfunction "A_2") (pintype "passive"))
      (node (ref "LED219") (pin "2") (pinfunction "A_2") (pintype "passive"))
      (node (ref "LED220") (pin "2") (pinfunction "A_2") (pintype "passive"))
      (node (ref "LED221") (pin "2") (pinfunction "A_2") (pintype "passive"))
      (node (ref "LED222") (pin "2") (pinfunction "A_2") (pintype "passive"))
      (node (ref "LED223") (pin "2") (pinfunction "A_2") (pintype "passive"))
      (node (ref "LED224") (pin "2") (pinfunction "A_2") (pintype "passive"))
      (node (ref "R64") (pin "2") (pinfunction "2_2") (pintype "passive"))
    )
    (net (code "17") (name "/15") (class "Default")
      (node (ref "LED225") (pin "2") (pinfunction "A_2") (pintype "passive"))
      (node (ref "LED226") (pin "2") (pinfunction "A_2") (pintype "passive"))
      (node (ref "LED227") (pin "2") (pinfunction "A_2") (pintype "passive"))
      (node (ref "LED228") (pin "2") (pinfunction "A_2") (pintype "passive"))
      (node (ref "LED229") (pin "2") (pinfunction "A_2") (pintype "passive"))
      (node (ref "LED230") (pin "2") (pinfunction "A_2") (pintype "passive"))
      (node (ref "LED231") (pin "2") (pinfunction "A_2") (pintype "passive"))
      (node (ref "LED232") (pin "2") (pinfunction "A_2") (pintype "passive"))
      (node (ref "LED233") (pin "2") (pinfunction "A_2") (pintype "passive"))
      (node (ref "LED234") (pin "2") (pinfunction "A_2") (pintype "passive"))
      (node (ref "LED235") (pin "2") (pinfunction "A_2") (pintype "passive"))
      (node (ref "LED236") (pin "2") (pinfunction "A_2") (pintype "passive"))
      (node (ref "LED237") (pin "2") (pinfunction "A_2") (pintype "passive"))
      (node (ref "LED238") (pin "2") (pinfunction "A_2") (pintype "passive"))
      (node (ref "LED239") (pin "2") (pinfunction "A_2") (pintype "passive"))
      (node (ref "LED240") (pin "2") (pinfunction "A_2") (pintype "passive"))
      (node (ref "R66") (pin "2") (pinfunction "2_2") (pintype "passive"))
    )
    (net (code "18") (name "/16") (class "Default")
      (node (ref "LED241") (pin "2") (pinfunction "A_2") (pintype "passive"))
      (node (ref "LED242") (pin "2") (pinfunction "A_2") (pintype "passive"))
      (node (ref "LED243") (pin "2") (pinfunction "A_2") (pintype "passive"))
      (node (ref "LED244") (pin "2") (pinfunction "A_2") (pintype "passive"))
      (node (ref "LED245") (pin "2") (pinfunction "A_2") (pintype "passive"))
      (node (ref "LED246") (pin "2") (pinfunction "A_2") (pintype "passive"))
      (node (ref "LED247") (pin "2") (pinfunction "A_2") (pintype "passive"))
      (node (ref "LED248") (pin "2") (pinfunction "A_2") (pintype "passive"))
      (node (ref "LED249") (pin "2") (pinfunction "A_2") (pintype "passive"))
      (node (ref "LED250") (pin "2") (pinfunction "A_2") (pintype "passive"))
      (node (ref "LED251") (pin "2") (pinfunction "A_2") (pintype "passive"))
      (node (ref "LED252") (pin "2") (pinfunction "A_2") (pintype "passive"))
      (node (ref "LED253") (pin "2") (pinfunction "A_2") (pintype "passive"))
      (node (ref "LED254") (pin "2") (pinfunction "A_2") (pintype "passive"))
      (node (ref "LED255") (pin "2") (pinfunction "A_2") (pintype "passive"))
      (node (ref "LED256") (pin "2") (pinfunction "A_2") (pintype "passive"))
      (node (ref "R68") (pin "2") (pinfunction "2_2") (pintype "passive"))
    )
    (net (code "19") (name "/A") (class "Default")
      (node (ref "LED1") (pin "1") (pinfunction "K_1") (pintype "passive"))
      (node (ref "LED113") (pin "1") (pinfunction "K_1") (pintype "passive"))
      (node (ref "LED129") (pin "1") (pinfunction "K_1") (pintype "passive"))
      (node (ref "LED145") (pin "1") (pinfunction "K_1") (pintype "passive"))
      (node (ref "LED161") (pin "1") (pinfunction "K_1") (pintype "passive"))
      (node (ref "LED17") (pin "1") (pinfunction "K_1") (pintype "passive"))
      (node (ref "LED177") (pin "1") (pinfunction "K_1") (pintype "passive"))
      (node (ref "LED193") (pin "1") (pinfunction "K_1") (pintype "passive"))
      (node (ref "LED209") (pin "1") (pinfunction "K_1") (pintype "passive"))
      (node (ref "LED225") (pin "1") (pinfunction "K_1") (pintype "passive"))
      (node (ref "LED241") (pin "1") (pinfunction "K_1") (pintype "passive"))
      (node (ref "LED33") (pin "1") (pinfunction "K_1") (pintype "passive"))
      (node (ref "LED49") (pin "1") (pinfunction "K_1") (pintype "passive"))
      (node (ref "LED65") (pin "1") (pinfunction "K_1") (pintype "passive"))
      (node (ref "LED81") (pin "1") (pinfunction "K_1") (pintype "passive"))
      (node (ref "LED97") (pin "1") (pinfunction "K_1") (pintype "passive"))
      (node (ref "Q1") (pin "2") (pinfunction "D_2") (pintype "passive"))
      (node (ref "R1") (pin "2") (pinfunction "2_2") (pintype "passive"))
    )
    (net (code "20") (name "/B") (class "Default")
      (node (ref "LED114") (pin "1") (pinfunction "K_1") (pintype "passive"))
      (node (ref "LED130") (pin "1") (pinfunction "K_1") (pintype "passive"))
      (node (ref "LED146") (pin "1") (pinfunction "K_1") (pintype "passive"))
      (node (ref "LED162") (pin "1") (pinfunction "K_1") (pintype "passive"))
      (node (ref "LED178") (pin "1") (pinfunction "K_1") (pintype "passive"))
      (node (ref "LED18") (pin "1") (pinfunction "K_1") (pintype "passive"))
      (node (ref "LED194") (pin "1") (pinfunction "K_1") (pintype "passive"))
      (node (ref "LED2") (pin "1") (pinfunction "K_1") (pintype "passive"))
      (node (ref "LED210") (pin "1") (pinfunction "K_1") (pintype "passive"))
      (node (ref "LED226") (pin "1") (pinfunction "K_1") (pintype "passive"))
      (node (ref "LED242") (pin "1") (pinfunction "K_1") (pintype "passive"))
      (node (ref "LED34") (pin "1") (pinfunction "K_1") (pintype "passive"))
      (node (ref "LED50") (pin "1") (pinfunction "K_1") (pintype "passive"))
      (node (ref "LED66") (pin "1") (pinfunction "K_1") (pintype "passive"))
      (node (ref "LED82") (pin "1") (pinfunction "K_1") (pintype "passive"))
      (node (ref "LED98") (pin "1") (pinfunction "K_1") (pintype "passive"))
      (node (ref "Q2") (pin "2") (pinfunction "D_2") (pintype "passive"))
      (node (ref "R2") (pin "2") (pinfunction "2_2") (pintype "passive"))
    )
    (net (code "21") (name "/C") (class "Default")
      (node (ref "LED115") (pin "1") (pinfunction "K_1") (pintype "passive"))
      (node (ref "LED131") (pin "1") (pinfunction "K_1") (pintype "passive"))
      (node (ref "LED147") (pin "1") (pinfunction "K_1") (pintype "passive"))
      (node (ref "LED163") (pin "1") (pinfunction "K_1") (pintype "passive"))
      (node (ref "LED179") (pin "1") (pinfunction "K_1") (pintype "passive"))
      (node (ref "LED19") (pin "1") (pinfunction "K_1") (pintype "passive"))
      (node (ref "LED195") (pin "1") (pinfunction "K_1") (pintype "passive"))
      (node (ref "LED211") (pin "1") (pinfunction "K_1") (pintype "passive"))
      (node (ref "LED227") (pin "1") (pinfunction "K_1") (pintype "passive"))
      (node (ref "LED243") (pin "1") (pinfunction "K_1") (pintype "passive"))
      (node (ref "LED3") (pin "1") (pinfunction "K_1") (pintype "passive"))
      (node (ref "LED35") (pin "1") (pinfunction "K_1") (pintype "passive"))
      (node (ref "LED51") (pin "1") (pinfunction "K_1") (pintype "passive"))
      (node (ref "LED67") (pin "1") (pinfunction "K_1") (pintype "passive"))
      (node (ref "LED83") (pin "1") (pinfunction "K_1") (pintype "passive"))
      (node (ref "LED99") (pin "1") (pinfunction "K_1") (pintype "passive"))
      (node (ref "Q3") (pin "2") (pinfunction "D_2") (pintype "passive"))
      (node (ref "R3") (pin "2") (pinfunction "2_2") (pintype "passive"))
    )
    (net (code "22") (name "/D") (class "Default")
      (node (ref "LED100") (pin "1") (pinfunction "K_1") (pintype "passive"))
      (node (ref "LED116") (pin "1") (pinfunction "K_1") (pintype "passive"))
      (node (ref "LED132") (pin "1") (pinfunction "K_1") (pintype "passive"))
      (node (ref "LED148") (pin "1") (pinfunction "K_1") (pintype "passive"))
      (node (ref "LED164") (pin "1") (pinfunction "K_1") (pintype "passive"))
      (node (ref "LED180") (pin "1") (pinfunction "K_1") (pintype "passive"))
      (node (ref "LED196") (pin "1") (pinfunction "K_1") (pintype "passive"))
      (node (ref "LED20") (pin "1") (pinfunction "K_1") (pintype "passive"))
      (node (ref "LED212") (pin "1") (pinfunction "K_1") (pintype "passive"))
      (node (ref "LED228") (pin "1") (pinfunction "K_1") (pintype "passive"))
      (node (ref "LED244") (pin "1") (pinfunction "K_1") (pintype "passive"))
      (node (ref "LED36") (pin "1") (pinfunction "K_1") (pintype "passive"))
      (node (ref "LED4") (pin "1") (pinfunction "K_1") (pintype "passive"))
      (node (ref "LED52") (pin "1") (pinfunction "K_1") (pintype "passive"))
      (node (ref "LED68") (pin "1") (pinfunction "K_1") (pintype "passive"))
      (node (ref "LED84") (pin "1") (pinfunction "K_1") (pintype "passive"))
      (node (ref "Q4") (pin "2") (pinfunction "D_2") (pintype "passive"))
      (node (ref "R4") (pin "2") (pinfunction "2_2") (pintype "passive"))
    )
    (net (code "23") (name "/E") (class "Default")
      (node (ref "LED101") (pin "1") (pinfunction "K_1") (pintype "passive"))
      (node (ref "LED117") (pin "1") (pinfunction "K_1") (pintype "passive"))
      (node (ref "LED133") (pin "1") (pinfunction "K_1") (pintype "passive"))
      (node (ref "LED149") (pin "1") (pinfunction "K_1") (pintype "passive"))
      (node (ref "LED165") (pin "1") (pinfunction "K_1") (pintype "passive"))
      (node (ref "LED181") (pin "1") (pinfunction "K_1") (pintype "passive"))
      (node (ref "LED197") (pin "1") (pinfunction "K_1") (pintype "passive"))
      (node (ref "LED21") (pin "1") (pinfunction "K_1") (pintype "passive"))
      (node (ref "LED213") (pin "1") (pinfunction "K_1") (pintype "passive"))
      (node (ref "LED229") (pin "1") (pinfunction "K_1") (pintype "passive"))
      (node (ref "LED245") (pin "1") (pinfunction "K_1") (pintype "passive"))
      (node (ref "LED37") (pin "1") (pinfunction "K_1") (pintype "passive"))
      (node (ref "LED5") (pin "1") (pinfunction "K_1") (pintype "passive"))
      (node (ref "LED53") (pin "1") (pinfunction "K_1") (pintype "passive"))
      (node (ref "LED69") (pin "1") (pinfunction "K_1") (pintype "passive"))
      (node (ref "LED85") (pin "1") (pinfunction "K_1") (pintype "passive"))
      (node (ref "Q5") (pin "2") (pinfunction "D_2") (pintype "passive"))
      (node (ref "R5") (pin "2") (pinfunction "2_2") (pintype "passive"))
    )
    (net (code "24") (name "/F") (class "Default")
      (node (ref "LED102") (pin "1") (pinfunction "K_1") (pintype "passive"))
      (node (ref "LED118") (pin "1") (pinfunction "K_1") (pintype "passive"))
      (node (ref "LED134") (pin "1") (pinfunction "K_1") (pintype "passive"))
      (node (ref "LED150") (pin "1") (pinfunction "K_1") (pintype "passive"))
      (node (ref "LED166") (pin "1") (pinfunction "K_1") (pintype "passive"))
      (node (ref "LED182") (pin "1") (pinfunction "K_1") (pintype "passive"))
      (node (ref "LED198") (pin "1") (pinfunction "K_1") (pintype "passive"))
      (node (ref "LED214") (pin "1") (pinfunction "K_1") (pintype "passive"))
      (node (ref "LED22") (pin "1") (pinfunction "K_1") (pintype "passive"))
      (node (ref "LED230") (pin "1") (pinfunction "K_1") (pintype "passive"))
      (node (ref "LED246") (pin "1") (pinfunction "K_1") (pintype "passive"))
      (node (ref "LED38") (pin "1") (pinfunction "K_1") (pintype "passive"))
      (node (ref "LED54") (pin "1") (pinfunction "K_1") (pintype "passive"))
      (node (ref "LED6") (pin "1") (pinfunction "K_1") (pintype "passive"))
      (node (ref "LED70") (pin "1") (pinfunction "K_1") (pintype "passive"))
      (node (ref "LED86") (pin "1") (pinfunction "K_1") (pintype "passive"))
      (node (ref "Q6") (pin "2") (pinfunction "D_2") (pintype "passive"))
      (node (ref "R6") (pin "2") (pinfunction "2_2") (pintype "passive"))
    )
    (net (code "25") (name "/G") (class "Default")
      (node (ref "LED103") (pin "1") (pinfunction "K_1") (pintype "passive"))
      (node (ref "LED119") (pin "1") (pinfunction "K_1") (pintype "passive"))
      (node (ref "LED135") (pin "1") (pinfunction "K_1") (pintype "passive"))
      (node (ref "LED151") (pin "1") (pinfunction "K_1") (pintype "passive"))
      (node (ref "LED167") (pin "1") (pinfunction "K_1") (pintype "passive"))
      (node (ref "LED183") (pin "1") (pinfunction "K_1") (pintype "passive"))
      (node (ref "LED199") (pin "1") (pinfunction "K_1") (pintype "passive"))
      (node (ref "LED215") (pin "1") (pinfunction "K_1") (pintype "passive"))
      (node (ref "LED23") (pin "1") (pinfunction "K_1") (pintype "passive"))
      (node (ref "LED231") (pin "1") (pinfunction "K_1") (pintype "passive"))
      (node (ref "LED247") (pin "1") (pinfunction "K_1") (pintype "passive"))
      (node (ref "LED39") (pin "1") (pinfunction "K_1") (pintype "passive"))
      (node (ref "LED55") (pin "1") (pinfunction "K_1") (pintype "passive"))
      (node (ref "LED7") (pin "1") (pinfunction "K_1") (pintype "passive"))
      (node (ref "LED71") (pin "1") (pinfunction "K_1") (pintype "passive"))
      (node (ref "LED87") (pin "1") (pinfunction "K_1") (pintype "passive"))
      (node (ref "Q7") (pin "2") (pinfunction "D_2") (pintype "passive"))
      (node (ref "R7") (pin "2") (pinfunction "2_2") (pintype "passive"))
    )
    (net (code "26") (name "/H") (class "Default")
      (node (ref "LED104") (pin "1") (pinfunction "K_1") (pintype "passive"))
      (node (ref "LED120") (pin "1") (pinfunction "K_1") (pintype "passive"))
      (node (ref "LED136") (pin "1") (pinfunction "K_1") (pintype "passive"))
      (node (ref "LED152") (pin "1") (pinfunction "K_1") (pintype "passive"))
      (node (ref "LED168") (pin "1") (pinfunction "K_1") (pintype "passive"))
      (node (ref "LED184") (pin "1") (pinfunction "K_1") (pintype "passive"))
      (node (ref "LED200") (pin "1") (pinfunction "K_1") (pintype "passive"))
      (node (ref "LED216") (pin "1") (pinfunction "K_1") (pintype "passive"))
      (node (ref "LED232") (pin "1") (pinfunction "K_1") (pintype "passive"))
      (node (ref "LED24") (pin "1") (pinfunction "K_1") (pintype "passive"))
      (node (ref "LED248") (pin "1") (pinfunction "K_1") (pintype "passive"))
      (node (ref "LED40") (pin "1") (pinfunction "K_1") (pintype "passive"))
      (node (ref "LED56") (pin "1") (pinfunction "K_1") (pintype "passive"))
      (node (ref "LED72") (pin "1") (pinfunction "K_1") (pintype "passive"))
      (node (ref "LED8") (pin "1") (pinfunction "K_1") (pintype "passive"))
      (node (ref "LED88") (pin "1") (pinfunction "K_1") (pintype "passive"))
      (node (ref "Q8") (pin "2") (pinfunction "D_2") (pintype "passive"))
      (node (ref "R8") (pin "2") (pinfunction "2_2") (pintype "passive"))
    )
    (net (code "27") (name "/I") (class "Default")
      (node (ref "LED105") (pin "1") (pinfunction "K_1") (pintype "passive"))
      (node (ref "LED121") (pin "1") (pinfunction "K_1") (pintype "passive"))
      (node (ref "LED137") (pin "1") (pinfunction "K_1") (pintype "passive"))
      (node (ref "LED153") (pin "1") (pinfunction "K_1") (pintype "passive"))
      (node (ref "LED169") (pin "1") (pinfunction "K_1") (pintype "passive"))
      (node (ref "LED185") (pin "1") (pinfunction "K_1") (pintype "passive"))
      (node (ref "LED201") (pin "1") (pinfunction "K_1") (pintype "passive"))
      (node (ref "LED217") (pin "1") (pinfunction "K_1") (pintype "passive"))
      (node (ref "LED233") (pin "1") (pinfunction "K_1") (pintype "passive"))
      (node (ref "LED249") (pin "1") (pinfunction "K_1") (pintype "passive"))
      (node (ref "LED25") (pin "1") (pinfunction "K_1") (pintype "passive"))
      (node (ref "LED41") (pin "1") (pinfunction "K_1") (pintype "passive"))
      (node (ref "LED57") (pin "1") (pinfunction "K_1") (pintype "passive"))
      (node (ref "LED73") (pin "1") (pinfunction "K_1") (pintype "passive"))
      (node (ref "LED89") (pin "1") (pinfunction "K_1") (pintype "passive"))
      (node (ref "LED9") (pin "1") (pinfunction "K_1") (pintype "passive"))
      (node (ref "Q9") (pin "2") (pinfunction "D_2") (pintype "passive"))
      (node (ref "R9") (pin "2") (pinfunction "2_2") (pintype "passive"))
    )
    (net (code "28") (name "/J") (class "Default")
      (node (ref "LED10") (pin "1") (pinfunction "K_1") (pintype "passive"))
      (node (ref "LED106") (pin "1") (pinfunction "K_1") (pintype "passive"))
      (node (ref "LED122") (pin "1") (pinfunction "K_1") (pintype "passive"))
      (node (ref "LED138") (pin "1") (pinfunction "K_1") (pintype "passive"))
      (node (ref "LED154") (pin "1") (pinfunction "K_1") (pintype "passive"))
      (node (ref "LED170") (pin "1") (pinfunction "K_1") (pintype "passive"))
      (node (ref "LED186") (pin "1") (pinfunction "K_1") (pintype "passive"))
      (node (ref "LED202") (pin "1") (pinfunction "K_1") (pintype "passive"))
      (node (ref "LED218") (pin "1") (pinfunction "K_1") (pintype "passive"))
      (node (ref "LED234") (pin "1") (pinfunction "K_1") (pintype "passive"))
      (node (ref "LED250") (pin "1") (pinfunction "K_1") (pintype "passive"))
      (node (ref "LED26") (pin "1") (pinfunction "K_1") (pintype "passive"))
      (node (ref "LED42") (pin "1") (pinfunction "K_1") (pintype "passive"))
      (node (ref "LED58") (pin "1") (pinfunction "K_1") (pintype "passive"))
      (node (ref "LED74") (pin "1") (pinfunction "K_1") (pintype "passive"))
      (node (ref "LED90") (pin "1") (pinfunction "K_1") (pintype "passive"))
      (node (ref "Q10") (pin "2") (pinfunction "D_2") (pintype "passive"))
      (node (ref "R10") (pin "2") (pinfunction "2_2") (pintype "passive"))
    )
    (net (code "29") (name "/K") (class "Default")
      (node (ref "LED107") (pin "1") (pinfunction "K_1") (pintype "passive"))
      (node (ref "LED11") (pin "1") (pinfunction "K_1") (pintype "passive"))
      (node (ref "LED123") (pin "1") (pinfunction "K_1") (pintype "passive"))
      (node (ref "LED139") (pin "1") (pinfunction "K_1") (pintype "passive"))
      (node (ref "LED155") (pin "1") (pinfunction "K_1") (pintype "passive"))
      (node (ref "LED171") (pin "1") (pinfunction "K_1") (pintype "passive"))
      (node (ref "LED187") (pin "1") (pinfunction "K_1") (pintype "passive"))
      (node (ref "LED203") (pin "1") (pinfunction "K_1") (pintype "passive"))
      (node (ref "LED219") (pin "1") (pinfunction "K_1") (pintype "passive"))
      (node (ref "LED235") (pin "1") (pinfunction "K_1") (pintype "passive"))
      (node (ref "LED251") (pin "1") (pinfunction "K_1") (pintype "passive"))
      (node (ref "LED27") (pin "1") (pinfunction "K_1") (pintype "passive"))
      (node (ref "LED43") (pin "1") (pinfunction "K_1") (pintype "passive"))
      (node (ref "LED59") (pin "1") (pinfunction "K_1") (pintype "passive"))
      (node (ref "LED75") (pin "1") (pinfunction "K_1") (pintype "passive"))
      (node (ref "LED91") (pin "1") (pinfunction "K_1") (pintype "passive"))
      (node (ref "Q11") (pin "2") (pinfunction "D_2") (pintype "passive"))
      (node (ref "R11") (pin "2") (pinfunction "2_2") (pintype "passive"))
    )
    (net (code "30") (name "/L") (class "Default")
      (node (ref "LED108") (pin "1") (pinfunction "K_1") (pintype "passive"))
      (node (ref "LED12") (pin "1") (pinfunction "K_1") (pintype "passive"))
      (node (ref "LED124") (pin "1") (pinfunction "K_1") (pintype "passive"))
      (node (ref "LED140") (pin "1") (pinfunction "K_1") (pintype "passive"))
      (node (ref "LED156") (pin "1") (pinfunction "K_1") (pintype "passive"))
      (node (ref "LED172") (pin "1") (pinfunction "K_1") (pintype "passive"))
      (node (ref "LED188") (pin "1") (pinfunction "K_1") (pintype "passive"))
      (node (ref "LED204") (pin "1") (pinfunction "K_1") (pintype "passive"))
      (node (ref "LED220") (pin "1") (pinfunction "K_1") (pintype "passive"))
      (node (ref "LED236") (pin "1") (pinfunction "K_1") (pintype "passive"))
      (node (ref "LED252") (pin "1") (pinfunction "K_1") (pintype "passive"))
      (node (ref "LED28") (pin "1") (pinfunction "K_1") (pintype "passive"))
      (node (ref "LED44") (pin "1") (pinfunction "K_1") (pintype "passive"))
      (node (ref "LED60") (pin "1") (pinfunction "K_1") (pintype "passive"))
      (node (ref "LED76") (pin "1") (pinfunction "K_1") (pintype "passive"))
      (node (ref "LED92") (pin "1") (pinfunction "K_1") (pintype "passive"))
      (node (ref "Q12") (pin "2") (pinfunction "D_2") (pintype "passive"))
      (node (ref "R12") (pin "2") (pinfunction "2_2") (pintype "passive"))
    )
    (net (code "31") (name "/M") (class "Default")
      (node (ref "LED109") (pin "1") (pinfunction "K_1") (pintype "passive"))
      (node (ref "LED125") (pin "1") (pinfunction "K_1") (pintype "passive"))
      (node (ref "LED13") (pin "1") (pinfunction "K_1") (pintype "passive"))
      (node (ref "LED141") (pin "1") (pinfunction "K_1") (pintype "passive"))
      (node (ref "LED157") (pin "1") (pinfunction "K_1") (pintype "passive"))
      (node (ref "LED173") (pin "1") (pinfunction "K_1") (pintype "passive"))
      (node (ref "LED189") (pin "1") (pinfunction "K_1") (pintype "passive"))
      (node (ref "LED205") (pin "1") (pinfunction "K_1") (pintype "passive"))
      (node (ref "LED221") (pin "1") (pinfunction "K_1") (pintype "passive"))
      (node (ref "LED237") (pin "1") (pinfunction "K_1") (pintype "passive"))
      (node (ref "LED253") (pin "1") (pinfunction "K_1") (pintype "passive"))
      (node (ref "LED29") (pin "1") (pinfunction "K_1") (pintype "passive"))
      (node (ref "LED45") (pin "1") (pinfunction "K_1") (pintype "passive"))
      (node (ref "LED61") (pin "1") (pinfunction "K_1") (pintype "passive"))
      (node (ref "LED77") (pin "1") (pinfunction "K_1") (pintype "passive"))
      (node (ref "LED93") (pin "1") (pinfunction "K_1") (pintype "passive"))
      (node (ref "Q13") (pin "2") (pinfunction "D_2") (pintype "passive"))
      (node (ref "R13") (pin "2") (pinfunction "2_2") (pintype "passive"))
    )
    (net (code "32") (name "/N") (class "Default")
      (node (ref "LED110") (pin "1") (pinfunction "K_1") (pintype "passive"))
      (node (ref "LED126") (pin "1") (pinfunction "K_1") (pintype "passive"))
      (node (ref "LED14") (pin "1") (pinfunction "K_1") (pintype "passive"))
      (node (ref "LED142") (pin "1") (pinfunction "K_1") (pintype "passive"))
      (node (ref "LED158") (pin "1") (pinfunction "K_1") (pintype "passive"))
      (node (ref "LED174") (pin "1") (pinfunction "K_1") (pintype "passive"))
      (node (ref "LED190") (pin "1") (pinfunction "K_1") (pintype "passive"))
      (node (ref "LED206") (pin "1") (pinfunction "K_1") (pintype "passive"))
      (node (ref "LED222") (pin "1") (pinfunction "K_1") (pintype "passive"))
      (node (ref "LED238") (pin "1") (pinfunction "K_1") (pintype "passive"))
      (node (ref "LED254") (pin "1") (pinfunction "K_1") (pintype "passive"))
      (node (ref "LED30") (pin "1") (pinfunction "K_1") (pintype "passive"))
      (node (ref "LED46") (pin "1") (pinfunction "K_1") (pintype "passive"))
      (node (ref "LED62") (pin "1") (pinfunction "K_1") (pintype "passive"))
      (node (ref "LED78") (pin "1") (pinfunction "K_1") (pintype "passive"))
      (node (ref "LED94") (pin "1") (pinfunction "K_1") (pintype "passive"))
      (node (ref "Q14") (pin "2") (pinfunction "D_2") (pintype "passive"))
      (node (ref "R14") (pin "2") (pinfunction "2_2") (pintype "passive"))
    )
    (net (code "33") (name "/O") (class "Default")
      (node (ref "LED111") (pin "1") (pinfunction "K_1") (pintype "passive"))
      (node (ref "LED127") (pin "1") (pinfunction "K_1") (pintype "passive"))
      (node (ref "LED143") (pin "1") (pinfunction "K_1") (pintype "passive"))
      (node (ref "LED15") (pin "1") (pinfunction "K_1") (pintype "passive"))
      (node (ref "LED159") (pin "1") (pinfunction "K_1") (pintype "passive"))
      (node (ref "LED175") (pin "1") (pinfunction "K_1") (pintype "passive"))
      (node (ref "LED191") (pin "1") (pinfunction "K_1") (pintype "passive"))
      (node (ref "LED207") (pin "1") (pinfunction "K_1") (pintype "passive"))
      (node (ref "LED223") (pin "1") (pinfunction "K_1") (pintype "passive"))
      (node (ref "LED239") (pin "1") (pinfunction "K_1") (pintype "passive"))
      (node (ref "LED255") (pin "1") (pinfunction "K_1") (pintype "passive"))
      (node (ref "LED31") (pin "1") (pinfunction "K_1") (pintype "passive"))
      (node (ref "LED47") (pin "1") (pinfunction "K_1") (pintype "passive"))
      (node (ref "LED63") (pin "1") (pinfunction "K_1") (pintype "passive"))
      (node (ref "LED79") (pin "1") (pinfunction "K_1") (pintype "passive"))
      (node (ref "LED95") (pin "1") (pinfunction "K_1") (pintype "passive"))
      (node (ref "Q15") (pin "2") (pinfunction "D_2") (pintype "passive"))
      (node (ref "R15") (pin "2") (pinfunction "2_2") (pintype "passive"))
    )
    (net (code "34") (name "/P") (class "Default")
      (node (ref "LED112") (pin "1") (pinfunction "K_1") (pintype "passive"))
      (node (ref "LED128") (pin "1") (pinfunction "K_1") (pintype "passive"))
      (node (ref "LED144") (pin "1") (pinfunction "K_1") (pintype "passive"))
      (node (ref "LED16") (pin "1") (pinfunction "K_1") (pintype "passive"))
      (node (ref "LED160") (pin "1") (pinfunction "K_1") (pintype "passive"))
      (node (ref "LED176") (pin "1") (pinfunction "K_1") (pintype "passive"))
      (node (ref "LED192") (pin "1") (pinfunction "K_1") (pintype "passive"))
      (node (ref "LED208") (pin "1") (pinfunction "K_1") (pintype "passive"))
      (node (ref "LED224") (pin "1") (pinfunction "K_1") (pintype "passive"))
      (node (ref "LED240") (pin "1") (pinfunction "K_1") (pintype "passive"))
      (node (ref "LED256") (pin "1") (pinfunction "K_1") (pintype "passive"))
      (node (ref "LED32") (pin "1") (pinfunction "K_1") (pintype "passive"))
      (node (ref "LED48") (pin "1") (pinfunction "K_1") (pintype "passive"))
      (node (ref "LED64") (pin "1") (pinfunction "K_1") (pintype "passive"))
      (node (ref "LED80") (pin "1") (pinfunction "K_1") (pintype "passive"))
      (node (ref "LED96") (pin "1") (pinfunction "K_1") (pintype "passive"))
      (node (ref "Q16") (pin "2") (pinfunction "D_2") (pintype "passive"))
      (node (ref "R16") (pin "2") (pinfunction "2_2") (pintype "passive"))
    )
    (net (code "35") (name "GND") (class "Default")
      (node (ref "C1") (pin "1") (pinfunction "1_1") (pintype "passive"))
      (node (ref "C2") (pin "1") (pinfunction "1_1") (pintype "passive"))
      (node (ref "C3") (pin "1") (pinfunction "1_1") (pintype "passive"))
      (node (ref "C4") (pin "1") (pinfunction "1_1") (pintype "passive"))
      (node (ref "C5") (pin "2") (pinfunction "2_2") (pintype "passive"))
      (node (ref "C6") (pin "2") (pinfunction "2_2") (pintype "passive"))
      (node (ref "J3") (pin "1") (pinfunction "1_1") (pintype "passive"))
      (node (ref "Q1") (pin "3") (pinfunction "S_3") (pintype "passive"))
      (node (ref "Q10") (pin "3") (pinfunction "S_3") (pintype "passive"))
      (node (ref "Q11") (pin "3") (pinfunction "S_3") (pintype "passive"))
      (node (ref "Q12") (pin "3") (pinfunction "S_3") (pintype "passive"))
      (node (ref "Q13") (pin "3") (pinfunction "S_3") (pintype "passive"))
      (node (ref "Q14") (pin "3") (pinfunction "S_3") (pintype "passive"))
      (node (ref "Q15") (pin "3") (pinfunction "S_3") (pintype "passive"))
      (node (ref "Q16") (pin "3") (pinfunction "S_3") (pintype "passive"))
      (node (ref "Q18") (pin "1") (pinfunction "SOURCE_1") (pintype "passive"))
      (node (ref "Q2") (pin "3") (pinfunction "S_3") (pintype "passive"))
      (node (ref "Q3") (pin "3") (pinfunction "S_3") (pintype "passive"))
      (node (ref "Q4") (pin "3") (pinfunction "S_3") (pintype "passive"))
      (node (ref "Q5") (pin "3") (pinfunction "S_3") (pintype "passive"))
      (node (ref "Q6") (pin "3") (pinfunction "S_3") (pintype "passive"))
      (node (ref "Q7") (pin "3") (pinfunction "S_3") (pintype "passive"))
      (node (ref "Q8") (pin "3") (pinfunction "S_3") (pintype "passive"))
      (node (ref "Q9") (pin "3") (pinfunction "S_3") (pintype "passive"))
      (node (ref "R18") (pin "1") (pinfunction "1_1") (pintype "passive"))
      (node (ref "R26") (pin "1") (pinfunction "1_1") (pintype "passive"))
      (node (ref "R35") (pin "2") (pinfunction "2_2") (pintype "passive"))
      (node (ref "R37") (pin "2") (pinfunction "2_2") (pintype "passive"))
      (node (ref "R43") (pin "2") (pinfunction "2_2") (pintype "passive"))
      (node (ref "R44") (pin "2") (pinfunction "2_2") (pintype "passive"))
      (node (ref "R46") (pin "2") (pinfunction "2_2") (pintype "passive"))
      (node (ref "R47") (pin "2") (pinfunction "2_2") (pintype "passive"))
      (node (ref "R48") (pin "2") (pinfunction "2_2") (pintype "passive"))
      (node (ref "R50") (pin "2") (pinfunction "2_2") (pintype "passive"))
      (node (ref "R51") (pin "2") (pinfunction "2_2") (pintype "passive"))
      (node (ref "R52") (pin "2") (pinfunction "2_2") (pintype "passive"))
      (node (ref "R55") (pin "2") (pinfunction "2_2") (pintype "passive"))
      (node (ref "R56") (pin "2") (pinfunction "2_2") (pintype "passive"))
      (node (ref "R58") (pin "2") (pinfunction "2_2") (pintype "passive"))
      (node (ref "R59") (pin "2") (pinfunction "2_2") (pintype "passive"))
      (node (ref "U1") (pin "12") (pinfunction "GND_12") (pintype "passive"))
      (node (ref "U1") (pin "23") (pinfunction "E#_23") (pintype "passive"))
      (node (ref "U2") (pin "8") (pinfunction "GND_8") (pintype "passive"))
      (node (ref "U3") (pin "10") (pinfunction "GND_10") (pintype "passive"))
      (node (ref "U3") (pin "19") (pinfunction "OE2#_19") (pintype "passive"))
      (node (ref "U4") (pin "8") (pinfunction "GND_8") (pintype "passive"))
      (node (ref "U5") (pin "10") (pinfunction "GND_10") (pintype "passive"))
      (node (ref "U5") (pin "19") (pinfunction "OE2#_19") (pintype "passive"))
      (node (ref "U6") (pin "14") (pinfunction "GND_14") (pintype "passive"))
      (node (ref "U7") (pin "2") (pinfunction "GND_2") (pintype "passive"))
      (node (ref "U7") (pin "4") (pinfunction "GND_4") (pintype "passive"))
    )
    (net (code "36") (name "Net-(C4-Pad2)") (class "Default")
      (node (ref "C4") (pin "2") (pinfunction "2_2") (pintype "passive"))
      (node (ref "R30") (pin "1") (pinfunction "1_1") (pintype "passive"))
      (node (ref "X1") (pin "2") (pinfunction "2_2") (pintype "passive"))
    )
    (net (code "37") (name "Net-(Q1-G)") (class "Default")
      (node (ref "Q1") (pin "1") (pinfunction "G_1") (pintype "passive"))
      (node (ref "U1") (pin "11") (pinfunction "Q0_11") (pintype "passive"))
    )
    (net (code "38") (name "Net-(Q2-G)") (class "Default")
      (node (ref "Q2") (pin "1") (pinfunction "G_1") (pintype "passive"))
      (node (ref "U1") (pin "9") (pinfunction "Q1_9") (pintype "passive"))
    )
    (net (code "39") (name "Net-(Q3-G)") (class "Default")
      (node (ref "Q3") (pin "1") (pinfunction "G_1") (pintype "passive"))
      (node (ref "U1") (pin "10") (pinfunction "Q2_10") (pintype "passive"))
    )
    (net (code "40") (name "Net-(Q4-G)") (class "Default")
      (node (ref "Q4") (pin "1") (pinfunction "G_1") (pintype "passive"))
      (node (ref "U1") (pin "8") (pinfunction "Q3_8") (pintype "passive"))
    )
    (net (code "41") (name "Net-(Q5-G)") (class "Default")
      (node (ref "Q5") (pin "1") (pinfunction "G_1") (pintype "passive"))
      (node (ref "U1") (pin "7") (pinfunction "Q4_7") (pintype "passive"))
    )
    (net (code "42") (name "Net-(Q6-G)") (class "Default")
      (node (ref "Q6") (pin "1") (pinfunction "G_1") (pintype "passive"))
      (node (ref "U1") (pin "6") (pinfunction "Q5_6") (pintype "passive"))
    )
    (net (code "43") (name "Net-(Q7-G)") (class "Default")
      (node (ref "Q7") (pin "1") (pinfunction "G_1") (pintype "passive"))
      (node (ref "U1") (pin "5") (pinfunction "Q6_5") (pintype "passive"))
    )
    (net (code "44") (name "Net-(Q8-G)") (class "Default")
      (node (ref "Q8") (pin "1") (pinfunction "G_1") (pintype "passive"))
      (node (ref "U1") (pin "4") (pinfunction "Q7_4") (pintype "passive"))
    )
    (net (code "45") (name "Net-(Q9-G)") (class "Default")
      (node (ref "Q9") (pin "1") (pinfunction "G_1") (pintype "passive"))
      (node (ref "U1") (pin "18") (pinfunction "Q8_18") (pintype "passive"))
    )
    (net (code "46") (name "Net-(Q10-G)") (class "Default")
      (node (ref "Q10") (pin "1") (pinfunction "G_1") (pintype "passive"))
      (node (ref "U1") (pin "17") (pinfunction "Q9_17") (pintype "passive"))
    )
    (net (code "47") (name "Net-(Q11-G)") (class "Default")
      (node (ref "Q11") (pin "1") (pinfunction "G_1") (pintype "passive"))
      (node (ref "U1") (pin "20") (pinfunction "Q10_20") (pintype "passive"))
    )
    (net (code "48") (name "Net-(Q12-G)") (class "Default")
      (node (ref "Q12") (pin "1") (pinfunction "G_1") (pintype "passive"))
      (node (ref "U1") (pin "19") (pinfunction "Q11_19") (pintype "passive"))
    )
    (net (code "49") (name "Net-(Q13-G)") (class "Default")
      (node (ref "Q13") (pin "1") (pinfunction "G_1") (pintype "passive"))
      (node (ref "U1") (pin "14") (pinfunction "Q12_14") (pintype "passive"))
    )
    (net (code "50") (name "Net-(Q14-G)") (class "Default")
      (node (ref "Q14") (pin "1") (pinfunction "G_1") (pintype "passive"))
      (node (ref "U1") (pin "13") (pinfunction "Q13_13") (pintype "passive"))
    )
    (net (code "51") (name "Net-(Q15-G)") (class "Default")
      (node (ref "Q15") (pin "1") (pinfunction "G_1") (pintype "passive"))
      (node (ref "U1") (pin "16") (pinfunction "Q14_16") (pintype "passive"))
    )
    (net (code "52") (name "Net-(Q16-G)") (class "Default")
      (node (ref "Q16") (pin "1") (pinfunction "G_1") (pintype "passive"))
      (node (ref "U1") (pin "15") (pinfunction "Q15_15") (pintype "passive"))
    )
    (net (code "53") (name "Net-(Q17-D)") (class "Default")
      (node (ref "Q17") (pin "3") (pinfunction "D_3") (pintype "passive"))
      (node (ref "R19") (pin "1") (pinfunction "1_1") (pintype "passive"))
    )
    (net (code "54") (name "Net-(Q17-G)") (class "Default")
      (node (ref "Q17") (pin "1") (pinfunction "G_1") (pintype "passive"))
      (node (ref "R17") (pin "2") (pinfunction "2_2") (pintype "passive"))
      (node (ref "U3") (pin "18") (pinfunction "Y0_18") (pintype "passive"))
    )
    (net (code "55") (name "Net-(Q18-DRAIN)") (class "Default")
      (node (ref "Q18") (pin "3") (pinfunction "DRAIN_3") (pintype "passive"))
      (node (ref "R21") (pin "1") (pinfunction "1_1") (pintype "passive"))
      (node (ref "U3") (pin "1") (pinfunction "OE1#_1") (pintype "passive"))
    )
    (net (code "56") (name "Net-(Q18-GATE)") (class "Default")
      (node (ref "Q18") (pin "2") (pinfunction "GATE_2") (pintype "passive"))
      (node (ref "U4") (pin "15") (pinfunction "QA_15") (pintype "passive"))
      (node (ref "U5") (pin "1") (pinfunction "OE1#_1") (pintype "passive"))
      (node (ref "U6") (pin "10") (pinfunction "A0_10") (pintype "passive"))
    )
    (net (code "57") (name "Net-(Q19-D)") (class "Default")
      (node (ref "Q19") (pin "3") (pinfunction "D_3") (pintype "passive"))
      (node (ref "R22") (pin "1") (pinfunction "1_1") (pintype "passive"))
    )
    (net (code "58") (name "Net-(Q19-G)") (class "Default")
      (node (ref "Q19") (pin "1") (pinfunction "G_1") (pintype "passive"))
      (node (ref "R20") (pin "1") (pinfunction "1_1") (pintype "passive"))
      (node (ref "U3") (pin "17") (pinfunction "Y1_17") (pintype "passive"))
    )
    (net (code "59") (name "Net-(Q20-D)") (class "Default")
      (node (ref "Q20") (pin "3") (pinfunction "D_3") (pintype "passive"))
      (node (ref "R24") (pin "1") (pinfunction "1_1") (pintype "passive"))
    )
    (net (code "60") (name "Net-(Q20-G)") (class "Default")
      (node (ref "Q20") (pin "1") (pinfunction "G_1") (pintype "passive"))
      (node (ref "R23") (pin "1") (pinfunction "1_1") (pintype "passive"))
      (node (ref "U3") (pin "16") (pinfunction "Y2_16") (pintype "passive"))
    )
    (net (code "61") (name "Net-(Q21-D)") (class "Default")
      (node (ref "Q21") (pin "3") (pinfunction "D_3") (pintype "passive"))
      (node (ref "R27") (pin "1") (pinfunction "1_1") (pintype "passive"))
    )
    (net (code "62") (name "Net-(Q21-G)") (class "Default")
      (node (ref "Q21") (pin "1") (pinfunction "G_1") (pintype "passive"))
      (node (ref "R25") (pin "1") (pinfunction "1_1") (pintype "passive"))
      (node (ref "U3") (pin "15") (pinfunction "Y3_15") (pintype "passive"))
    )
    (net (code "63") (name "Net-(Q22-D)") (class "Default")
      (node (ref "Q22") (pin "3") (pinfunction "D_3") (pintype "passive"))
      (node (ref "R31") (pin "1") (pinfunction "1_1") (pintype "passive"))
    )
    (net (code "64") (name "Net-(Q22-G)") (class "Default")
      (node (ref "Q22") (pin "1") (pinfunction "G_1") (pintype "passive"))
      (node (ref "R69") (pin "1") (pinfunction "1_1") (pintype "passive"))
      (node (ref "U3") (pin "14") (pinfunction "Y4_14") (pintype "passive"))
    )
    (net (code "65") (name "Net-(Q23-D)") (class "Default")
      (node (ref "Q23") (pin "3") (pinfunction "D_3") (pintype "passive"))
      (node (ref "R34") (pin "1") (pinfunction "1_1") (pintype "passive"))
    )
    (net (code "66") (name "Net-(Q23-G)") (class "Default")
      (node (ref "Q23") (pin "1") (pinfunction "G_1") (pintype "passive"))
      (node (ref "R32") (pin "1") (pinfunction "1_1") (pintype "passive"))
      (node (ref "U3") (pin "13") (pinfunction "Y5_13") (pintype "passive"))
    )
    (net (code "67") (name "Net-(Q24-D)") (class "Default")
      (node (ref "Q24") (pin "3") (pinfunction "D_3") (pintype "passive"))
      (node (ref "R38") (pin "1") (pinfunction "1_1") (pintype "passive"))
    )
    (net (code "68") (name "Net-(Q24-G)") (class "Default")
      (node (ref "Q24") (pin "1") (pinfunction "G_1") (pintype "passive"))
      (node (ref "R36") (pin "1") (pinfunction "1_1") (pintype "passive"))
      (node (ref "U3") (pin "12") (pinfunction "Y6_12") (pintype "passive"))
    )
    (net (code "69") (name "Net-(Q25-D)") (class "Default")
      (node (ref "Q25") (pin "3") (pinfunction "D_3") (pintype "passive"))
      (node (ref "R40") (pin "1") (pinfunction "1_1") (pintype "passive"))
    )
    (net (code "70") (name "Net-(Q25-G)") (class "Default")
      (node (ref "Q25") (pin "1") (pinfunction "G_1") (pintype "passive"))
      (node (ref "R39") (pin "1") (pinfunction "1_1") (pintype "passive"))
      (node (ref "U3") (pin "11") (pinfunction "Y7_11") (pintype "passive"))
    )
    (net (code "71") (name "Net-(Q26-D)") (class "Default")
      (node (ref "Q26") (pin "3") (pinfunction "D_3") (pintype "passive"))
      (node (ref "R42") (pin "1") (pinfunction "1_1") (pintype "passive"))
    )
    (net (code "72") (name "Net-(Q26-G)") (class "Default")
      (node (ref "Q26") (pin "1") (pinfunction "G_1") (pintype "passive"))
      (node (ref "R41") (pin "1") (pinfunction "1_1") (pintype "passive"))
      (node (ref "U5") (pin "18") (pinfunction "Y0_18") (pintype "passive"))
    )
    (net (code "73") (name "Net-(Q27-D)") (class "Default")
      (node (ref "Q27") (pin "3") (pinfunction "D_3") (pintype "passive"))
      (node (ref "R49") (pin "1") (pinfunction "1_1") (pintype "passive"))
    )
    (net (code "74") (name "Net-(Q27-G)") (class "Default")
      (node (ref "Q27") (pin "1") (pinfunction "G_1") (pintype "passive"))
      (node (ref "R45") (pin "1") (pinfunction "1_1") (pintype "passive"))
      (node (ref "U5") (pin "17") (pinfunction "Y1_17") (pintype "passive"))
    )
    (net (code "75") (name "Net-(Q28-D)") (class "Default")
      (node (ref "Q28") (pin "3") (pinfunction "D_3") (pintype "passive"))
      (node (ref "R54") (pin "1") (pinfunction "1_1") (pintype "passive"))
    )
    (net (code "76") (name "Net-(Q28-G)") (class "Default")
      (node (ref "Q28") (pin "1") (pinfunction "G_1") (pintype "passive"))
      (node (ref "R53") (pin "1") (pinfunction "1_1") (pintype "passive"))
      (node (ref "U5") (pin "16") (pinfunction "Y2_16") (pintype "passive"))
    )
    (net (code "77") (name "Net-(Q29-D)") (class "Default")
      (node (ref "Q29") (pin "3") (pinfunction "D_3") (pintype "passive"))
      (node (ref "R60") (pin "1") (pinfunction "1_1") (pintype "passive"))
    )
    (net (code "78") (name "Net-(Q29-G)") (class "Default")
      (node (ref "Q29") (pin "1") (pinfunction "G_1") (pintype "passive"))
      (node (ref "R57") (pin "1") (pinfunction "1_1") (pintype "passive"))
      (node (ref "U5") (pin "15") (pinfunction "Y3_15") (pintype "passive"))
    )
    (net (code "79") (name "Net-(Q30-D)") (class "Default")
      (node (ref "Q30") (pin "3") (pinfunction "D_3") (pintype "passive"))
      (node (ref "R62") (pin "1") (pinfunction "1_1") (pintype "passive"))
    )
    (net (code "80") (name "Net-(Q30-G)") (class "Default")
      (node (ref "Q30") (pin "1") (pinfunction "G_1") (pintype "passive"))
      (node (ref "R61") (pin "1") (pinfunction "1_1") (pintype "passive"))
      (node (ref "U5") (pin "14") (pinfunction "Y4_14") (pintype "passive"))
    )
    (net (code "81") (name "Net-(Q31-D)") (class "Default")
      (node (ref "Q31") (pin "3") (pinfunction "D_3") (pintype "passive"))
      (node (ref "R64") (pin "1") (pinfunction "1_1") (pintype "passive"))
    )
    (net (code "82") (name "Net-(Q31-G)") (class "Default")
      (node (ref "Q31") (pin "1") (pinfunction "G_1") (pintype "passive"))
      (node (ref "R63") (pin "1") (pinfunction "1_1") (pintype "passive"))
      (node (ref "U5") (pin "13") (pinfunction "Y5_13") (pintype "passive"))
    )
    (net (code "83") (name "Net-(Q32-D)") (class "Default")
      (node (ref "Q32") (pin "3") (pinfunction "D_3") (pintype "passive"))
      (node (ref "R66") (pin "1") (pinfunction "1_1") (pintype "passive"))
    )
    (net (code "84") (name "Net-(Q32-G)") (class "Default")
      (node (ref "Q32") (pin "1") (pinfunction "G_1") (pintype "passive"))
      (node (ref "R65") (pin "1") (pinfunction "1_1") (pintype "passive"))
      (node (ref "U5") (pin "12") (pinfunction "Y6_12") (pintype "passive"))
    )
    (net (code "85") (name "Net-(Q33-D)") (class "Default")
      (node (ref "Q33") (pin "3") (pinfunction "D_3") (pintype "passive"))
      (node (ref "R68") (pin "1") (pinfunction "1_1") (pintype "passive"))
    )
    (net (code "86") (name "Net-(Q33-G)") (class "Default")
      (node (ref "Q33") (pin "1") (pinfunction "G_1") (pintype "passive"))
      (node (ref "R67") (pin "1") (pinfunction "1_1") (pintype "passive"))
      (node (ref "U5") (pin "11") (pinfunction "Y7_11") (pintype "passive"))
    )
    (net (code "87") (name "Net-(R58-Pad1)") (class "Default")
      (node (ref "R58") (pin "1") (pinfunction "1_1") (pintype "passive"))
      (node (ref "SW1") (pin "6") (pinfunction "6_6") (pintype "passive"))
    )
    (net (code "88") (name "Net-(R59-Pad1)") (class "Default")
      (node (ref "R59") (pin "1") (pinfunction "1_1") (pintype "passive"))
      (node (ref "SW1") (pin "5") (pinfunction "5_5") (pintype "passive"))
    )
    (net (code "89") (name "Net-(U1-A0)") (class "Default")
      (node (ref "U1") (pin "2") (pinfunction "A0_2") (pintype "passive"))
      (node (ref "U4") (pin "1") (pinfunction "QB_1") (pintype "passive"))
      (node (ref "U6") (pin "9") (pinfunction "A1_9") (pintype "passive"))
    )
    (net (code "90") (name "Net-(U1-A1)") (class "Default")
      (node (ref "U1") (pin "3") (pinfunction "A1_3") (pintype "passive"))
      (node (ref "U4") (pin "2") (pinfunction "QC_2") (pintype "passive"))
      (node (ref "U6") (pin "8") (pinfunction "A2_8") (pintype "passive"))
    )
    (net (code "91") (name "Net-(U1-A2)") (class "Default")
      (node (ref "U1") (pin "21") (pinfunction "A2_21") (pintype "passive"))
      (node (ref "U4") (pin "3") (pinfunction "QD_3") (pintype "passive"))
      (node (ref "U6") (pin "7") (pinfunction "A3_7") (pintype "passive"))
    )
    (net (code "92") (name "Net-(U1-A3)") (class "Default")
      (node (ref "U1") (pin "22") (pinfunction "A3_22") (pintype "passive"))
      (node (ref "U4") (pin "4") (pinfunction "QE_4") (pintype "passive"))
      (node (ref "U6") (pin "6") (pinfunction "A4_6") (pintype "passive"))
    )
    (net (code "93") (name "Net-(U2-MR)") (class "Default")
      (node (ref "R18") (pin "2") (pinfunction "2_2") (pintype "passive"))
      (node (ref "U2") (pin "12") (pinfunction "MR_12") (pintype "passive"))
    )
    (net (code "94") (name "Net-(U2-Q4)") (class "Default")
      (node (ref "J1") (pin "1") (pinfunction "1_1") (pintype "passive"))
      (node (ref "U2") (pin "7") (pinfunction "Q4_7") (pintype "passive"))
    )
    (net (code "95") (name "Net-(U2-Q5)") (class "Default")
      (node (ref "J1") (pin "2") (pinfunction "2_2") (pintype "passive"))
      (node (ref "U2") (pin "5") (pinfunction "Q5_5") (pintype "passive"))
    )
    (net (code "96") (name "Net-(U2-Q6)") (class "Default")
      (node (ref "J1") (pin "3") (pinfunction "3_3") (pintype "passive"))
      (node (ref "U2") (pin "4") (pinfunction "Q6_4") (pintype "passive"))
    )
    (net (code "97") (name "Net-(U2-Q7)") (class "Default")
      (node (ref "J1") (pin "4") (pinfunction "4_4") (pintype "passive"))
      (node (ref "U2") (pin "6") (pinfunction "Q7_6") (pintype "passive"))
    )
    (net (code "98") (name "Net-(U2-Q8)") (class "Default")
      (node (ref "J1") (pin "5") (pinfunction "5_5") (pintype "passive"))
      (node (ref "U2") (pin "14") (pinfunction "Q8_14") (pintype "passive"))
    )
    (net (code "99") (name "Net-(U2-Q9)") (class "Default")
      (node (ref "J1") (pin "6") (pinfunction "6_6") (pintype "passive"))
      (node (ref "U2") (pin "13") (pinfunction "Q9_13") (pintype "passive"))
    )
    (net (code "100") (name "Net-(U2-Q10)") (class "Default")
      (node (ref "J1") (pin "7") (pinfunction "7_7") (pintype "passive"))
      (node (ref "U2") (pin "15") (pinfunction "Q10_15") (pintype "passive"))
    )
    (net (code "101") (name "Net-(U2-Q12)") (class "Default")
      (node (ref "J1") (pin "8") (pinfunction "8_8") (pintype "passive"))
      (node (ref "U2") (pin "1") (pinfunction "Q12_1") (pintype "passive"))
    )
    (net (code "102") (name "Net-(U2-Q13)") (class "Default")
      (node (ref "J1") (pin "9") (pinfunction "9_9") (pintype "passive"))
      (node (ref "U2") (pin "2") (pinfunction "Q13_2") (pintype "passive"))
    )
    (net (code "103") (name "Net-(U2-Q14)") (class "Default")
      (node (ref "J1") (pin "10") (pinfunction "10_10") (pintype "passive"))
      (node (ref "U2") (pin "3") (pinfunction "Q14_3") (pintype "passive"))
    )
    (net (code "104") (name "Net-(U2-φI)") (class "Default")
      (node (ref "C3") (pin "2") (pinfunction "2_2") (pintype "passive"))
      (node (ref "R29") (pin "1") (pinfunction "1_1") (pintype "passive"))
      (node (ref "U2") (pin "11") (pinfunction "φI_11") (pintype "passive"))
      (node (ref "X1") (pin "1") (pinfunction "1_1") (pintype "passive"))
    )
    (net (code "105") (name "Net-(U2-φO#)") (class "Default")
      (node (ref "R29") (pin "2") (pinfunction "2_2") (pintype "passive"))
      (node (ref "R30") (pin "2") (pinfunction "2_2") (pintype "passive"))
      (node (ref "U2") (pin "10") (pinfunction "φO#_10") (pintype "passive"))
    )
    (net (code "106") (name "Net-(U2-φO)") (class "Default")
      (node (ref "U2") (pin "9") (pinfunction "φO_9") (pintype "passive"))
      (node (ref "U4") (pin "11") (pinfunction "CCLK_11") (pintype "passive"))
      (node (ref "U4") (pin "13") (pinfunction "RCLK_13") (pintype "passive"))
    )
    (net (code "107") (name "Net-(U3-A0)") (class "Default")
      (node (ref "U3") (pin "2") (pinfunction "A0_2") (pintype "passive"))
      (node (ref "U5") (pin "2") (pinfunction "A0_2") (pintype "passive"))
      (node (ref "U6") (pin "11") (pinfunction "I/O0_11") (pintype "passive"))
    )
    (net (code "108") (name "Net-(U3-A1)") (class "Default")
      (node (ref "U3") (pin "3") (pinfunction "A1_3") (pintype "passive"))
      (node (ref "U5") (pin "3") (pinfunction "A1_3") (pintype "passive"))
      (node (ref "U6") (pin "12") (pinfunction "I/O1_12") (pintype "passive"))
    )
    (net (code "109") (name "Net-(U3-A2)") (class "Default")
      (node (ref "U3") (pin "4") (pinfunction "A2_4") (pintype "passive"))
      (node (ref "U5") (pin "4") (pinfunction "A2_4") (pintype "passive"))
      (node (ref "U6") (pin "13") (pinfunction "I/O2_13") (pintype "passive"))
    )
    (net (code "110") (name "Net-(U3-A3)") (class "Default")
      (node (ref "U3") (pin "5") (pinfunction "A3_5") (pintype "passive"))
      (node (ref "U5") (pin "5") (pinfunction "A3_5") (pintype "passive"))
      (node (ref "U6") (pin "15") (pinfunction "I/O3_15") (pintype "passive"))
    )
    (net (code "111") (name "Net-(U3-A4)") (class "Default")
      (node (ref "U3") (pin "6") (pinfunction "A4_6") (pintype "passive"))
      (node (ref "U5") (pin "6") (pinfunction "A4_6") (pintype "passive"))
      (node (ref "U6") (pin "16") (pinfunction "I/O4_16") (pintype "passive"))
    )
    (net (code "112") (name "Net-(U3-A5)") (class "Default")
      (node (ref "U3") (pin "7") (pinfunction "A5_7") (pintype "passive"))
      (node (ref "U5") (pin "7") (pinfunction "A5_7") (pintype "passive"))
      (node (ref "U6") (pin "17") (pinfunction "I/O5_17") (pintype "passive"))
    )
    (net (code "113") (name "Net-(U3-A6)") (class "Default")
      (node (ref "U3") (pin "8") (pinfunction "A6_8") (pintype "passive"))
      (node (ref "U5") (pin "8") (pinfunction "A6_8") (pintype "passive"))
      (node (ref "U6") (pin "18") (pinfunction "I/O6_18") (pintype "passive"))
    )
    (net (code "114") (name "Net-(U3-A7)") (class "Default")
      (node (ref "U3") (pin "9") (pinfunction "A7_9") (pintype "passive"))
      (node (ref "U5") (pin "9") (pinfunction "A7_9") (pintype "passive"))
      (node (ref "U6") (pin "19") (pinfunction "I/O7_19") (pintype "passive"))
    )
    (net (code "115") (name "Net-(U4-CCKEN#)") (class "Default")
      (node (ref "R26") (pin "2") (pinfunction "2_2") (pintype "passive"))
      (node (ref "U4") (pin "12") (pinfunction "CCKEN#_12") (pintype "passive"))
      (node (ref "U4") (pin "14") (pinfunction "OE#_14") (pintype "passive"))
    )
    (net (code "116") (name "Net-(U4-CCLR#)") (class "Default")
      (node (ref "R28") (pin "1") (pinfunction "1_1") (pintype "passive"))
      (node (ref "U4") (pin "10") (pinfunction "CCLR#_10") (pintype "passive"))
    )
    (net (code "117") (name "Net-(U4-QF)") (class "Default")
      (node (ref "J2") (pin "3") (pinfunction "3_3") (pintype "passive"))
      (node (ref "U4") (pin "5") (pinfunction "QF_5") (pintype "passive"))
    )
    (net (code "118") (name "Net-(U4-QG)") (class "Default")
      (node (ref "J2") (pin "2") (pinfunction "2_2") (pintype "passive"))
      (node (ref "U4") (pin "6") (pinfunction "QG_6") (pintype "passive"))
    )
    (net (code "119") (name "Net-(U4-QH)") (class "Default")
      (node (ref "J2") (pin "1") (pinfunction "1_1") (pintype "passive"))
      (node (ref "U4") (pin "7") (pinfunction "QH_7") (pintype "passive"))
    )
    (net (code "120") (name "Net-(U6-A5)") (class "Default")
      (node (ref "R56") (pin "1") (pinfunction "1_1") (pintype "passive"))
      (node (ref "SW1") (pin "7") (pinfunction "7_7") (pintype "passive"))
      (node (ref "U6") (pin "5") (pinfunction "A5_5") (pintype "passive"))
    )
    (net (code "121") (name "Net-(U6-A6)") (class "Default")
      (node (ref "R55") (pin "1") (pinfunction "1_1") (pintype "passive"))
      (node (ref "SW1") (pin "8") (pinfunction "8_8") (pintype "passive"))
      (node (ref "U6") (pin "4") (pinfunction "A6_4") (pintype "passive"))
    )
    (net (code "122") (name "Net-(U6-A7)") (class "Default")
      (node (ref "DIP1") (pin "9") (pinfunction "9_9") (pintype "passive"))
      (node (ref "R52") (pin "1") (pinfunction "1_1") (pintype "passive"))
      (node (ref "U6") (pin "3") (pinfunction "A7_3") (pintype "passive"))
    )
    (net (code "123") (name "Net-(U6-A8)") (class "Default")
      (node (ref "DIP1") (pin "10") (pinfunction "10_10") (pintype "passive"))
      (node (ref "R51") (pin "1") (pinfunction "1_1") (pintype "passive"))
      (node (ref "U6") (pin "25") (pinfunction "A8_25") (pintype "passive"))
    )
    (net (code "124") (name "Net-(U6-A9)") (class "Default")
      (node (ref "DIP1") (pin "11") (pinfunction "11_11") (pintype "passive"))
      (node (ref "R50") (pin "1") (pinfunction "1_1") (pintype "passive"))
      (node (ref "U6") (pin "24") (pinfunction "A9_24") (pintype "passive"))
    )
    (net (code "125") (name "Net-(U6-A10)") (class "Default")
      (node (ref "DIP1") (pin "12") (pinfunction "12_12") (pintype "passive"))
      (node (ref "R48") (pin "1") (pinfunction "1_1") (pintype "passive"))
      (node (ref "U6") (pin "21") (pinfunction "A10_21") (pintype "passive"))
    )
    (net (code "126") (name "Net-(U6-A11)") (class "Default")
      (node (ref "DIP1") (pin "13") (pinfunction "13_13") (pintype "passive"))
      (node (ref "R47") (pin "1") (pinfunction "1_1") (pintype "passive"))
      (node (ref "U6") (pin "23") (pinfunction "A11_23") (pintype "passive"))
    )
    (net (code "127") (name "Net-(U6-A12)") (class "Default")
      (node (ref "DIP1") (pin "14") (pinfunction "14_14") (pintype "passive"))
      (node (ref "R46") (pin "1") (pinfunction "1_1") (pintype "passive"))
      (node (ref "U6") (pin "2") (pinfunction "A12_2") (pintype "passive"))
    )
    (net (code "128") (name "Net-(U6-A13)") (class "Default")
      (node (ref "DIP1") (pin "15") (pinfunction "15_15") (pintype "passive"))
      (node (ref "R44") (pin "1") (pinfunction "1_1") (pintype "passive"))
      (node (ref "U6") (pin "26") (pinfunction "A13_26") (pintype "passive"))
    )
    (net (code "129") (name "Net-(U6-A14)") (class "Default")
      (node (ref "DIP1") (pin "16") (pinfunction "16_16") (pintype "passive"))
      (node (ref "R43") (pin "1") (pinfunction "1_1") (pintype "passive"))
      (node (ref "U6") (pin "1") (pinfunction "A14_1") (pintype "passive"))
    )
    (net (code "130") (name "Net-(U6-CE#)") (class "Default")
      (node (ref "R37") (pin "1") (pinfunction "1_1") (pintype "passive"))
      (node (ref "U6") (pin "20") (pinfunction "CE#_20") (pintype "passive"))
    )
    (net (code "131") (name "Net-(U6-OE#)") (class "Default")
      (node (ref "R35") (pin "1") (pinfunction "1_1") (pintype "passive"))
      (node (ref "U6") (pin "22") (pinfunction "OE#_22") (pintype "passive"))
    )
    (net (code "132") (name "Net-(U6-WE#)") (class "Default")
      (node (ref "R33") (pin "1") (pinfunction "1_1") (pintype "passive"))
      (node (ref "U6") (pin "27") (pinfunction "WE#_27") (pintype "passive"))
    )
    (net (code "133") (name "unconnected-(U4-RCO#-Pad9)") (class "Default")
      (node (ref "U4") (pin "9") (pinfunction "RCO#_9") (pintype "passive+no_connect"))
    )
  )
)
